# RK3566_HPB1.net
KiCad netlist of a schematic drawn in Altium Designer
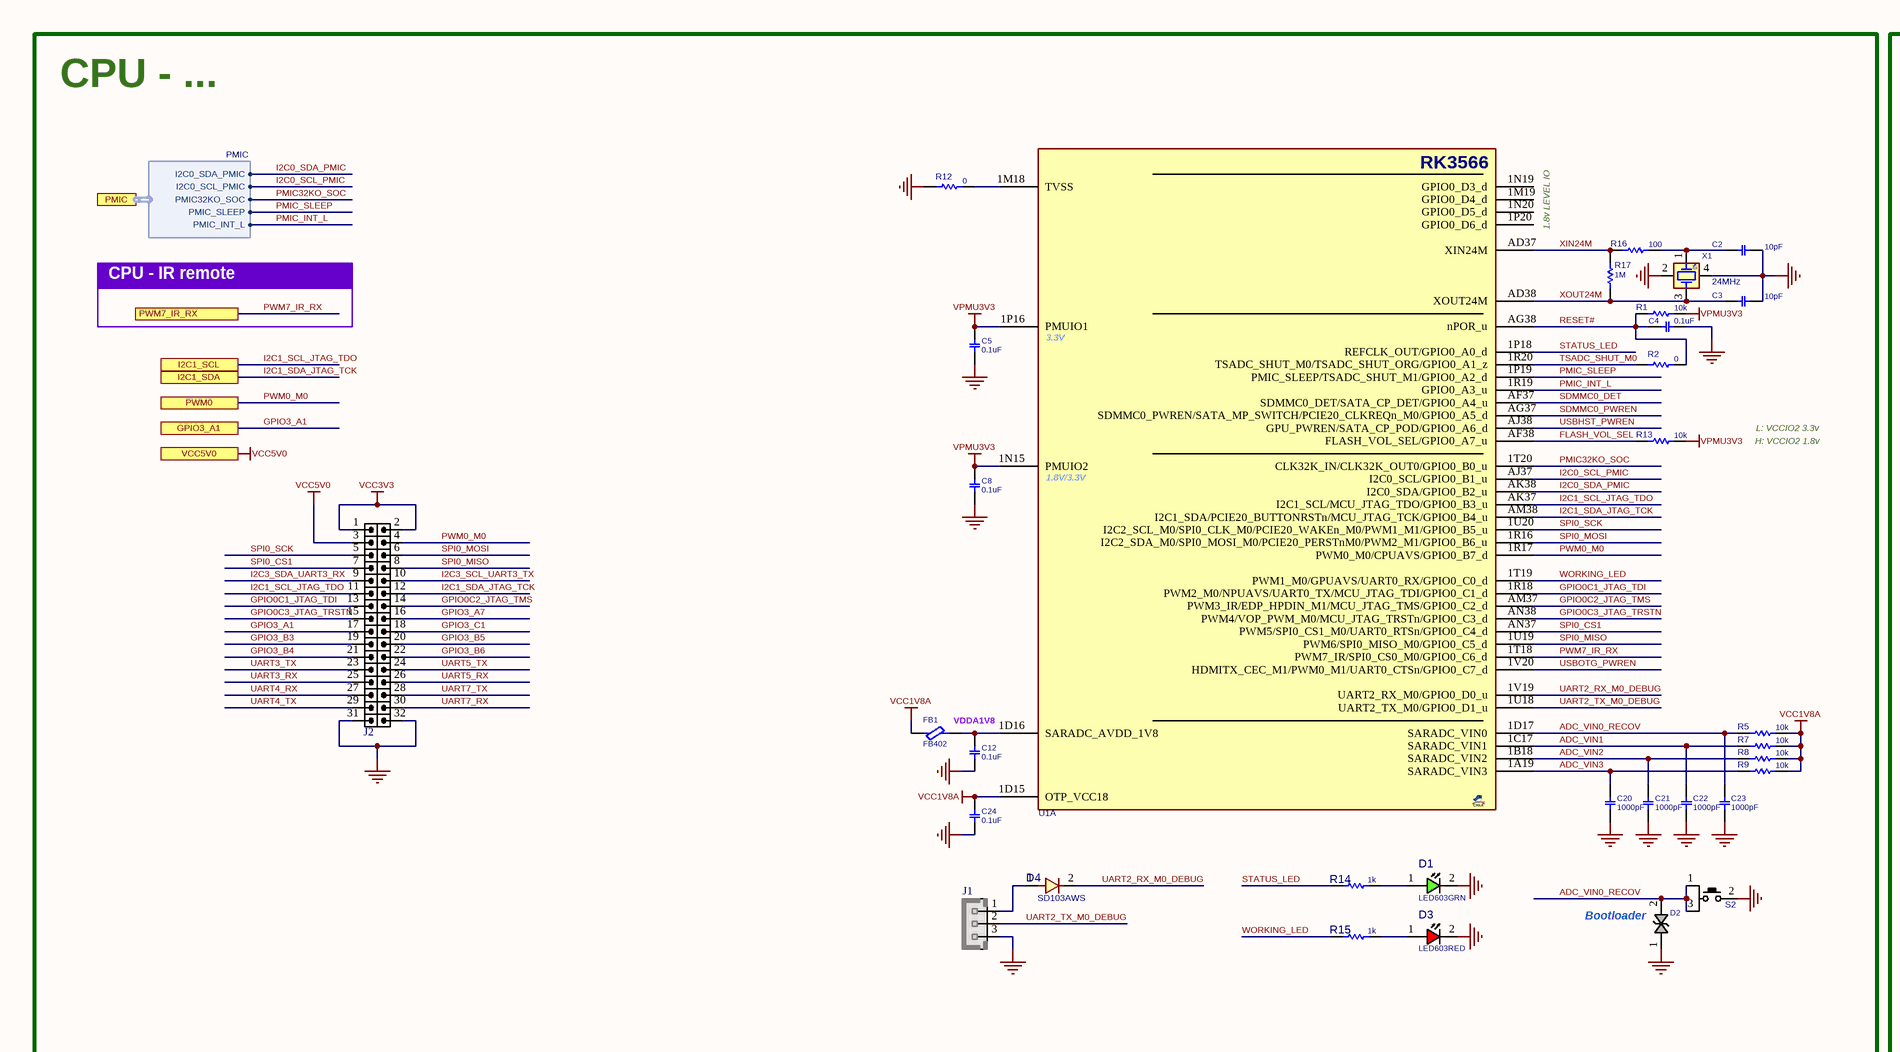
[diagram p0: RK3566_HPB1.SchDoc, top left]
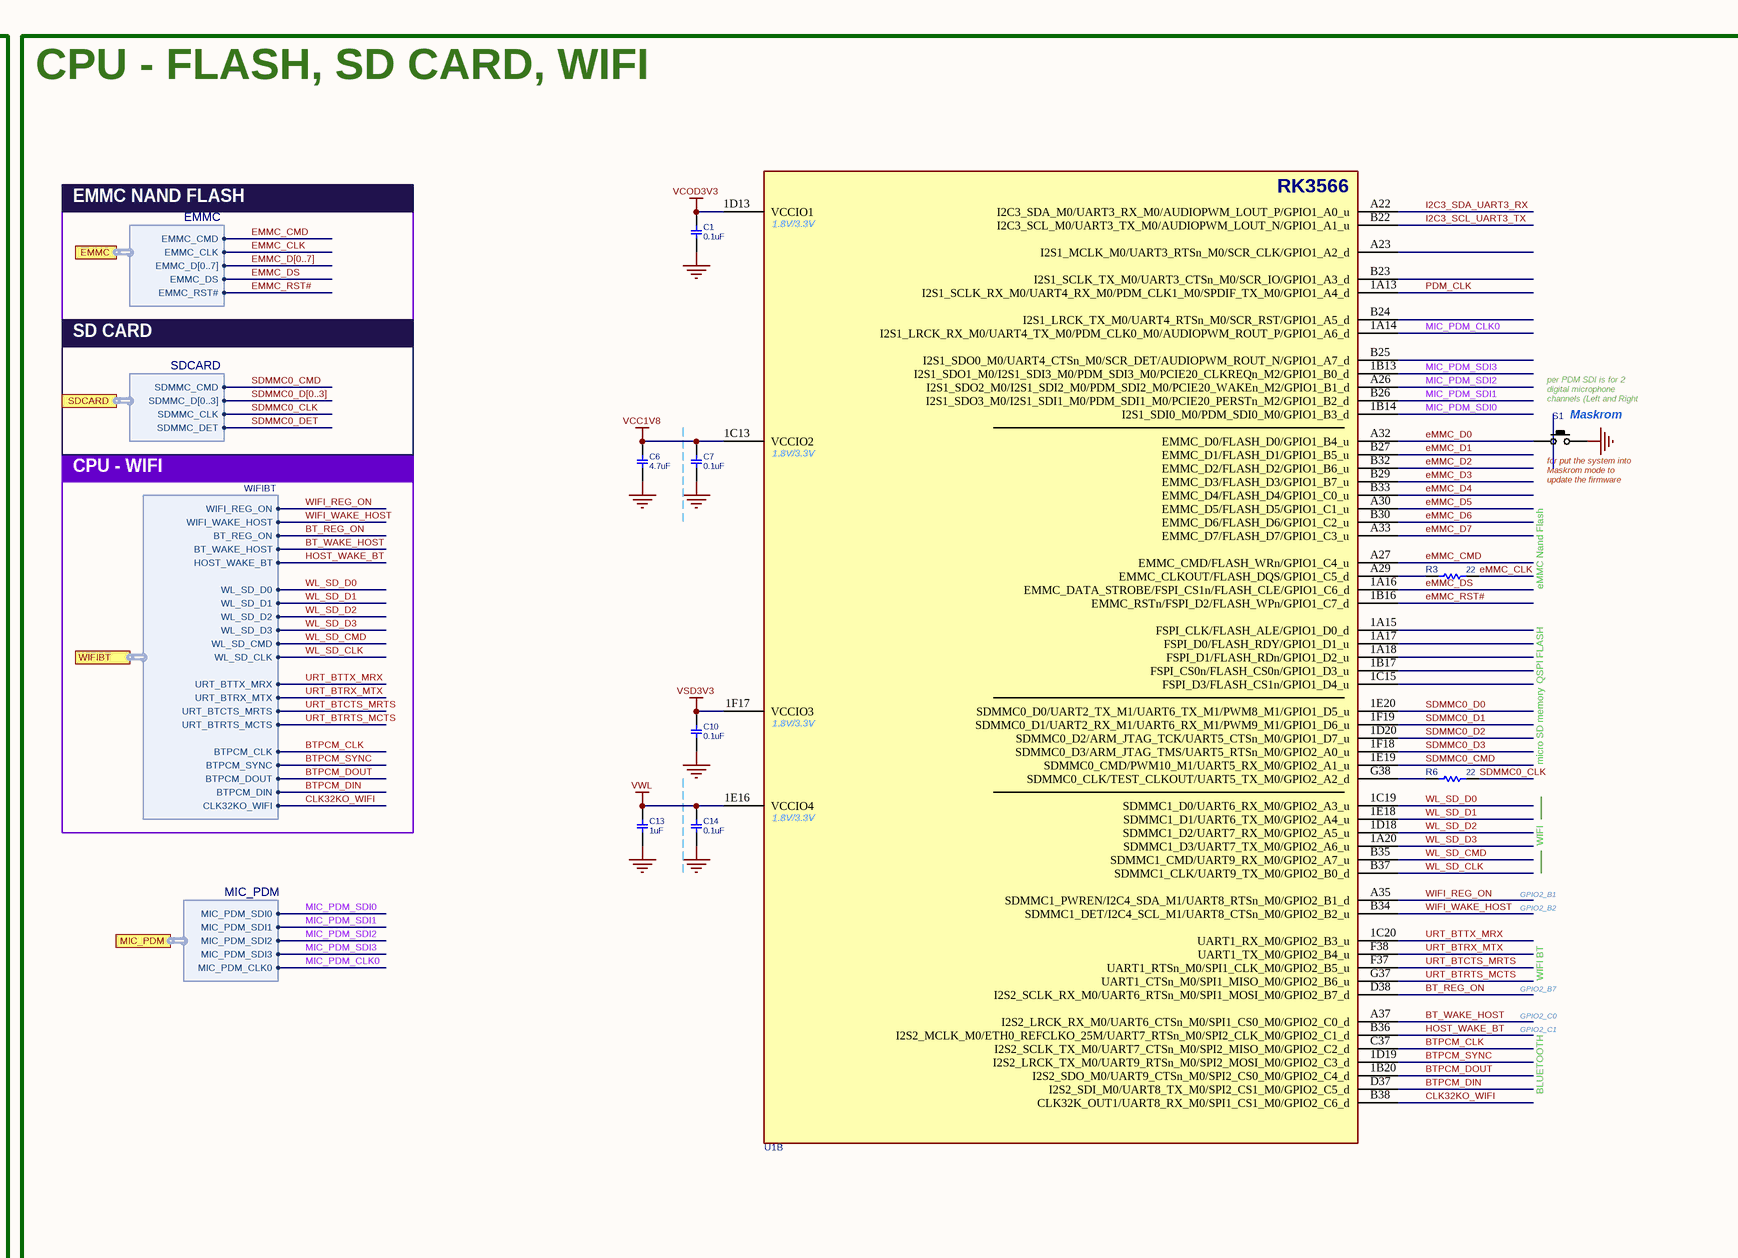
[diagram p1: RK3566_HPB1.SchDoc, top middle]
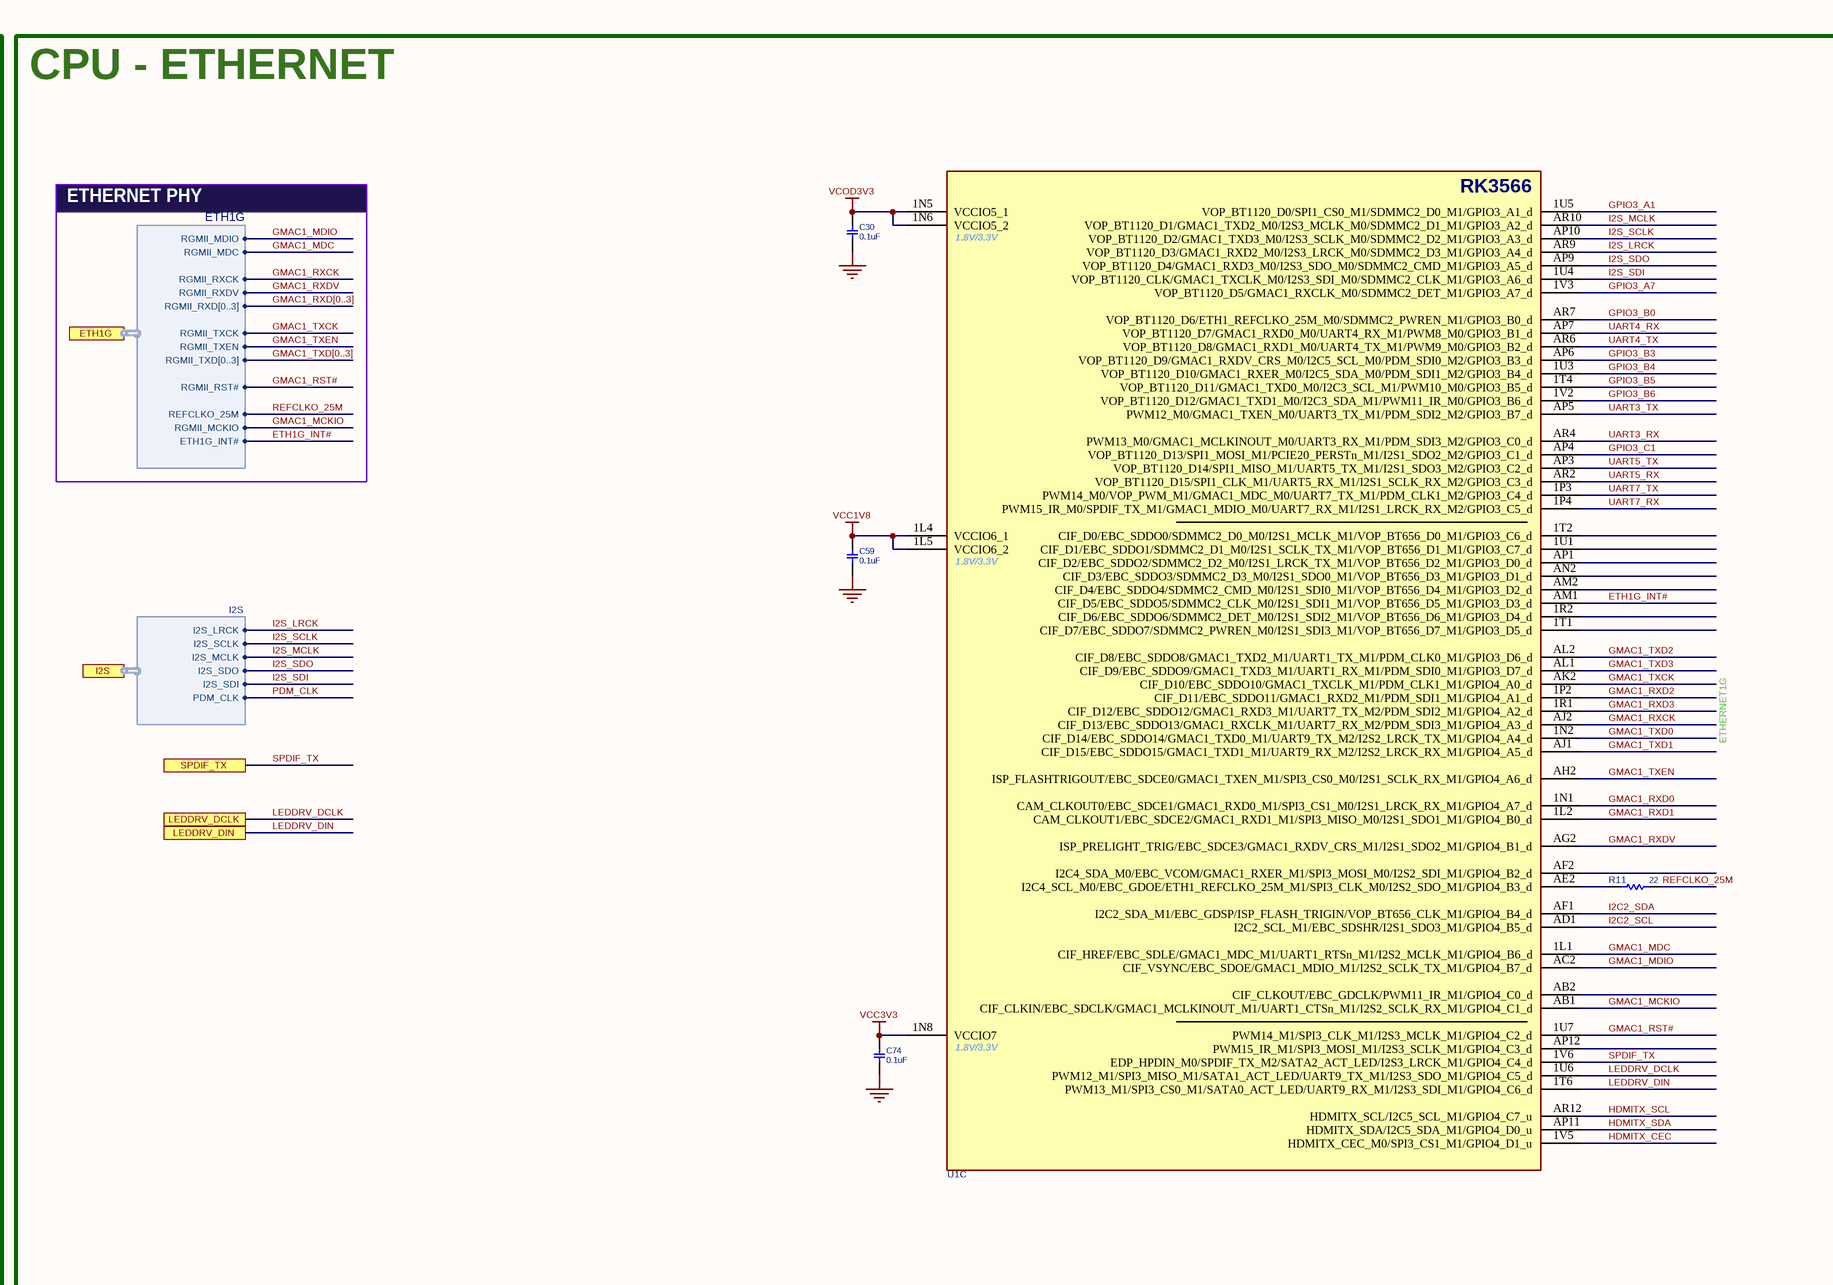
[diagram p2: RK3566_HPB1.SchDoc, top right]
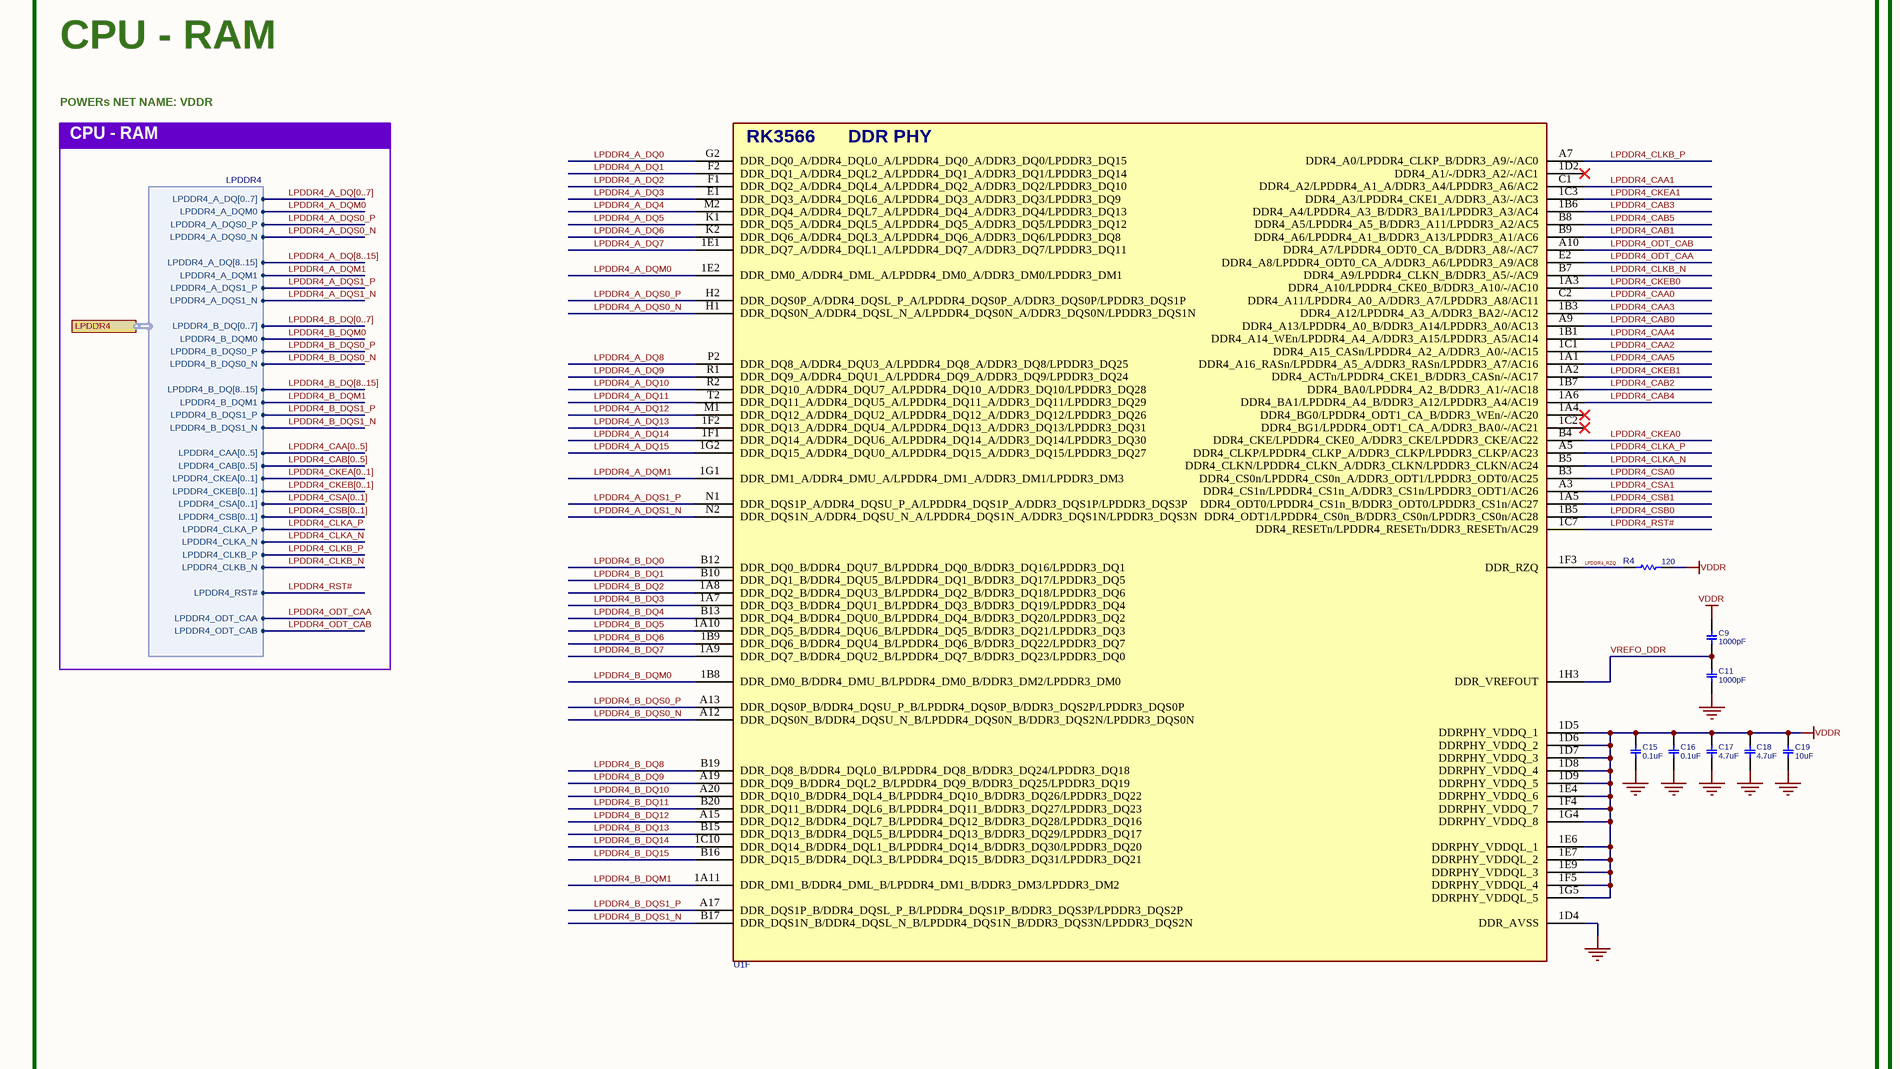
[diagram p3: RK3566_HPB1.SchDoc, bottom left]
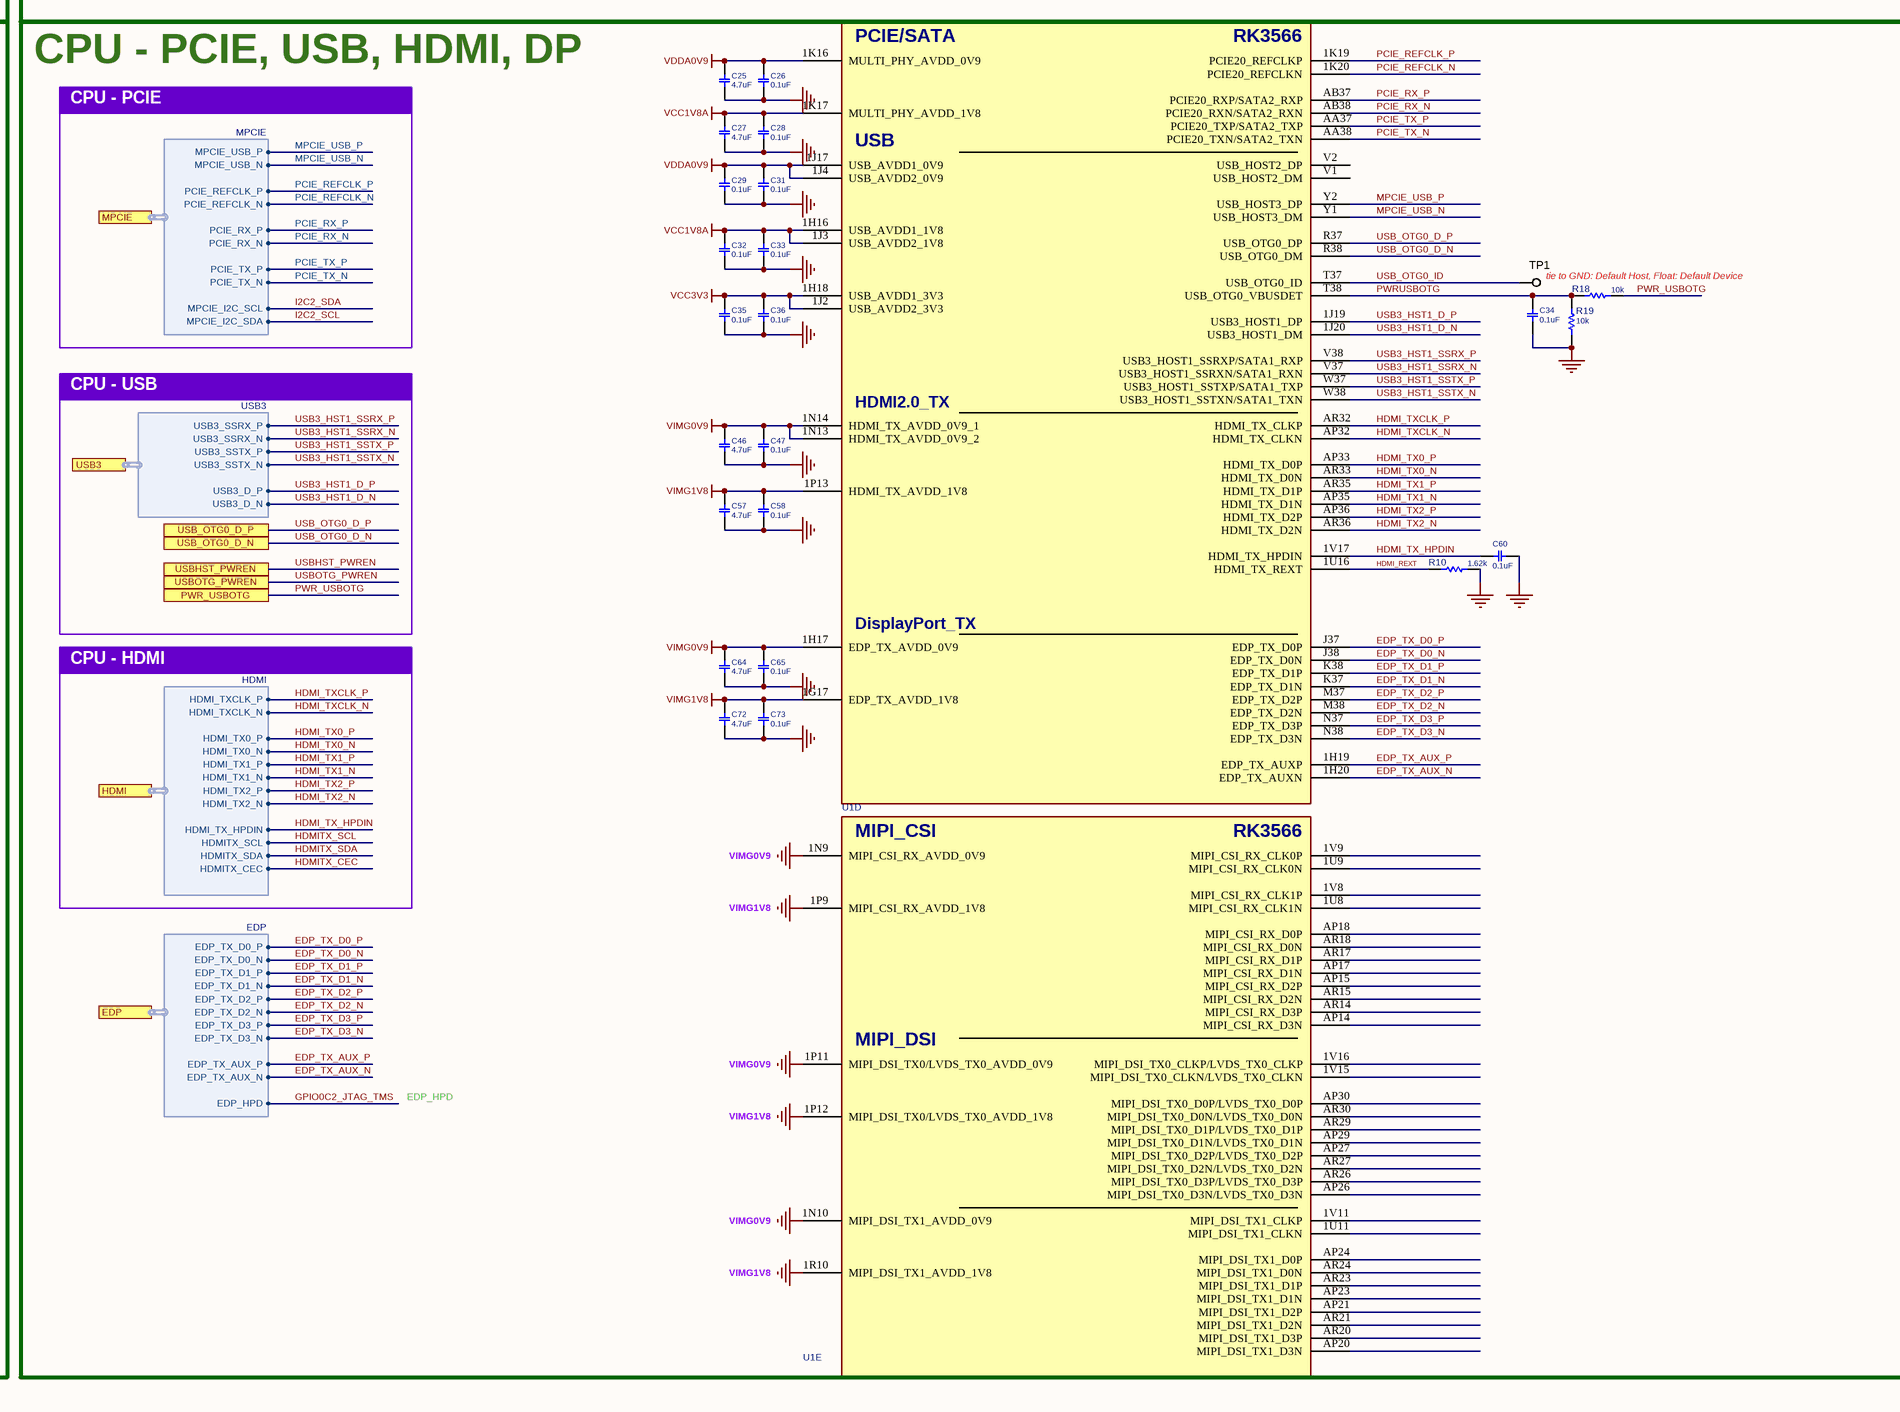
[diagram p4: RK3566_HPB1.SchDoc, bottom middle]
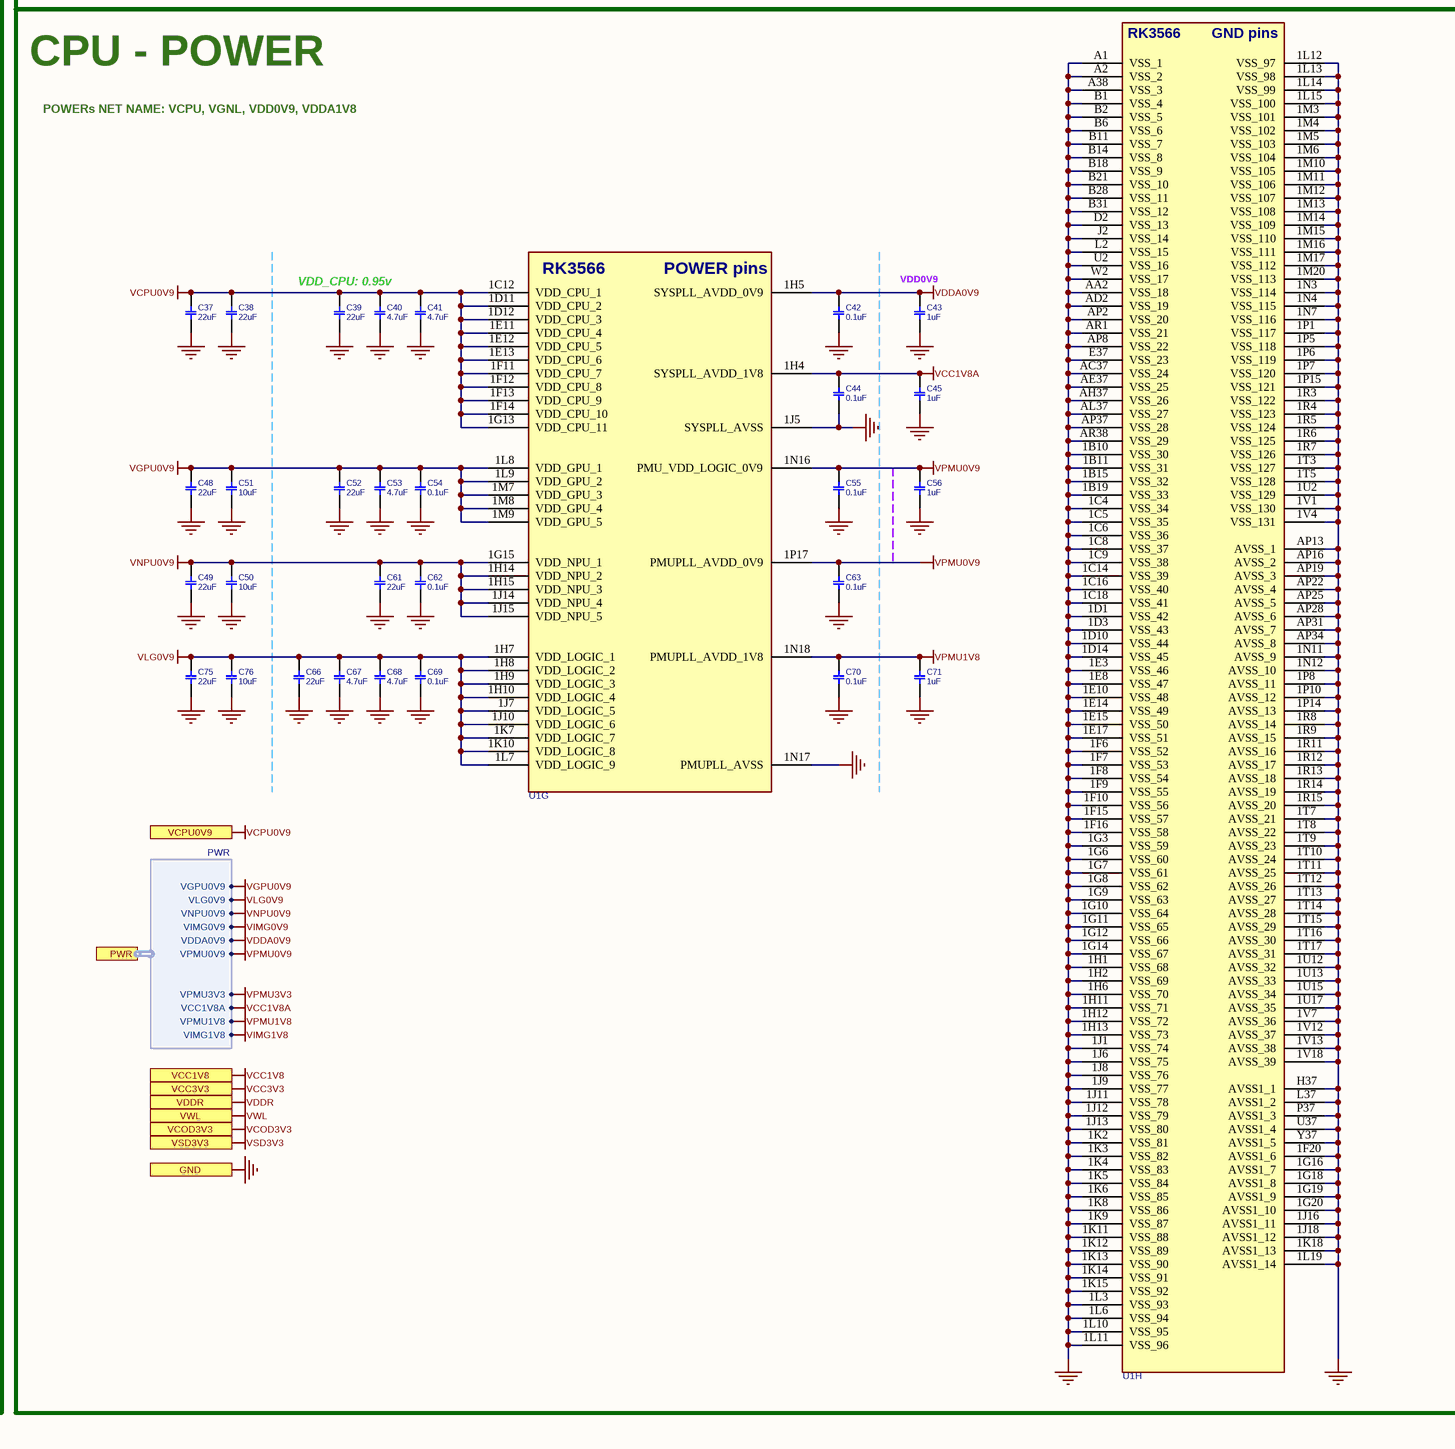
[diagram p5: RK3566_HPB1.SchDoc, bottom right]

(export (version "E")
  (design (tool "Eeschema 10.0.6"))
  (components
    (comp (ref "C1")
      (value "0.1uF")
      (footprint "C0201")
      (description "CAP, MLCC")
      (fields (field (name "MANF_P#") "CL03A104KP3NNWC") (field (name "MANF") "Samsung"))
      (libsource (lib "passive_smd") (part "CAP_SMD_MLCC"))
    )
    (comp (ref "C2")
      (value "10pF")
      (footprint "C0402A")
      (description "CAP, MLCC")
      (fields (field (name "MANF_P#") "CC0402JRNPO9BN180") (field (name "MANF") "Yageo"))
      (libsource (lib "mlcc_smd_passive") (part "CAP_SMD_MLCC"))
    )
    (comp (ref "C3")
      (value "10pF")
      (footprint "C0402A")
      (description "CAP, MLCC")
      (fields (field (name "MANF_P#") "CC0402JRNPO9BN180") (field (name "MANF") "Yageo"))
      (libsource (lib "mlcc_smd_passive") (part "CAP_SMD_MLCC"))
    )
    (comp (ref "C4")
      (value "0.1uF")
      (footprint "C0402A")
      (description "CAP, MLCC")
      (fields (field (name "MANF_P#") "CL03A104KP3NNWC") (field (name "MANF") "Samsung"))
      (libsource (lib "passive_smd") (part "CAP_SMD_MLCC"))
    )
    (comp (ref "C5")
      (value "0.1uF")
      (footprint "C0201")
      (description "CAP, MLCC")
      (fields (field (name "MANF_P#") "CL03A104KP3NNWC") (field (name "MANF") "Samsung"))
      (libsource (lib "passive_smd") (part "CAP_SMD_MLCC"))
    )
    (comp (ref "C6")
      (value "4.7uF")
      (footprint "C0201")
      (description "CAP, MLCC")
      (fields (field (name "MANF_P#") "CL03A475MQ5C65C") (field (name "MANF") "Samsung"))
      (libsource (lib "passive_smd") (part "CAP_SMD_MLCC"))
    )
    (comp (ref "C7")
      (value "0.1uF")
      (footprint "C0201")
      (description "CAP, MLCC")
      (fields (field (name "MANF_P#") "CL03A104KP3NNWC") (field (name "MANF") "Samsung"))
      (libsource (lib "passive_smd") (part "CAP_SMD_MLCC"))
    )
    (comp (ref "C8")
      (value "0.1uF")
      (footprint "C0201")
      (description "CAP, MLCC")
      (fields (field (name "MANF_P#") "CL03A104KP3NNWC") (field (name "MANF") "Samsung"))
      (libsource (lib "passive_smd") (part "CAP_SMD_MLCC"))
    )
    (comp (ref "C9")
      (value "1000pF")
      (footprint "C0201")
      (description "CAP, MLCC")
      (fields (field (name "MANF_P#") "CC0201KRX7R7BB102") (field (name "MANF") "Yageo"))
      (libsource (lib "mlcc_smd_passive") (part "CAP_SMD_MLCC"))
    )
    (comp (ref "C10")
      (value "0.1uF")
      (footprint "C0201")
      (description "CAP, MLCC")
      (fields (field (name "MANF_P#") "CL03A104KP3NNWC") (field (name "MANF") "Samsung"))
      (libsource (lib "passive_smd") (part "CAP_SMD_MLCC"))
    )
    (comp (ref "C11")
      (value "1000pF")
      (footprint "C0201")
      (description "CAP, MLCC")
      (fields (field (name "MANF_P#") "CC0201KRX7R7BB102") (field (name "MANF") "Yageo"))
      (libsource (lib "mlcc_smd_passive") (part "CAP_SMD_MLCC"))
    )
    (comp (ref "C12")
      (value "0.1uF")
      (footprint "C0201")
      (description "CAP, MLCC")
      (fields (field (name "MANF_P#") "CL03A104KP3NNWC") (field (name "MANF") "Samsung"))
      (libsource (lib "passive_smd") (part "CAP_SMD_MLCC"))
    )
    (comp (ref "C13")
      (value "1uF")
      (footprint "C0201")
      (description "CAP, MLCC")
      (fields (field (name "MANF_P#") "CL03A105MQ3CSNC") (field (name "MANF") "Samsung"))
      (libsource (lib "passive_smd") (part "CAP_SMD_MLCC"))
    )
    (comp (ref "C14")
      (value "0.1uF")
      (footprint "C0201")
      (description "CAP, MLCC")
      (fields (field (name "MANF_P#") "CL03A104KP3NNWC") (field (name "MANF") "Samsung"))
      (libsource (lib "passive_smd") (part "CAP_SMD_MLCC"))
    )
    (comp (ref "C15")
      (value "0.1uF")
      (footprint "C0201")
      (description "CAP, MLCC")
      (fields (field (name "MANF_P#") "CL03A104KP3NNWC") (field (name "MANF") "Samsung"))
      (libsource (lib "passive_smd") (part "CAP_SMD_MLCC"))
    )
    (comp (ref "C16")
      (value "0.1uF")
      (footprint "C0201")
      (description "CAP, MLCC")
      (fields (field (name "MANF_P#") "CL03A104KP3NNWC") (field (name "MANF") "Samsung"))
      (libsource (lib "passive_smd") (part "CAP_SMD_MLCC"))
    )
    (comp (ref "C17")
      (value "4.7uF")
      (footprint "C0201")
      (description "CAP, MLCC")
      (fields (field (name "MANF_P#") "CL03A475MQ5C65C") (field (name "MANF") "Samsung"))
      (libsource (lib "passive_smd") (part "CAP_SMD_MLCC"))
    )
    (comp (ref "C18")
      (value "4.7uF")
      (footprint "C0201")
      (description "CAP, MLCC")
      (fields (field (name "MANF_P#") "CL03A475MQ5C65C") (field (name "MANF") "Samsung"))
      (libsource (lib "passive_smd") (part "CAP_SMD_MLCC"))
    )
    (comp (ref "C19")
      (value "10uF")
      (footprint "C0402A")
      (description "CAP, MLCC")
      (fields (field (name "MANF_P#") "CL05A106MP5NUNC") (field (name "MANF") "Samsung"))
      (libsource (lib "passive_smd") (part "CAP_SMD_MLCC"))
    )
    (comp (ref "C20")
      (value "1000pF")
      (footprint "C0201")
      (description "CAP, MLCC")
      (fields (field (name "MANF_P#") "CC0201KRX7R7BB102") (field (name "MANF") "Yageo"))
      (libsource (lib "mlcc_smd_passive") (part "CAP_SMD_MLCC"))
    )
    (comp (ref "C21")
      (value "1000pF")
      (footprint "C0201")
      (description "CAP, MLCC")
      (fields (field (name "MANF_P#") "CC0201KRX7R7BB102") (field (name "MANF") "Yageo"))
      (libsource (lib "mlcc_smd_passive") (part "CAP_SMD_MLCC"))
    )
    (comp (ref "C22")
      (value "1000pF")
      (footprint "C0201")
      (description "CAP, MLCC")
      (fields (field (name "MANF_P#") "CC0201KRX7R7BB102") (field (name "MANF") "Yageo"))
      (libsource (lib "mlcc_smd_passive") (part "CAP_SMD_MLCC"))
    )
    (comp (ref "C23")
      (value "1000pF")
      (footprint "C0201")
      (description "CAP, MLCC")
      (fields (field (name "MANF_P#") "CC0201KRX7R7BB102") (field (name "MANF") "Yageo"))
      (libsource (lib "mlcc_smd_passive") (part "CAP_SMD_MLCC"))
    )
    (comp (ref "C24")
      (value "0.1uF")
      (footprint "C0201")
      (description "CAP, MLCC")
      (fields (field (name "MANF_P#") "CL03A104KP3NNWC") (field (name "MANF") "Samsung"))
      (libsource (lib "passive_smd") (part "CAP_SMD_MLCC"))
    )
    (comp (ref "C25")
      (value "4.7uF")
      (footprint "C0201")
      (description "CAP, MLCC")
      (fields (field (name "MANF_P#") "CL03A475MQ5C65C") (field (name "MANF") "Samsung"))
      (libsource (lib "passive_smd") (part "CAP_SMD_MLCC"))
    )
    (comp (ref "C26")
      (value "0.1uF")
      (footprint "C0201")
      (description "CAP, MLCC")
      (fields (field (name "MANF_P#") "CL03A104KP3NNWC") (field (name "MANF") "Samsung"))
      (libsource (lib "passive_smd") (part "CAP_SMD_MLCC"))
    )
    (comp (ref "C27")
      (value "4.7uF")
      (footprint "C0201")
      (description "CAP, MLCC")
      (fields (field (name "MANF_P#") "CL03A475MQ5C65C") (field (name "MANF") "Samsung"))
      (libsource (lib "passive_smd") (part "CAP_SMD_MLCC"))
    )
    (comp (ref "C28")
      (value "0.1uF")
      (footprint "C0201")
      (description "CAP, MLCC")
      (fields (field (name "MANF_P#") "CL03A104KP3NNWC") (field (name "MANF") "Samsung"))
      (libsource (lib "passive_smd") (part "CAP_SMD_MLCC"))
    )
    (comp (ref "C29")
      (value "0.1uF")
      (footprint "C0201")
      (description "CAP, MLCC")
      (fields (field (name "MANF_P#") "CL03A104KP3NNWC") (field (name "MANF") "Samsung"))
      (libsource (lib "passive_smd") (part "CAP_SMD_MLCC"))
    )
    (comp (ref "C30")
      (value "0.1uF")
      (footprint "C0201")
      (description "CAP, MLCC")
      (fields (field (name "MANF_P#") "CL03A104KP3NNWC") (field (name "MANF") "Samsung"))
      (libsource (lib "passive_smd") (part "CAP_SMD_MLCC"))
    )
    (comp (ref "C31")
      (value "0.1uF")
      (footprint "C0201")
      (description "CAP, MLCC")
      (fields (field (name "MANF_P#") "CL03A104KP3NNWC") (field (name "MANF") "Samsung"))
      (libsource (lib "passive_smd") (part "CAP_SMD_MLCC"))
    )
    (comp (ref "C32")
      (value "0.1uF")
      (footprint "C0201")
      (description "CAP, MLCC")
      (fields (field (name "MANF_P#") "CL03A104KP3NNWC") (field (name "MANF") "Samsung"))
      (libsource (lib "passive_smd") (part "CAP_SMD_MLCC"))
    )
    (comp (ref "C33")
      (value "0.1uF")
      (footprint "C0201")
      (description "CAP, MLCC")
      (fields (field (name "MANF_P#") "CL03A104KP3NNWC") (field (name "MANF") "Samsung"))
      (libsource (lib "passive_smd") (part "CAP_SMD_MLCC"))
    )
    (comp (ref "C34")
      (value "0.1uF")
      (footprint "C0402A")
      (description "CAP, MLCC")
      (fields (field (name "MANF_P#") "CL03A104KP3NNWC") (field (name "MANF") "Samsung"))
      (libsource (lib "passive_smd") (part "CAP_SMD_MLCC"))
    )
    (comp (ref "C35")
      (value "0.1uF")
      (footprint "C0201")
      (description "CAP, MLCC")
      (fields (field (name "MANF_P#") "CL03A104KP3NNWC") (field (name "MANF") "Samsung"))
      (libsource (lib "passive_smd") (part "CAP_SMD_MLCC"))
    )
    (comp (ref "C36")
      (value "0.1uF")
      (footprint "C0201")
      (description "CAP, MLCC")
      (fields (field (name "MANF_P#") "CL03A104KP3NNWC") (field (name "MANF") "Samsung"))
      (libsource (lib "passive_smd") (part "CAP_SMD_MLCC"))
    )
    (comp (ref "C37")
      (value "22uF")
      (footprint "C0402A")
      (description "CAP, MLCC")
      (fields (field (name "MANF_P#") "GRM158R61A226ME15") (field (name "MANF") "Murata"))
      (libsource (lib "passive_smd") (part "CAP_SMD_MLCC"))
    )
    (comp (ref "C38")
      (value "22uF")
      (footprint "C0402A")
      (description "CAP, MLCC")
      (fields (field (name "MANF_P#") "GRM158R61A226ME15") (field (name "MANF") "Murata"))
      (libsource (lib "passive_smd") (part "CAP_SMD_MLCC"))
    )
    (comp (ref "C39")
      (value "22uF")
      (footprint "C0402A")
      (description "CAP, MLCC")
      (fields (field (name "MANF_P#") "GRM158R61A226ME15") (field (name "MANF") "Murata"))
      (libsource (lib "passive_smd") (part "CAP_SMD_MLCC"))
    )
    (comp (ref "C40")
      (value "4.7uF")
      (footprint "C0201")
      (description "CAP, MLCC")
      (fields (field (name "MANF_P#") "CL03A475MQ5C65C") (field (name "MANF") "Samsung"))
      (libsource (lib "passive_smd") (part "CAP_SMD_MLCC"))
    )
    (comp (ref "C41")
      (value "4.7uF")
      (footprint "C0201")
      (description "CAP, MLCC")
      (fields (field (name "MANF_P#") "CL03A475MQ5C65C") (field (name "MANF") "Samsung"))
      (libsource (lib "passive_smd") (part "CAP_SMD_MLCC"))
    )
    (comp (ref "C42")
      (value "0.1uF")
      (footprint "C0201")
      (description "CAP, MLCC")
      (fields (field (name "MANF_P#") "CL03A104KP3NNWC") (field (name "MANF") "Samsung"))
      (libsource (lib "passive_smd") (part "CAP_SMD_MLCC"))
    )
    (comp (ref "C43")
      (value "1uF")
      (footprint "C0201")
      (description "CAP, MLCC")
      (fields (field (name "MANF_P#") "CL03A105MQ3CSNC") (field (name "MANF") "Samsung"))
      (libsource (lib "passive_smd") (part "CAP_SMD_MLCC"))
    )
    (comp (ref "C44")
      (value "0.1uF")
      (footprint "C0201")
      (description "CAP, MLCC")
      (fields (field (name "MANF_P#") "CL03A104KP3NNWC") (field (name "MANF") "Samsung"))
      (libsource (lib "passive_smd") (part "CAP_SMD_MLCC"))
    )
    (comp (ref "C45")
      (value "1uF")
      (footprint "C0201")
      (description "CAP, MLCC")
      (fields (field (name "MANF_P#") "CL03A105MQ3CSNC") (field (name "MANF") "Samsung"))
      (libsource (lib "passive_smd") (part "CAP_SMD_MLCC"))
    )
    (comp (ref "C46")
      (value "4.7uF")
      (footprint "C0201")
      (description "CAP, MLCC")
      (fields (field (name "MANF_P#") "CL03A475MQ5C65C") (field (name "MANF") "Samsung"))
      (libsource (lib "passive_smd") (part "CAP_SMD_MLCC"))
    )
    (comp (ref "C47")
      (value "0.1uF")
      (footprint "C0201")
      (description "CAP, MLCC")
      (fields (field (name "MANF_P#") "CL03A104KP3NNWC") (field (name "MANF") "Samsung"))
      (libsource (lib "passive_smd") (part "CAP_SMD_MLCC"))
    )
    (comp (ref "C48")
      (value "22uF")
      (footprint "C0402A")
      (description "CAP, MLCC")
      (fields (field (name "MANF_P#") "GRM158R61A226ME15") (field (name "MANF") "Murata"))
      (libsource (lib "passive_smd") (part "CAP_SMD_MLCC"))
    )
    (comp (ref "C49")
      (value "22uF")
      (footprint "C0402A")
      (description "CAP, MLCC")
      (fields (field (name "MANF_P#") "GRM158R61A226ME15") (field (name "MANF") "Murata"))
      (libsource (lib "passive_smd") (part "CAP_SMD_MLCC"))
    )
    (comp (ref "C50")
      (value "10uF")
      (footprint "C0402A")
      (description "CAP, MLCC")
      (fields (field (name "MANF_P#") "CL05A106MP5NUNC") (field (name "MANF") "Samsung"))
      (libsource (lib "passive_smd") (part "CAP_SMD_MLCC"))
    )
    (comp (ref "C51")
      (value "10uF")
      (footprint "C0402A")
      (description "CAP, MLCC")
      (fields (field (name "MANF_P#") "CL05A106MP5NUNC") (field (name "MANF") "Samsung"))
      (libsource (lib "passive_smd") (part "CAP_SMD_MLCC"))
    )
    (comp (ref "C52")
      (value "22uF")
      (footprint "C0402A")
      (description "CAP, MLCC")
      (fields (field (name "MANF_P#") "GRM158R61A226ME15") (field (name "MANF") "Murata"))
      (libsource (lib "passive_smd") (part "CAP_SMD_MLCC"))
    )
    (comp (ref "C53")
      (value "4.7uF")
      (footprint "C0201")
      (description "CAP, MLCC")
      (fields (field (name "MANF_P#") "CL03A475MQ5C65C") (field (name "MANF") "Samsung"))
      (libsource (lib "passive_smd") (part "CAP_SMD_MLCC"))
    )
    (comp (ref "C54")
      (value "0.1uF")
      (footprint "C0201")
      (description "CAP, MLCC")
      (fields (field (name "MANF_P#") "CL03A104KP3NNWC") (field (name "MANF") "Samsung"))
      (libsource (lib "passive_smd") (part "CAP_SMD_MLCC"))
    )
    (comp (ref "C55")
      (value "0.1uF")
      (footprint "C0201")
      (description "CAP, MLCC")
      (fields (field (name "MANF_P#") "CL03A104KP3NNWC") (field (name "MANF") "Samsung"))
      (libsource (lib "passive_smd") (part "CAP_SMD_MLCC"))
    )
    (comp (ref "C56")
      (value "1uF")
      (footprint "C0201")
      (description "CAP, MLCC")
      (fields (field (name "MANF_P#") "CL03A105MQ3CSNC") (field (name "MANF") "Samsung"))
      (libsource (lib "passive_smd") (part "CAP_SMD_MLCC"))
    )
    (comp (ref "C57")
      (value "4.7uF")
      (footprint "C0201")
      (description "CAP, MLCC")
      (fields (field (name "MANF_P#") "CL03A475MQ5C65C") (field (name "MANF") "Samsung"))
      (libsource (lib "passive_smd") (part "CAP_SMD_MLCC"))
    )
    (comp (ref "C58")
      (value "0.1uF")
      (footprint "C0201")
      (description "CAP, MLCC")
      (fields (field (name "MANF_P#") "CL03A104KP3NNWC") (field (name "MANF") "Samsung"))
      (libsource (lib "passive_smd") (part "CAP_SMD_MLCC"))
    )
    (comp (ref "C59")
      (value "0.1uF")
      (footprint "C0201")
      (description "CAP, MLCC")
      (fields (field (name "MANF_P#") "CL03A104KP3NNWC") (field (name "MANF") "Samsung"))
      (libsource (lib "passive_smd") (part "CAP_SMD_MLCC"))
    )
    (comp (ref "C60")
      (value "0.1uF")
      (footprint "C0201")
      (description "CAP, MLCC")
      (fields (field (name "MANF_P#") "CL03A104KP3NNWC") (field (name "MANF") "Samsung"))
      (libsource (lib "passive_smd") (part "CAP_SMD_MLCC"))
    )
    (comp (ref "C61")
      (value "22uF")
      (footprint "C0402A")
      (description "CAP, MLCC")
      (fields (field (name "MANF_P#") "GRM158R61A226ME15") (field (name "MANF") "Murata"))
      (libsource (lib "passive_smd") (part "CAP_SMD_MLCC"))
    )
    (comp (ref "C62")
      (value "0.1uF")
      (footprint "C0201")
      (description "CAP, MLCC")
      (fields (field (name "MANF_P#") "CL03A104KP3NNWC") (field (name "MANF") "Samsung"))
      (libsource (lib "passive_smd") (part "CAP_SMD_MLCC"))
    )
    (comp (ref "C63")
      (value "0.1uF")
      (footprint "C0201")
      (description "CAP, MLCC")
      (fields (field (name "MANF_P#") "CL03A104KP3NNWC") (field (name "MANF") "Samsung"))
      (libsource (lib "passive_smd") (part "CAP_SMD_MLCC"))
    )
    (comp (ref "C64")
      (value "4.7uF")
      (footprint "C0201")
      (description "CAP, MLCC")
      (fields (field (name "MANF_P#") "CL03A475MQ5C65C") (field (name "MANF") "Samsung"))
      (libsource (lib "passive_smd") (part "CAP_SMD_MLCC"))
    )
    (comp (ref "C65")
      (value "0.1uF")
      (footprint "C0201")
      (description "CAP, MLCC")
      (fields (field (name "MANF_P#") "CL03A104KP3NNWC") (field (name "MANF") "Samsung"))
      (libsource (lib "passive_smd") (part "CAP_SMD_MLCC"))
    )
    (comp (ref "C66")
      (value "22uF")
      (footprint "C0402A")
      (description "CAP, MLCC")
      (fields (field (name "MANF_P#") "GRM158R61A226ME15") (field (name "MANF") "Murata"))
      (libsource (lib "passive_smd") (part "CAP_SMD_MLCC"))
    )
    (comp (ref "C67")
      (value "4.7uF")
      (footprint "C0201")
      (description "CAP, MLCC")
      (fields (field (name "MANF_P#") "CL03A475MQ5C65C") (field (name "MANF") "Samsung"))
      (libsource (lib "passive_smd") (part "CAP_SMD_MLCC"))
    )
    (comp (ref "C68")
      (value "4.7uF")
      (footprint "C0201")
      (description "CAP, MLCC")
      (fields (field (name "MANF_P#") "CL03A475MQ5C65C") (field (name "MANF") "Samsung"))
      (libsource (lib "passive_smd") (part "CAP_SMD_MLCC"))
    )
    (comp (ref "C69")
      (value "0.1uF")
      (footprint "C0201")
      (description "CAP, MLCC")
      (fields (field (name "MANF_P#") "CL03A104KP3NNWC") (field (name "MANF") "Samsung"))
      (libsource (lib "passive_smd") (part "CAP_SMD_MLCC"))
    )
    (comp (ref "C70")
      (value "0.1uF")
      (footprint "C0201")
      (description "CAP, MLCC")
      (fields (field (name "MANF_P#") "CL03A104KP3NNWC") (field (name "MANF") "Samsung"))
      (libsource (lib "passive_smd") (part "CAP_SMD_MLCC"))
    )
    (comp (ref "C71")
      (value "1uF")
      (footprint "C0201")
      (description "CAP, MLCC")
      (fields (field (name "MANF_P#") "CL03A105MQ3CSNC") (field (name "MANF") "Samsung"))
      (libsource (lib "passive_smd") (part "CAP_SMD_MLCC"))
    )
    (comp (ref "C72")
      (value "4.7uF")
      (footprint "C0201")
      (description "CAP, MLCC")
      (fields (field (name "MANF_P#") "CL03A475MQ5C65C") (field (name "MANF") "Samsung"))
      (libsource (lib "passive_smd") (part "CAP_SMD_MLCC"))
    )
    (comp (ref "C73")
      (value "0.1uF")
      (footprint "C0201")
      (description "CAP, MLCC")
      (fields (field (name "MANF_P#") "CL03A104KP3NNWC") (field (name "MANF") "Samsung"))
      (libsource (lib "passive_smd") (part "CAP_SMD_MLCC"))
    )
    (comp (ref "C74")
      (value "0.1uF")
      (footprint "C0201")
      (description "CAP, MLCC")
      (fields (field (name "MANF_P#") "CL03A104KP3NNWC") (field (name "MANF") "Samsung"))
      (libsource (lib "passive_smd") (part "CAP_SMD_MLCC"))
    )
    (comp (ref "C75")
      (value "22uF")
      (footprint "C0402A")
      (description "CAP, MLCC")
      (fields (field (name "MANF_P#") "GRM158R61A226ME15") (field (name "MANF") "Murata"))
      (libsource (lib "passive_smd") (part "CAP_SMD_MLCC"))
    )
    (comp (ref "C76")
      (value "10uF")
      (footprint "C0402A")
      (description "CAP, MLCC")
      (fields (field (name "MANF_P#") "CL05A106MP5NUNC") (field (name "MANF") "Samsung"))
      (libsource (lib "passive_smd") (part "CAP_SMD_MLCC"))
    )
    (comp (ref "D1")
      (value "LED603GRN")
      (footprint "LED0603GRN")
      (description "LED, SMD, 0603, GREEN")
      (fields (field (name "MANF") "OSRAM") (field (name "MANF_P#") "LG Q396-PS-35"))
      (libsource (lib "led(diode)") (part "LED_SMD_0603_GRN_OSRAM"))
    )
    (comp (ref "D2")
      (value "TVS_PESDNC2FD3V3")
      (footprint "ESD0402")
      (description "TVS, ESD PROTECT, Bidirectional")
      (fields (field (name "MANF_P#") "PESDNC2FD3V3BS"))
      (libsource (lib "protect_tvs_esd_fuse") (part "TVS_PESDNC2FD3V3"))
    )
    (comp (ref "D3")
      (value "LED603RED")
      (footprint "LED0603RED")
      (description "LED, SMD, 0603, RED")
      (libsource (lib "led(diode)") (part "LED_SMD_0603_RED"))
    )
    (comp (ref "D4")
      (value "SD103AWS")
      (footprint "D_SOD323")
      (description "DIODE, 0.2A")
      (fields (field (name "MANF") "Diodes"))
      (libsource (lib "diode") (part "DIODE_SMD_SD103AWS_SOD323"))
    )
    (comp (ref "FB1")
      (value "FB402")
      (footprint "L0402A")
      (description "FERRITE_Bead, 0402, 0.5A, 200mOhm, 120@100MHz")
      (fields (field (name "MANF") "MURATA") (field (name "MANF_P#") "BLM15AG121SN1D"))
      (libsource (lib "emi_filter") (part "FBEAD_SMD_BLM15PD121"))
    )
    (comp (ref "J1")
      (value "HHDR_3")
      (footprint "XH_3")
      (description "JST-XH pitch: 2.5mm")
      (libsource (lib "conn_wire2board") (part "XH_3"))
    )
    (comp (ref "J2")
      (value "HDR1MM_F_2X16")
      (footprint "HDR1MM_F_2X16")
      (description "CONN, HEADER, Male, pitch: 2.54mm, 32POS")
      (fields (field (name "MANF_P#") "BC084-32-A-0390-L-C"))
      (libsource (lib "conn_header_2.54_st") (part "HDR_M_2X16"))
    )
    (comp (ref "R1")
      (value "10k")
      (footprint "R0402A")
      (description "RESISTOR, SMD")
      (libsource (lib "passive_res_smd") (part "RES_SMD"))
    )
    (comp (ref "R2")
      (value "0")
      (footprint "R0402A")
      (description "RESISTOR, SMD")
      (libsource (lib "passive_res_smd") (part "RES_SMD"))
    )
    (comp (ref "R3")
      (value "22")
      (footprint "R0402")
      (description "RESISTOR, SMD")
      (libsource (lib "passive_res_smd") (part "RES_SMD"))
    )
    (comp (ref "R4")
      (value "120")
      (footprint "R0402A")
      (description "RESISTOR, SMD")
      (libsource (lib "passive_res_smd") (part "RES_SMD"))
    )
    (comp (ref "R5")
      (value "10k")
      (footprint "R0402A")
      (description "RESISTOR, SMD")
      (libsource (lib "passive_res_smd") (part "RES_SMD"))
    )
    (comp (ref "R6")
      (value "22")
      (footprint "R0402")
      (description "RESISTOR, SMD")
      (libsource (lib "passive_res_smd") (part "RES_SMD"))
    )
    (comp (ref "R7")
      (value "10k")
      (footprint "R0402A")
      (description "RESISTOR, SMD")
      (libsource (lib "passive_res_smd") (part "RES_SMD"))
    )
    (comp (ref "R8")
      (value "10k")
      (footprint "R0402A")
      (description "RESISTOR, SMD")
      (libsource (lib "passive_res_smd") (part "RES_SMD"))
    )
    (comp (ref "R9")
      (value "10k")
      (footprint "R0402A")
      (description "RESISTOR, SMD")
      (libsource (lib "passive_res_smd") (part "RES_SMD"))
    )
    (comp (ref "R10")
      (value "1.62k")
      (footprint "R0402A")
      (description "RESISTOR, SMD")
      (libsource (lib "passive_res_smd") (part "RES_SMD"))
    )
    (comp (ref "R11")
      (value "22")
      (footprint "R0402")
      (description "RESISTOR, SMD")
      (libsource (lib "passive_res_smd") (part "RES_SMD"))
    )
    (comp (ref "R12")
      (value "0")
      (footprint "R0402A")
      (description "RESISTOR, SMD")
      (libsource (lib "passive_res_smd") (part "RES_SMD"))
    )
    (comp (ref "R13")
      (value "10k")
      (footprint "R0402A")
      (description "RESISTOR, SMD")
      (libsource (lib "passive_res_smd") (part "RES_SMD"))
    )
    (comp (ref "R14")
      (value "1k")
      (footprint "R0402A")
      (description "RESISTOR, SMD")
      (libsource (lib "passive_res_smd") (part "RES_SMD"))
    )
    (comp (ref "R15")
      (value "1k")
      (footprint "R0402A")
      (description "RESISTOR, SMD")
      (libsource (lib "passive_res_smd") (part "RES_SMD"))
    )
    (comp (ref "R16")
      (value "100")
      (footprint "R0402A")
      (description "RESISTOR, SMD")
      (libsource (lib "passive_res_smd") (part "RES_SMD"))
    )
    (comp (ref "R17")
      (value "1M")
      (footprint "R0402A")
      (description "RESISTOR, SMD")
      (libsource (lib "passive_res_smd") (part "RES_SMD"))
    )
    (comp (ref "R18")
      (value "10k")
      (footprint "R0402A")
      (description "RESISTOR, SMD")
      (libsource (lib "passive_res_smd") (part "RES_SMD"))
    )
    (comp (ref "R19")
      (value "10k")
      (footprint "R0402A")
      (description "RESISTOR, SMD")
      (libsource (lib "passive_res_smd") (part "RES_SMD"))
    )
    (comp (ref "S1")
      (value "PUSHBUTTON")
      (footprint "SWPBS_SPST_3X2X1")
      (description "SWITCH, PUSH BUTTON, TACTILE, SMD, SPST, 3X2.5X1.2mm")
      (fields (field (name "MANF") "OMRON") (field (name "MANF_P#") "B3U-1000P"))
      (libsource (lib "switch_tact_PUSHB") (part "SWPBS_SPST_3X2_B3U-1000P"))
    )
    (comp (ref "S2")
      (value "PUSHBUTTON")
      (footprint "SWPBS_SPDT_R_SKRTLA")
      (description "SWITCH, PUSH BUTTON, TACTILE, THD, SPDT, RIGHT")
      (fields
        (field (name "MANF") "ALPS, E-SWITCH, LEYE")
        (field (name "MANF_P#") "SKRTLAE010, TL3340, LY-A05-S1")
      )
      (libsource (lib "switch_tact_PUSHB") (part "SWPBS_SPDT_R_SKRTLA"))
    )
    (comp (ref "TP1")
      (value "TESTPOINT_SMD")
      (footprint "TPSMD_S1")
      (description "TEST POINT")
      (fields (field (name "MANF") "MANF") (field (name "MANF_P#") "MANF_P#"))
      (libsource (lib "test-tp_jumper") (part "TESTPOINT_SMD"))
    )
    (comp (ref "U1")
      (value "RK3566")
      (footprint "BGA65_565")
      (description "Processor, Cortex-A55 x4")
      (fields (field (name "MANF") "Rockchip"))
      (libsource (lib "processor_rockchip") (part "RK3566_BGA565"))
    )
    (comp (ref "X1")
      (value "24MHz")
      (footprint "XTL_4_2016")
      (description "Crystal 24MHz")
      (fields (field (name "MANF") "Murata") (field (name "MANF_P#") "XRCGB24M000F1H17R0"))
      (libsource (lib "crystal") (part "XTL_4_24MHz_3225"))
    )
  )
  (nets
    (net (code "14") (name "/ADC_VIN0_RECOV") (class "Default")
      (node (ref "C23") (pin "1") (pinfunction "1_1") (pintype "passive"))
      (node (ref "D2") (pin "2") (pinfunction "2_2") (pintype "passive"))
      (node (ref "R5") (pin "2") (pinfunction "2_2") (pintype "passive"))
      (node (ref "S2") (pin "1") (pinfunction "1_1") (pintype "passive"))
      (node (ref "S2") (pin "3") (pinfunction "3_3") (pintype "passive"))
      (node (ref "U1") (pin "1D17") (pinfunction "SARADC_VIN0_1D17") (pintype "passive"))
    )
    (net (code "15") (name "/ADC_VIN1") (class "Default")
      (node (ref "C22") (pin "1") (pinfunction "1_1") (pintype "passive"))
      (node (ref "R7") (pin "2") (pinfunction "2_2") (pintype "passive"))
      (node (ref "U1") (pin "1C17") (pinfunction "SARADC_VIN1_1C17") (pintype "passive"))
    )
    (net (code "16") (name "/ADC_VIN2") (class "Default")
      (node (ref "C21") (pin "1") (pinfunction "1_1") (pintype "passive"))
      (node (ref "R8") (pin "2") (pinfunction "2_2") (pintype "passive"))
      (node (ref "U1") (pin "1B18") (pinfunction "SARADC_VIN2_1B18") (pintype "passive"))
    )
    (net (code "17") (name "/ADC_VIN3") (class "Default")
      (node (ref "C20") (pin "1") (pinfunction "1_1") (pintype "passive"))
      (node (ref "R9") (pin "2") (pinfunction "2_2") (pintype "passive"))
      (node (ref "U1") (pin "1A19") (pinfunction "SARADC_VIN3_1A19") (pintype "passive"))
    )
    (net (code "18") (name "/BTPCM_CLK") (class "Default")
      (node (ref "U1") (pin "C37") (pinfunction "I2S2_SCLK_TX_M0/UART7_CTSn_M0/SPI2_MISO_M0/GPIO2_C2_d_C37") (pintype "passive"))
    )
    (net (code "19") (name "/BTPCM_DIN") (class "Default")
      (node (ref "U1") (pin "D37") (pinfunction "I2S2_SDI_M0/UART8_TX_M0/SPI2_CS1_M0/GPIO2_C5_d_D37") (pintype "passive"))
    )
    (net (code "20") (name "/BTPCM_DOUT") (class "Default")
      (node (ref "U1") (pin "1B20") (pinfunction "I2S2_SDO_M0/UART9_CTSn_M0/SPI2_CS0_M0/GPIO2_C4_d_1B20") (pintype "passive"))
    )
    (net (code "21") (name "/BTPCM_SYNC") (class "Default")
      (node (ref "U1") (pin "1D19") (pinfunction "I2S2_LRCK_TX_M0/UART9_RTSn_M0/SPI2_MOSI_M0/GPIO2_C3_d_1D19") (pintype "passive"))
    )
    (net (code "22") (name "/BT_REG_ON") (class "Default")
      (node (ref "U1") (pin "D38") (pinfunction "I2S2_SCLK_RX_M0/UART6_RTSn_M0/SPI1_MOSI_M0/GPIO2_B7_d_D38") (pintype "passive"))
    )
    (net (code "23") (name "/BT_WAKE_HOST") (class "Default")
      (node (ref "U1") (pin "A37") (pinfunction "I2S2_LRCK_RX_M0/UART6_CTSn_M0/SPI1_CS0_M0/GPIO2_C0_d_A37") (pintype "passive"))
    )
    (net (code "24") (name "/CLK32KO_WIFI") (class "Default")
      (node (ref "U1") (pin "B38") (pinfunction "CLK32K_OUT1/UART8_RX_M0/SPI1_CS1_M0/GPIO2_C6_d_B38") (pintype "passive"))
    )
    (net (code "25") (name "/EDP_TX_AUX_N") (class "Default")
      (node (ref "U1") (pin "1H20") (pinfunction "EDP_TX_AUXN_1H20") (pintype "passive"))
    )
    (net (code "26") (name "/EDP_TX_AUX_P") (class "Default")
      (node (ref "U1") (pin "1H19") (pinfunction "EDP_TX_AUXP_1H19") (pintype "passive"))
    )
    (net (code "27") (name "/EDP_TX_D0_N") (class "Default")
      (node (ref "U1") (pin "J38") (pinfunction "EDP_TX_D0N_J38") (pintype "passive"))
    )
    (net (code "28") (name "/EDP_TX_D0_P") (class "Default")
      (node (ref "U1") (pin "J37") (pinfunction "EDP_TX_D0P_J37") (pintype "passive"))
    )
    (net (code "29") (name "/EDP_TX_D1_N") (class "Default")
      (node (ref "U1") (pin "K37") (pinfunction "EDP_TX_D1N_K37") (pintype "passive"))
    )
    (net (code "30") (name "/EDP_TX_D1_P") (class "Default")
      (node (ref "U1") (pin "K38") (pinfunction "EDP_TX_D1P_K38") (pintype "passive"))
    )
    (net (code "31") (name "/EDP_TX_D2_N") (class "Default")
      (node (ref "U1") (pin "M38") (pinfunction "EDP_TX_D2N_M38") (pintype "passive"))
    )
    (net (code "32") (name "/EDP_TX_D2_P") (class "Default")
      (node (ref "U1") (pin "M37") (pinfunction "EDP_TX_D2P_M37") (pintype "passive"))
    )
    (net (code "33") (name "/EDP_TX_D3_N") (class "Default")
      (node (ref "U1") (pin "N38") (pinfunction "EDP_TX_D3N_N38") (pintype "passive"))
    )
    (net (code "34") (name "/EDP_TX_D3_P") (class "Default")
      (node (ref "U1") (pin "N37") (pinfunction "EDP_TX_D3P_N37") (pintype "passive"))
    )
    (net (code "40") (name "/ETH1G_INT#") (class "Default")
      (node (ref "U1") (pin "AM1") (pinfunction "CIF_D5/EBC_SDDO5/SDMMC2_CLK_M0/I2S1_SDI1_M1/VOP_BT656_D5_M1/GPIO3_D3_d_AM1") (pintype "passive"))
    )
    (net (code "41") (name "/FLASH_VOL_SEL") (class "Default")
      (node (ref "R13") (pin "2") (pinfunction "2_2") (pintype "passive"))
      (node (ref "U1") (pin "AF38") (pinfunction "FLASH_VOL_SEL/GPIO0_A7_u_AF38") (pintype "passive"))
    )
    (net (code "42") (name "/GMAC1_MCKIO") (class "Default")
      (node (ref "U1") (pin "AB1") (pinfunction "CIF_CLKIN/EBC_SDCLK/GMAC1_MCLKINOUT_M1/UART1_CTSn_M1/I2S2_SCLK_RX_M1/GPIO4_C1_d_AB1") (pintype "passive"))
    )
    (net (code "43") (name "/GMAC1_MDC") (class "Default")
      (node (ref "U1") (pin "1L1") (pinfunction "CIF_HREF/EBC_SDLE/GMAC1_MDC_M1/UART1_RTSn_M1/I2S2_MCLK_M1/GPIO4_B6_d_1L1") (pintype "passive"))
    )
    (net (code "44") (name "/GMAC1_MDIO") (class "Default")
      (node (ref "U1") (pin "AC2") (pinfunction "CIF_VSYNC/EBC_SDOE/GMAC1_MDIO_M1/I2S2_SCLK_TX_M1/GPIO4_B7_d_AC2") (pintype "passive"))
    )
    (net (code "45") (name "/GMAC1_RST#") (class "Default")
      (node (ref "U1") (pin "1U7") (pinfunction "PWM14_M1/SPI3_CLK_M1/I2S3_MCLK_M1/GPIO4_C2_d_1U7") (pintype "passive"))
    )
    (net (code "46") (name "/GMAC1_RXCK") (class "Default")
      (node (ref "U1") (pin "AJ2") (pinfunction "CIF_D13/EBC_SDDO13/GMAC1_RXCLK_M1/UART7_RX_M2/PDM_SDI3_M1/GPIO4_A3_d_AJ2") (pintype "passive"))
    )
    (net (code "47") (name "/GMAC1_RXD0") (class "Default")
      (node (ref "U1") (pin "1N1") (pinfunction "CAM_CLKOUT0/EBC_SDCE1/GMAC1_RXD0_M1/SPI3_CS1_M0/I2S1_LRCK_RX_M1/GPIO4_A7_d_1N1") (pintype "passive"))
    )
    (net (code "48") (name "/GMAC1_RXD1") (class "Default")
      (node (ref "U1") (pin "1L2") (pinfunction "CAM_CLKOUT1/EBC_SDCE2/GMAC1_RXD1_M1/SPI3_MISO_M0/I2S1_SDO1_M1/GPIO4_B0_d_1L2") (pintype "passive"))
    )
    (net (code "49") (name "/GMAC1_RXD2") (class "Default")
      (node (ref "U1") (pin "1P2") (pinfunction "CIF_D11/EBC_SDDO11/GMAC1_RXD2_M1/PDM_SDI1_M1/GPIO4_A1_d_1P2") (pintype "passive"))
    )
    (net (code "50") (name "/GMAC1_RXD3") (class "Default")
      (node (ref "U1") (pin "1R1") (pinfunction "CIF_D12/EBC_SDDO12/GMAC1_RXD3_M1/UART7_TX_M2/PDM_SDI2_M1/GPIO4_A2_d_1R1") (pintype "passive"))
    )
    (net (code "51") (name "/GMAC1_RXDV") (class "Default")
      (node (ref "U1") (pin "AG2") (pinfunction "ISP_PRELIGHT_TRIG/EBC_SDCE3/GMAC1_RXDV_CRS_M1/I2S1_SDO2_M1/GPIO4_B1_d_AG2") (pintype "passive"))
    )
    (net (code "53") (name "/GMAC1_TXCK") (class "Default")
      (node (ref "U1") (pin "AK2") (pinfunction "CIF_D10/EBC_SDDO10/GMAC1_TXCLK_M1/PDM_CLK1_M1/GPIO4_A0_d_AK2") (pintype "passive"))
    )
    (net (code "54") (name "/GMAC1_TXD0") (class "Default")
      (node (ref "U1") (pin "1N2") (pinfunction "CIF_D14/EBC_SDDO14/GMAC1_TXD0_M1/UART9_TX_M2/I2S2_LRCK_TX_M1/GPIO4_A4_d_1N2") (pintype "passive"))
    )
    (net (code "55") (name "/GMAC1_TXD1") (class "Default")
      (node (ref "U1") (pin "AJ1") (pinfunction "CIF_D15/EBC_SDDO15/GMAC1_TXD1_M1/UART9_RX_M2/I2S2_LRCK_RX_M1/GPIO4_A5_d_AJ1") (pintype "passive"))
    )
    (net (code "56") (name "/GMAC1_TXD2") (class "Default")
      (node (ref "U1") (pin "AL2") (pinfunction "CIF_D8/EBC_SDDO8/GMAC1_TXD2_M1/UART1_TX_M1/PDM_CLK0_M1/GPIO3_D6_d_AL2") (pintype "passive"))
    )
    (net (code "57") (name "/GMAC1_TXD3") (class "Default")
      (node (ref "U1") (pin "AL1") (pinfunction "CIF_D9/EBC_SDDO9/GMAC1_TXD3_M1/UART1_RX_M1/PDM_SDI0_M1/GPIO3_D7_d_AL1") (pintype "passive"))
    )
    (net (code "59") (name "/GMAC1_TXEN") (class "Default")
      (node (ref "U1") (pin "AH2") (pinfunction "ISP_FLASHTRIGOUT/EBC_SDCE0/GMAC1_TXEN_M1/SPI3_CS0_M0/I2S1_SCLK_RX_M1/GPIO4_A6_d_AH2") (pintype "passive"))
    )
    (net (code "60") (name "/GPIO0C1_JTAG_TDI") (class "Default")
      (node (ref "J2") (pin "13") (pinfunction "13_13") (pintype "passive"))
      (node (ref "U1") (pin "1R18") (pinfunction "PWM2_M0/NPUAVS/UART0_TX/MCU_JTAG_TDI/GPIO0_C1_d_1R18") (pintype "passive"))
    )
    (net (code "61") (name "/GPIO0C2_JTAG_TMS") (class "Default")
      (node (ref "J2") (pin "14") (pinfunction "14_14") (pintype "passive"))
      (node (ref "U1") (pin "AM37") (pinfunction "PWM3_IR/EDP_HPDIN_M1/MCU_JTAG_TMS/GPIO0_C2_d_AM37") (pintype "passive"))
    )
    (net (code "62") (name "/GPIO0C3_JTAG_TRSTN") (class "Default")
      (node (ref "J2") (pin "15") (pinfunction "15_15") (pintype "passive"))
      (node (ref "U1") (pin "AN38") (pinfunction "PWM4/VOP_PWM_M0/MCU_JTAG_TRSTn/GPIO0_C3_d_AN38") (pintype "passive"))
    )
    (net (code "63") (name "/GPIO3_A1") (class "Default")
      (node (ref "J2") (pin "17") (pinfunction "17_17") (pintype "passive"))
      (node (ref "U1") (pin "1U5") (pinfunction "VOP_BT1120_D0/SPI1_CS0_M1/SDMMC2_D0_M1/GPIO3_A1_d_1U5") (pintype "passive"))
    )
    (net (code "64") (name "/GPIO3_A7") (class "Default")
      (node (ref "J2") (pin "16") (pinfunction "16_16") (pintype "passive"))
      (node (ref "U1") (pin "1V3") (pinfunction "VOP_BT1120_D5/GMAC1_RXCLK_M0/SDMMC2_DET_M1/GPIO3_A7_d_1V3") (pintype "passive"))
    )
    (net (code "65") (name "/GPIO3_B0") (class "Default")
      (node (ref "U1") (pin "AR7") (pinfunction "VOP_BT1120_D6/ETH1_REFCLKO_25M_M0/SDMMC2_PWREN_M1/GPIO3_B0_d_AR7") (pintype "passive"))
    )
    (net (code "66") (name "/GPIO3_B3") (class "Default")
      (node (ref "J2") (pin "19") (pinfunction "19_19") (pintype "passive"))
      (node (ref "U1") (pin "AP6") (pinfunction "VOP_BT1120_D9/GMAC1_RXDV_CRS_M0/I2C5_SCL_M0/PDM_SDI0_M2/GPIO3_B3_d_AP6") (pintype "passive"))
    )
    (net (code "67") (name "/GPIO3_B4") (class "Default")
      (node (ref "J2") (pin "21") (pinfunction "21_21") (pintype "passive"))
      (node (ref "U1") (pin "1U3") (pinfunction "VOP_BT1120_D10/GMAC1_RXER_M0/I2C5_SDA_M0/PDM_SDI1_M2/GPIO3_B4_d_1U3") (pintype "passive"))
    )
    (net (code "68") (name "/GPIO3_B5") (class "Default")
      (node (ref "J2") (pin "20") (pinfunction "20_20") (pintype "passive"))
      (node (ref "U1") (pin "1T4") (pinfunction "VOP_BT1120_D11/GMAC1_TXD0_M0/I2C3_SCL_M1/PWM10_M0/GPIO3_B5_d_1T4") (pintype "passive"))
    )
    (net (code "69") (name "/GPIO3_B6") (class "Default")
      (node (ref "J2") (pin "22") (pinfunction "22_22") (pintype "passive"))
      (node (ref "U1") (pin "1V2") (pinfunction "VOP_BT1120_D12/GMAC1_TXD1_M0/I2C3_SDA_M1/PWM11_IR_M0/GPIO3_B6_d_1V2") (pintype "passive"))
    )
    (net (code "70") (name "/GPIO3_C1") (class "Default")
      (node (ref "J2") (pin "18") (pinfunction "18_18") (pintype "passive"))
      (node (ref "U1") (pin "AP4") (pinfunction "VOP_BT1120_D13/SPI1_MOSI_M1/PCIE20_PERSTn_M1/I2S1_SDO2_M2/GPIO3_C1_d_AP4") (pintype "passive"))
    )
    (net (code "71") (name "/HDMITX_CEC") (class "Default")
      (node (ref "U1") (pin "1V5") (pinfunction "HDMITX_CEC_M0/SPI3_CS1_M1/GPIO4_D1_u_1V5") (pintype "passive"))
    )
    (net (code "72") (name "/HDMITX_SCL") (class "Default")
      (node (ref "U1") (pin "AR12") (pinfunction "HDMITX_SCL/I2C5_SCL_M1/GPIO4_C7_u_AR12") (pintype "passive"))
    )
    (net (code "73") (name "/HDMITX_SDA") (class "Default")
      (node (ref "U1") (pin "AP11") (pinfunction "HDMITX_SDA/I2C5_SDA_M1/GPIO4_D0_u_AP11") (pintype "passive"))
    )
    (net (code "74") (name "/HDMI_REXT") (class "Default")
      (node (ref "R10") (pin "2") (pinfunction "2_2") (pintype "passive"))
      (node (ref "U1") (pin "1U16") (pinfunction "HDMI_TX_REXT_1U16") (pintype "passive"))
    )
    (net (code "75") (name "/HDMI_TX0_N") (class "Default")
      (node (ref "U1") (pin "AR33") (pinfunction "HDMI_TX_D0N_AR33") (pintype "passive"))
    )
    (net (code "76") (name "/HDMI_TX0_P") (class "Default")
      (node (ref "U1") (pin "AP33") (pinfunction "HDMI_TX_D0P_AP33") (pintype "passive"))
    )
    (net (code "77") (name "/HDMI_TX1_N") (class "Default")
      (node (ref "U1") (pin "AP35") (pinfunction "HDMI_TX_D1N_AP35") (pintype "passive"))
    )
    (net (code "78") (name "/HDMI_TX1_P") (class "Default")
      (node (ref "U1") (pin "AR35") (pinfunction "HDMI_TX_D1P_AR35") (pintype "passive"))
    )
    (net (code "79") (name "/HDMI_TX2_N") (class "Default")
      (node (ref "U1") (pin "AR36") (pinfunction "HDMI_TX_D2N_AR36") (pintype "passive"))
    )
    (net (code "80") (name "/HDMI_TX2_P") (class "Default")
      (node (ref "U1") (pin "AP36") (pinfunction "HDMI_TX_D2P_AP36") (pintype "passive"))
    )
    (net (code "81") (name "/HDMI_TXCLK_N") (class "Default")
      (node (ref "U1") (pin "AP32") (pinfunction "HDMI_TX_CLKN_AP32") (pintype "passive"))
    )
    (net (code "82") (name "/HDMI_TXCLK_P") (class "Default")
      (node (ref "U1") (pin "AR32") (pinfunction "HDMI_TX_CLKP_AR32") (pintype "passive"))
    )
    (net (code "83") (name "/HDMI_TX_HPDIN") (class "Default")
      (node (ref "C60") (pin "1") (pinfunction "1_1") (pintype "passive"))
      (node (ref "U1") (pin "1V17") (pinfunction "HDMI_TX_HPDIN_1V17") (pintype "passive"))
    )
    (net (code "84") (name "/HOST_WAKE_BT") (class "Default")
      (node (ref "U1") (pin "B36") (pinfunction "I2S2_MCLK_M0/ETH0_REFCLKO_25M/UART7_RTSn_M0/SPI2_CLK_M0/GPIO2_C1_d_B36") (pintype "passive"))
    )
    (net (code "85") (name "/I2C0_SCL_PMIC") (class "Default")
      (node (ref "U1") (pin "AJ37") (pinfunction "I2C0_SCL/GPIO0_B1_u_AJ37") (pintype "passive"))
    )
    (net (code "86") (name "/I2C0_SDA_PMIC") (class "Default")
      (node (ref "U1") (pin "AK38") (pinfunction "I2C0_SDA/GPIO0_B2_u_AK38") (pintype "passive"))
    )
    (net (code "87") (name "/I2C1_SCL_JTAG_TDO") (class "Default")
      (node (ref "J2") (pin "11") (pinfunction "11_11") (pintype "passive"))
      (node (ref "U1") (pin "AK37") (pinfunction "I2C1_SCL/MCU_JTAG_TDO/GPIO0_B3_u_AK37") (pintype "passive"))
    )
    (net (code "88") (name "/I2C1_SDA_JTAG_TCK") (class "Default")
      (node (ref "J2") (pin "12") (pinfunction "12_12") (pintype "passive"))
      (node (ref "U1") (pin "AM38") (pinfunction "I2C1_SDA/PCIE20_BUTTONRSTn/MCU_JTAG_TCK/GPIO0_B4_u_AM38") (pintype "passive"))
    )
    (net (code "89") (name "/I2C2_SCL") (class "Default")
      (node (ref "U1") (pin "AD1") (pinfunction "I2C2_SCL_M1/EBC_SDSHR/I2S1_SDO3_M1/GPIO4_B5_d_AD1") (pintype "passive"))
    )
    (net (code "90") (name "/I2C2_SDA") (class "Default")
      (node (ref "U1") (pin "AF1") (pinfunction "I2C2_SDA_M1/EBC_GDSP/ISP_FLASH_TRIGIN/VOP_BT656_CLK_M1/GPIO4_B4_d_AF1") (pintype "passive"))
    )
    (net (code "91") (name "/I2C3_SCL_UART3_TX") (class "Default")
      (node (ref "J2") (pin "10") (pinfunction "10_10") (pintype "passive"))
      (node (ref "U1") (pin "B22") (pinfunction "I2C3_SCL_M0/UART3_TX_M0/AUDIOPWM_LOUT_N/GPIO1_A1_u_B22") (pintype "passive"))
    )
    (net (code "92") (name "/I2C3_SDA_UART3_RX") (class "Default")
      (node (ref "J2") (pin "9") (pinfunction "9_9") (pintype "passive"))
      (node (ref "U1") (pin "A22") (pinfunction "I2C3_SDA_M0/UART3_RX_M0/AUDIOPWM_LOUT_P/GPIO1_A0_u_A22") (pintype "passive"))
    )
    (net (code "93") (name "/I2S_LRCK") (class "Default")
      (node (ref "U1") (pin "AR9") (pinfunction "VOP_BT1120_D3/GMAC1_RXD2_M0/I2S3_LRCK_M0/SDMMC2_D3_M1/GPIO3_A4_d_AR9") (pintype "passive"))
    )
    (net (code "94") (name "/I2S_MCLK") (class "Default")
      (node (ref "U1") (pin "AR10") (pinfunction "VOP_BT1120_D1/GMAC1_TXD2_M0/I2S3_MCLK_M0/SDMMC2_D1_M1/GPIO3_A2_d_AR10") (pintype "passive"))
    )
    (net (code "95") (name "/I2S_SCLK") (class "Default")
      (node (ref "U1") (pin "AP10") (pinfunction "VOP_BT1120_D2/GMAC1_TXD3_M0/I2S3_SCLK_M0/SDMMC2_D2_M1/GPIO3_A3_d_AP10") (pintype "passive"))
    )
    (net (code "96") (name "/I2S_SDI") (class "Default")
      (node (ref "U1") (pin "1U4") (pinfunction "VOP_BT1120_CLK/GMAC1_TXCLK_M0/I2S3_SDI_M0/SDMMC2_CLK_M1/GPIO3_A6_d_1U4") (pintype "passive"))
    )
    (net (code "97") (name "/I2S_SDO") (class "Default")
      (node (ref "U1") (pin "AP9") (pinfunction "VOP_BT1120_D4/GMAC1_RXD3_M0/I2S3_SDO_M0/SDMMC2_CMD_M1/GPIO3_A5_d_AP9") (pintype "passive"))
    )
    (net (code "98") (name "/LEDDRV_DCLK") (class "Default")
      (node (ref "U1") (pin "1U6") (pinfunction "PWM12_M1/SPI3_MISO_M1/SATA1_ACT_LED/UART9_TX_M1/I2S3_SDO_M1/GPIO4_C5_d_1U6") (pintype "passive"))
    )
    (net (code "99") (name "/LEDDRV_DIN") (class "Default")
      (node (ref "U1") (pin "1T6") (pinfunction "PWM13_M1/SPI3_CS0_M1/SATA0_ACT_LED/UART9_RX_M1/I2S3_SDI_M1/GPIO4_C6_d_1T6") (pintype "passive"))
    )
    (net (code "100") (name "/LPDDR4_A_DQ0") (class "Default")
      (node (ref "U1") (pin "G2") (pinfunction "DDR_DQ0_A/DDR4_DQL0_A/LPDDR4_DQ0_A/DDR3_DQ0/LPDDR3_DQ15_G2") (pintype "passive"))
    )
    (net (code "101") (name "/LPDDR4_A_DQ1") (class "Default")
      (node (ref "U1") (pin "F2") (pinfunction "DDR_DQ1_A/DDR4_DQL2_A/LPDDR4_DQ1_A/DDR3_DQ1/LPDDR3_DQ14_F2") (pintype "passive"))
    )
    (net (code "102") (name "/LPDDR4_A_DQ2") (class "Default")
      (node (ref "U1") (pin "F1") (pinfunction "DDR_DQ2_A/DDR4_DQL4_A/LPDDR4_DQ2_A/DDR3_DQ2/LPDDR3_DQ10_F1") (pintype "passive"))
    )
    (net (code "103") (name "/LPDDR4_A_DQ3") (class "Default")
      (node (ref "U1") (pin "E1") (pinfunction "DDR_DQ3_A/DDR4_DQL6_A/LPDDR4_DQ3_A/DDR3_DQ3/LPDDR3_DQ9_E1") (pintype "passive"))
    )
    (net (code "104") (name "/LPDDR4_A_DQ4") (class "Default")
      (node (ref "U1") (pin "M2") (pinfunction "DDR_DQ4_A/DDR4_DQL7_A/LPDDR4_DQ4_A/DDR3_DQ4/LPDDR3_DQ13_M2") (pintype "passive"))
    )
    (net (code "105") (name "/LPDDR4_A_DQ5") (class "Default")
      (node (ref "U1") (pin "K1") (pinfunction "DDR_DQ5_A/DDR4_DQL5_A/LPDDR4_DQ5_A/DDR3_DQ5/LPDDR3_DQ12_K1") (pintype "passive"))
    )
    (net (code "106") (name "/LPDDR4_A_DQ6") (class "Default")
      (node (ref "U1") (pin "K2") (pinfunction "DDR_DQ6_A/DDR4_DQL3_A/LPDDR4_DQ6_A/DDR3_DQ6/LPDDR3_DQ8_K2") (pintype "passive"))
    )
    (net (code "107") (name "/LPDDR4_A_DQ7") (class "Default")
      (node (ref "U1") (pin "1E1") (pinfunction "DDR_DQ7_A/DDR4_DQL1_A/LPDDR4_DQ7_A/DDR3_DQ7/LPDDR3_DQ11_1E1") (pintype "passive"))
    )
    (net (code "108") (name "/LPDDR4_A_DQ8") (class "Default")
      (node (ref "U1") (pin "P2") (pinfunction "DDR_DQ8_A/DDR4_DQU3_A/LPDDR4_DQ8_A/DDR3_DQ8/LPDDR3_DQ25_P2") (pintype "passive"))
    )
    (net (code "109") (name "/LPDDR4_A_DQ9") (class "Default")
      (node (ref "U1") (pin "R1") (pinfunction "DDR_DQ9_A/DDR4_DQU1_A/LPDDR4_DQ9_A/DDR3_DQ9/LPDDR3_DQ24_R1") (pintype "passive"))
    )
    (net (code "110") (name "/LPDDR4_A_DQ10") (class "Default")
      (node (ref "U1") (pin "R2") (pinfunction "DDR_DQ10_A/DDR4_DQU7_A/LPDDR4_DQ10_A/DDR3_DQ10/LPDDR3_DQ28_R2") (pintype "passive"))
    )
    (net (code "111") (name "/LPDDR4_A_DQ11") (class "Default")
      (node (ref "U1") (pin "T2") (pinfunction "DDR_DQ11_A/DDR4_DQU5_A/LPDDR4_DQ11_A/DDR3_DQ11/LPDDR3_DQ29_T2") (pintype "passive"))
    )
    (net (code "112") (name "/LPDDR4_A_DQ12") (class "Default")
      (node (ref "U1") (pin "M1") (pinfunction "DDR_DQ12_A/DDR4_DQU2_A/LPDDR4_DQ12_A/DDR3_DQ12/LPDDR3_DQ26_M1") (pintype "passive"))
    )
    (net (code "113") (name "/LPDDR4_A_DQ13") (class "Default")
      (node (ref "U1") (pin "1F2") (pinfunction "DDR_DQ13_A/DDR4_DQU4_A/LPDDR4_DQ13_A/DDR3_DQ13/LPDDR3_DQ31_1F2") (pintype "passive"))
    )
    (net (code "114") (name "/LPDDR4_A_DQ14") (class "Default")
      (node (ref "U1") (pin "1F1") (pinfunction "DDR_DQ14_A/DDR4_DQU6_A/LPDDR4_DQ14_A/DDR3_DQ14/LPDDR3_DQ30_1F1") (pintype "passive"))
    )
    (net (code "115") (name "/LPDDR4_A_DQ15") (class "Default")
      (node (ref "U1") (pin "1G2") (pinfunction "DDR_DQ15_A/DDR4_DQU0_A/LPDDR4_DQ15_A/DDR3_DQ15/LPDDR3_DQ27_1G2") (pintype "passive"))
    )
    (net (code "116") (name "/LPDDR4_A_DQM0") (class "Default")
      (node (ref "U1") (pin "1E2") (pinfunction "DDR_DM0_A/DDR4_DML_A/LPDDR4_DM0_A/DDR3_DM0/LPDDR3_DM1_1E2") (pintype "passive"))
    )
    (net (code "117") (name "/LPDDR4_A_DQM1") (class "Default")
      (node (ref "U1") (pin "1G1") (pinfunction "DDR_DM1_A/DDR4_DMU_A/LPDDR4_DM1_A/DDR3_DM1/LPDDR3_DM3_1G1") (pintype "passive"))
    )
    (net (code "118") (name "/LPDDR4_A_DQS0_N") (class "Default")
      (node (ref "U1") (pin "H1") (pinfunction "DDR_DQS0N_A/DDR4_DQSL_N_A/LPDDR4_DQS0N_A/DDR3_DQS0N/LPDDR3_DQS1N_H1") (pintype "passive"))
    )
    (net (code "119") (name "/LPDDR4_A_DQS0_P") (class "Default")
      (node (ref "U1") (pin "H2") (pinfunction "DDR_DQS0P_A/DDR4_DQSL_P_A/LPDDR4_DQS0P_A/DDR3_DQS0P/LPDDR3_DQS1P_H2") (pintype "passive"))
    )
    (net (code "120") (name "/LPDDR4_A_DQS1_N") (class "Default")
      (node (ref "U1") (pin "N2") (pinfunction "DDR_DQS1N_A/DDR4_DQSU_N_A/LPDDR4_DQS1N_A/DDR3_DQS1N/LPDDR3_DQS3N_N2") (pintype "passive"))
    )
    (net (code "121") (name "/LPDDR4_A_DQS1_P") (class "Default")
      (node (ref "U1") (pin "N1") (pinfunction "DDR_DQS1P_A/DDR4_DQSU_P_A/LPDDR4_DQS1P_A/DDR3_DQS1P/LPDDR3_DQS3P_N1") (pintype "passive"))
    )
    (net (code "124") (name "/LPDDR4_B_DQ0") (class "Default")
      (node (ref "U1") (pin "B12") (pinfunction "DDR_DQ0_B/DDR4_DQU7_B/LPDDR4_DQ0_B/DDR3_DQ16/LPDDR3_DQ1_B12") (pintype "passive"))
    )
    (net (code "125") (name "/LPDDR4_B_DQ1") (class "Default")
      (node (ref "U1") (pin "B10") (pinfunction "DDR_DQ1_B/DDR4_DQU5_B/LPDDR4_DQ1_B/DDR3_DQ17/LPDDR3_DQ5_B10") (pintype "passive"))
    )
    (net (code "126") (name "/LPDDR4_B_DQ2") (class "Default")
      (node (ref "U1") (pin "1A8") (pinfunction "DDR_DQ2_B/DDR4_DQU3_B/LPDDR4_DQ2_B/DDR3_DQ18/LPDDR3_DQ6_1A8") (pintype "passive"))
    )
    (net (code "127") (name "/LPDDR4_B_DQ3") (class "Default")
      (node (ref "U1") (pin "1A7") (pinfunction "DDR_DQ3_B/DDR4_DQU1_B/LPDDR4_DQ3_B/DDR3_DQ19/LPDDR3_DQ4_1A7") (pintype "passive"))
    )
    (net (code "128") (name "/LPDDR4_B_DQ4") (class "Default")
      (node (ref "U1") (pin "B13") (pinfunction "DDR_DQ4_B/DDR4_DQU0_B/LPDDR4_DQ4_B/DDR3_DQ20/LPDDR3_DQ2_B13") (pintype "passive"))
    )
    (net (code "129") (name "/LPDDR4_B_DQ5") (class "Default")
      (node (ref "U1") (pin "1A10") (pinfunction "DDR_DQ5_B/DDR4_DQU6_B/LPDDR4_DQ5_B/DDR3_DQ21/LPDDR3_DQ3_1A10") (pintype "passive"))
    )
    (net (code "130") (name "/LPDDR4_B_DQ6") (class "Default")
      (node (ref "U1") (pin "1B9") (pinfunction "DDR_DQ6_B/DDR4_DQU4_B/LPDDR4_DQ6_B/DDR3_DQ22/LPDDR3_DQ7_1B9") (pintype "passive"))
    )
    (net (code "131") (name "/LPDDR4_B_DQ7") (class "Default")
      (node (ref "U1") (pin "1A9") (pinfunction "DDR_DQ7_B/DDR4_DQU2_B/LPDDR4_DQ7_B/DDR3_DQ23/LPDDR3_DQ0_1A9") (pintype "passive"))
    )
    (net (code "132") (name "/LPDDR4_B_DQ8") (class "Default")
      (node (ref "U1") (pin "B19") (pinfunction "DDR_DQ8_B/DDR4_DQL0_B/LPDDR4_DQ8_B/DDR3_DQ24/LPDDR3_DQ18_B19") (pintype "passive"))
    )
    (net (code "133") (name "/LPDDR4_B_DQ9") (class "Default")
      (node (ref "U1") (pin "A19") (pinfunction "DDR_DQ9_B/DDR4_DQL2_B/LPDDR4_DQ9_B/DDR3_DQ25/LPDDR3_DQ19_A19") (pintype "passive"))
    )
    (net (code "134") (name "/LPDDR4_B_DQ10") (class "Default")
      (node (ref "U1") (pin "A20") (pinfunction "DDR_DQ10_B/DDR4_DQL4_B/LPDDR4_DQ10_B/DDR3_DQ26/LPDDR3_DQ22_A20") (pintype "passive"))
    )
    (net (code "135") (name "/LPDDR4_B_DQ11") (class "Default")
      (node (ref "U1") (pin "B20") (pinfunction "DDR_DQ11_B/DDR4_DQL6_B/LPDDR4_DQ11_B/DDR3_DQ27/LPDDR3_DQ23_B20") (pintype "passive"))
    )
    (net (code "136") (name "/LPDDR4_B_DQ12") (class "Default")
      (node (ref "U1") (pin "A15") (pinfunction "DDR_DQ12_B/DDR4_DQL7_B/LPDDR4_DQ12_B/DDR3_DQ28/LPDDR3_DQ16_A15") (pintype "passive"))
    )
    (net (code "137") (name "/LPDDR4_B_DQ13") (class "Default")
      (node (ref "U1") (pin "B15") (pinfunction "DDR_DQ13_B/DDR4_DQL5_B/LPDDR4_DQ13_B/DDR3_DQ29/LPDDR3_DQ17_B15") (pintype "passive"))
    )
    (net (code "138") (name "/LPDDR4_B_DQ14") (class "Default")
      (node (ref "U1") (pin "1C10") (pinfunction "DDR_DQ14_B/DDR4_DQL1_B/LPDDR4_DQ14_B/DDR3_DQ30/LPDDR3_DQ20_1C10") (pintype "passive"))
    )
    (net (code "139") (name "/LPDDR4_B_DQ15") (class "Default")
      (node (ref "U1") (pin "B16") (pinfunction "DDR_DQ15_B/DDR4_DQL3_B/LPDDR4_DQ15_B/DDR3_DQ31/LPDDR3_DQ21_B16") (pintype "passive"))
    )
    (net (code "140") (name "/LPDDR4_B_DQM0") (class "Default")
      (node (ref "U1") (pin "1B8") (pinfunction "DDR_DM0_B/DDR4_DMU_B/LPDDR4_DM0_B/DDR3_DM2/LPDDR3_DM0_1B8") (pintype "passive"))
    )
    (net (code "141") (name "/LPDDR4_B_DQM1") (class "Default")
      (node (ref "U1") (pin "1A11") (pinfunction "DDR_DM1_B/DDR4_DML_B/LPDDR4_DM1_B/DDR3_DM3/LPDDR3_DM2_1A11") (pintype "passive"))
    )
    (net (code "142") (name "/LPDDR4_B_DQS0_N") (class "Default")
      (node (ref "U1") (pin "A12") (pinfunction "DDR_DQS0N_B/DDR4_DQSU_N_B/LPDDR4_DQS0N_B/DDR3_DQS2N/LPDDR3_DQS0N_A12") (pintype "passive"))
    )
    (net (code "143") (name "/LPDDR4_B_DQS0_P") (class "Default")
      (node (ref "U1") (pin "A13") (pinfunction "DDR_DQS0P_B/DDR4_DQSU_P_B/LPDDR4_DQS0P_B/DDR3_DQS2P/LPDDR3_DQS0P_A13") (pintype "passive"))
    )
    (net (code "144") (name "/LPDDR4_B_DQS1_N") (class "Default")
      (node (ref "U1") (pin "B17") (pinfunction "DDR_DQS1N_B/DDR4_DQSL_N_B/LPDDR4_DQS1N_B/DDR3_DQS3N/LPDDR3_DQS2N_B17") (pintype "passive"))
    )
    (net (code "145") (name "/LPDDR4_B_DQS1_P") (class "Default")
      (node (ref "U1") (pin "A17") (pinfunction "DDR_DQS1P_B/DDR4_DQSL_P_B/LPDDR4_DQS1P_B/DDR3_DQS3P/LPDDR3_DQS2P_A17") (pintype "passive"))
    )
    (net (code "148") (name "/LPDDR4_CAA0") (class "Default")
      (node (ref "U1") (pin "C2") (pinfunction "DDR4_A11/LPDDR4_A0_A/DDR3_A7/LPDDR3_A8/AC11_C2") (pintype "passive"))
    )
    (net (code "149") (name "/LPDDR4_CAA1") (class "Default")
      (node (ref "U1") (pin "C1") (pinfunction "DDR4_A2/LPDDR4_A1_A/DDR3_A4/LPDDR3_A6/AC2_C1") (pintype "passive"))
    )
    (net (code "150") (name "/LPDDR4_CAA2") (class "Default")
      (node (ref "U1") (pin "1C1") (pinfunction "DDR4_A15_CASn/LPDDR4_A2_A/DDR3_A0/-/AC15_1C1") (pintype "passive"))
    )
    (net (code "151") (name "/LPDDR4_CAA3") (class "Default")
      (node (ref "U1") (pin "1B3") (pinfunction "DDR4_A12/LPDDR4_A3_A/DDR3_BA2/-/AC12_1B3") (pintype "passive"))
    )
    (net (code "152") (name "/LPDDR4_CAA4") (class "Default")
      (node (ref "U1") (pin "1B1") (pinfunction "DDR4_A14_WEn/LPDDR4_A4_A/DDR3_A15/LPDDR3_A5/AC14_1B1") (pintype "passive"))
    )
    (net (code "153") (name "/LPDDR4_CAA5") (class "Default")
      (node (ref "U1") (pin "1A1") (pinfunction "DDR4_A16_RASn/LPDDR4_A5_A/DDR3_RASn/LPDDR3_A7/AC16_1A1") (pintype "passive"))
    )
    (net (code "155") (name "/LPDDR4_CAB0") (class "Default")
      (node (ref "U1") (pin "A9") (pinfunction "DDR4_A13/LPDDR4_A0_B/DDR3_A14/LPDDR3_A0/AC13_A9") (pintype "passive"))
    )
    (net (code "156") (name "/LPDDR4_CAB1") (class "Default")
      (node (ref "U1") (pin "B9") (pinfunction "DDR4_A6/LPDDR4_A1_B/DDR3_A13/LPDDR3_A1/AC6_B9") (pintype "passive"))
    )
    (net (code "157") (name "/LPDDR4_CAB2") (class "Default")
      (node (ref "U1") (pin "1B7") (pinfunction "DDR4_BA0/LPDDR4_A2_B/DDR3_A1/-/AC18_1B7") (pintype "passive"))
    )
    (net (code "158") (name "/LPDDR4_CAB3") (class "Default")
      (node (ref "U1") (pin "1B6") (pinfunction "DDR4_A4/LPDDR4_A3_B/DDR3_BA1/LPDDR3_A3/AC4_1B6") (pintype "passive"))
    )
    (net (code "159") (name "/LPDDR4_CAB4") (class "Default")
      (node (ref "U1") (pin "1A6") (pinfunction "DDR4_BA1/LPDDR4_A4_B/DDR3_A12/LPDDR3_A4/AC19_1A6") (pintype "passive"))
    )
    (net (code "160") (name "/LPDDR4_CAB5") (class "Default")
      (node (ref "U1") (pin "B8") (pinfunction "DDR4_A5/LPDDR4_A5_B/DDR3_A11/LPDDR3_A2/AC5_B8") (pintype "passive"))
    )
    (net (code "162") (name "/LPDDR4_CKEA0") (class "Default")
      (node (ref "U1") (pin "B4") (pinfunction "DDR4_CKE/LPDDR4_CKE0_A/DDR3_CKE/LPDDR3_CKE/AC22_B4") (pintype "passive"))
    )
    (net (code "163") (name "/LPDDR4_CKEA1") (class "Default")
      (node (ref "U1") (pin "1C3") (pinfunction "DDR4_A3/LPDDR4_CKE1_A/DDR3_A3/-/AC3_1C3") (pintype "passive"))
    )
    (net (code "165") (name "/LPDDR4_CKEB0") (class "Default")
      (node (ref "U1") (pin "1A3") (pinfunction "DDR4_A10/LPDDR4_CKE0_B/DDR3_A10/-/AC10_1A3") (pintype "passive"))
    )
    (net (code "166") (name "/LPDDR4_CKEB1") (class "Default")
      (node (ref "U1") (pin "1A2") (pinfunction "DDR4_ACTn/LPDDR4_CKE1_B/DDR3_CASn/-/AC17_1A2") (pintype "passive"))
    )
    (net (code "168") (name "/LPDDR4_CLKA_N") (class "Default")
      (node (ref "U1") (pin "B5") (pinfunction "DDR4_CLKN/LPDDR4_CLKN_A/DDR3_CLKN/LPDDR3_CLKN/AC24_B5") (pintype "passive"))
    )
    (net (code "169") (name "/LPDDR4_CLKA_P") (class "Default")
      (node (ref "U1") (pin "A5") (pinfunction "DDR4_CLKP/LPDDR4_CLKP_A/DDR3_CLKP/LPDDR3_CLKP/AC23_A5") (pintype "passive"))
    )
    (net (code "170") (name "/LPDDR4_CLKB_N") (class "Default")
      (node (ref "U1") (pin "B7") (pinfunction "DDR4_A9/LPDDR4_CLKN_B/DDR3_A5/-/AC9_B7") (pintype "passive"))
    )
    (net (code "171") (name "/LPDDR4_CLKB_P") (class "Default")
      (node (ref "U1") (pin "A7") (pinfunction "DDR4_A0/LPDDR4_CLKP_B/DDR3_A9/-/AC0_A7") (pintype "passive"))
    )
    (net (code "172") (name "/LPDDR4_CSA0") (class "Default")
      (node (ref "U1") (pin "B3") (pinfunction "DDR4_CS0n/LPDDR4_CS0n_A/DDR3_ODT1/LPDDR3_ODT0/AC25_B3") (pintype "passive"))
    )
    (net (code "173") (name "/LPDDR4_CSA1") (class "Default")
      (node (ref "U1") (pin "A3") (pinfunction "DDR4_CS1n/LPDDR4_CS1n_A/DDR3_CS1n/LPDDR3_ODT1/AC26_A3") (pintype "passive"))
    )
    (net (code "175") (name "/LPDDR4_CSB0") (class "Default")
      (node (ref "U1") (pin "1B5") (pinfunction "DDR4_ODT1/LPDDR4_CS0n_B/DDR3_CS0n/LPDDR3_CS0n/AC28_1B5") (pintype "passive"))
    )
    (net (code "176") (name "/LPDDR4_CSB1") (class "Default")
      (node (ref "U1") (pin "1A5") (pinfunction "DDR4_ODT0/LPDDR4_CS1n_B/DDR3_ODT0/LPDDR3_CS1n/AC27_1A5") (pintype "passive"))
    )
    (net (code "178") (name "/LPDDR4_ODT_CAA") (class "Default")
      (node (ref "U1") (pin "E2") (pinfunction "DDR4_A8/LPDDR4_ODT0_CA_A/DDR3_A6/LPDDR3_A9/AC8_E2") (pintype "passive"))
    )
    (net (code "179") (name "/LPDDR4_ODT_CAB") (class "Default")
      (node (ref "U1") (pin "A10") (pinfunction "DDR4_A7/LPDDR4_ODT0_CA_B/DDR3_A8/-/AC7_A10") (pintype "passive"))
    )
    (net (code "180") (name "/LPDDR4_RST#") (class "Default")
      (node (ref "U1") (pin "1C7") (pinfunction "DDR4_RESETn/LPDDR4_RESETn/DDR3_RESETn/AC29_1C7") (pintype "passive"))
    )
    (net (code "181") (name "/LPDDR4_RZQ") (class "Default")
      (node (ref "R4") (pin "2") (pinfunction "2_2") (pintype "passive"))
      (node (ref "U1") (pin "1F3") (pinfunction "DDR_RZQ_1F3") (pintype "passive"))
    )
    (net (code "182") (name "/MIC_PDM_CLK0") (class "Default")
      (node (ref "U1") (pin "1A14") (pinfunction "I2S1_LRCK_RX_M0/UART4_TX_M0/PDM_CLK0_M0/AUDIOPWM_ROUT_P/GPIO1_A6_d_1A14") (pintype "passive"))
    )
    (net (code "183") (name "/MIC_PDM_SDI0") (class "Default")
      (node (ref "U1") (pin "1B14") (pinfunction "I2S1_SDI0_M0/PDM_SDI0_M0/GPIO1_B3_d_1B14") (pintype "passive"))
    )
    (net (code "184") (name "/MIC_PDM_SDI1") (class "Default")
      (node (ref "U1") (pin "B26") (pinfunction "I2S1_SDO3_M0/I2S1_SDI1_M0/PDM_SDI1_M0/PCIE20_PERSTn_M2/GPIO1_B2_d_B26") (pintype "passive"))
    )
    (net (code "185") (name "/MIC_PDM_SDI2") (class "Default")
      (node (ref "U1") (pin "A26") (pinfunction "I2S1_SDO2_M0/I2S1_SDI2_M0/PDM_SDI2_M0/PCIE20_WAKEn_M2/GPIO1_B1_d_A26") (pintype "passive"))
    )
    (net (code "186") (name "/MIC_PDM_SDI3") (class "Default")
      (node (ref "U1") (pin "1B13") (pinfunction "I2S1_SDO1_M0/I2S1_SDI3_M0/PDM_SDI3_M0/PCIE20_CLKREQn_M2/GPIO1_B0_d_1B13") (pintype "passive"))
    )
    (net (code "187") (name "/MPCIE_USB_N") (class "Default")
      (node (ref "U1") (pin "Y1") (pinfunction "USB_HOST3_DM_Y1") (pintype "passive"))
    )
    (net (code "188") (name "/MPCIE_USB_P") (class "Default")
      (node (ref "U1") (pin "Y2") (pinfunction "USB_HOST3_DP_Y2") (pintype "passive"))
    )
    (net (code "189") (name "/PCIE_REFCLK_N") (class "Default")
      (node (ref "U1") (pin "1K20") (pinfunction "PCIE20_REFCLKN_1K20") (pintype "passive"))
    )
    (net (code "190") (name "/PCIE_REFCLK_P") (class "Default")
      (node (ref "U1") (pin "1K19") (pinfunction "PCIE20_REFCLKP_1K19") (pintype "passive"))
    )
    (net (code "191") (name "/PCIE_RX_N") (class "Default")
      (node (ref "U1") (pin "AB38") (pinfunction "PCIE20_RXN/SATA2_RXN_AB38") (pintype "passive"))
    )
    (net (code "192") (name "/PCIE_RX_P") (class "Default")
      (node (ref "U1") (pin "AB37") (pinfunction "PCIE20_RXP/SATA2_RXP_AB37") (pintype "passive"))
    )
    (net (code "193") (name "/PCIE_TX_N") (class "Default")
      (node (ref "U1") (pin "AA38") (pinfunction "PCIE20_TXN/SATA2_TXN_AA38") (pintype "passive"))
    )
    (net (code "194") (name "/PCIE_TX_P") (class "Default")
      (node (ref "U1") (pin "AA37") (pinfunction "PCIE20_TXP/SATA2_TXP_AA37") (pintype "passive"))
    )
    (net (code "195") (name "/PDM_CLK") (class "Default")
      (node (ref "U1") (pin "1A13") (pinfunction "I2S1_SCLK_RX_M0/UART4_RX_M0/PDM_CLK1_M0/SPDIF_TX_M0/GPIO1_A4_d_1A13") (pintype "passive"))
    )
    (net (code "196") (name "/PMIC32KO_SOC") (class "Default")
      (node (ref "U1") (pin "1T20") (pinfunction "CLK32K_IN/CLK32K_OUT0/GPIO0_B0_u_1T20") (pintype "passive"))
    )
    (net (code "197") (name "/PMIC_INT_L") (class "Default")
      (node (ref "U1") (pin "1R19") (pinfunction "GPIO0_A3_u_1R19") (pintype "passive"))
    )
    (net (code "198") (name "/PMIC_SLEEP") (class "Default")
      (node (ref "U1") (pin "1P19") (pinfunction "PMIC_SLEEP/TSADC_SHUT_M1/GPIO0_A2_d_1P19") (pintype "passive"))
    )
    (net (code "199") (name "/PWM0_M0") (class "Default")
      (node (ref "J2") (pin "4") (pinfunction "4_4") (pintype "passive"))
      (node (ref "U1") (pin "1R17") (pinfunction "PWM0_M0/CPUAVS/GPIO0_B7_d_1R17") (pintype "passive"))
    )
    (net (code "200") (name "/PWM7_IR_RX") (class "Default")
      (node (ref "U1") (pin "1T18") (pinfunction "PWM7_IR/SPI0_CS0_M0/GPIO0_C6_d_1T18") (pintype "passive"))
    )
    (net (code "201") (name "/PWRUSBOTG") (class "Default")
      (node (ref "C34") (pin "1") (pinfunction "1_1") (pintype "passive"))
      (node (ref "R18") (pin "2") (pinfunction "2_2") (pintype "passive"))
      (node (ref "R19") (pin "1") (pinfunction "1_1") (pintype "passive"))
      (node (ref "U1") (pin "T38") (pinfunction "USB_OTG0_VBUSDET_T38") (pintype "passive"))
    )
    (net (code "202") (name "/PWR_USBOTG") (class "Default")
      (node (ref "R18") (pin "1") (pinfunction "1_1") (pintype "passive"))
    )
    (net (code "203") (name "/REFCLKO_25M") (class "Default")
      (node (ref "R11") (pin "1") (pinfunction "1_1") (pintype "passive"))
    )
    (net (code "204") (name "/RESET#") (class "Default")
      (node (ref "C4") (pin "2") (pinfunction "2_2") (pintype "passive"))
      (node (ref "R1") (pin "2") (pinfunction "2_2") (pintype "passive"))
      (node (ref "R2") (pin "1") (pinfunction "1_1") (pintype "passive"))
      (node (ref "U1") (pin "AG38") (pinfunction "nPOR_u_AG38") (pintype "passive"))
    )
    (net (code "206") (name "/SDMMC0_CLK") (class "Default")
      (node (ref "R6") (pin "1") (pinfunction "1_1") (pintype "passive"))
    )
    (net (code "207") (name "/SDMMC0_CMD") (class "Default")
      (node (ref "U1") (pin "1E19") (pinfunction "SDMMC0_CMD/PWM10_M1/UART5_RX_M0/GPIO2_A1_u_1E19") (pintype "passive"))
    )
    (net (code "208") (name "/SDMMC0_D0") (class "Default")
      (node (ref "U1") (pin "1E20") (pinfunction "SDMMC0_D0/UART2_TX_M1/UART6_TX_M1/PWM8_M1/GPIO1_D5_u_1E20") (pintype "passive"))
    )
    (net (code "209") (name "/SDMMC0_D1") (class "Default")
      (node (ref "U1") (pin "1F19") (pinfunction "SDMMC0_D1/UART2_RX_M1/UART6_RX_M1/PWM9_M1/GPIO1_D6_u_1F19") (pintype "passive"))
    )
    (net (code "210") (name "/SDMMC0_D2") (class "Default")
      (node (ref "U1") (pin "1D20") (pinfunction "SDMMC0_D2/ARM_JTAG_TCK/UART5_CTSn_M0/GPIO1_D7_u_1D20") (pintype "passive"))
    )
    (net (code "211") (name "/SDMMC0_D3") (class "Default")
      (node (ref "U1") (pin "1F18") (pinfunction "SDMMC0_D3/ARM_JTAG_TMS/UART5_RTSn_M0/GPIO2_A0_u_1F18") (pintype "passive"))
    )
    (net (code "212") (name "/SDMMC0_DET") (class "Default")
      (node (ref "U1") (pin "AF37") (pinfunction "SDMMC0_DET/SATA_CP_DET/GPIO0_A4_u_AF37") (pintype "passive"))
    )
    (net (code "213") (name "/SDMMC0_PWREN") (class "Default")
      (node (ref "U1") (pin "AG37") (pinfunction "SDMMC0_PWREN/SATA_MP_SWITCH/PCIE20_CLKREQn_M0/GPIO0_A5_d_AG37") (pintype "passive"))
    )
    (net (code "214") (name "/SPDIF_TX") (class "Default")
      (node (ref "U1") (pin "1V6") (pinfunction "EDP_HPDIN_M0/SPDIF_TX_M2/SATA2_ACT_LED/I2S3_LRCK_M1/GPIO4_C4_d_1V6") (pintype "passive"))
    )
    (net (code "215") (name "/SPI0_CS1") (class "Default")
      (node (ref "J2") (pin "7") (pinfunction "7_7") (pintype "passive"))
      (node (ref "U1") (pin "AN37") (pinfunction "PWM5/SPI0_CS1_M0/UART0_RTSn/GPIO0_C4_d_AN37") (pintype "passive"))
    )
    (net (code "216") (name "/SPI0_MISO") (class "Default")
      (node (ref "J2") (pin "8") (pinfunction "8_8") (pintype "passive"))
      (node (ref "U1") (pin "1U19") (pinfunction "PWM6/SPI0_MISO_M0/GPIO0_C5_d_1U19") (pintype "passive"))
    )
    (net (code "217") (name "/SPI0_MOSI") (class "Default")
      (node (ref "J2") (pin "6") (pinfunction "6_6") (pintype "passive"))
      (node (ref "U1") (pin "1R16") (pinfunction "I2C2_SDA_M0/SPI0_MOSI_M0/PCIE20_PERSTnM0/PWM2_M1/GPIO0_B6_u_1R16") (pintype "passive"))
    )
    (net (code "218") (name "/SPI0_SCK") (class "Default")
      (node (ref "J2") (pin "5") (pinfunction "5_5") (pintype "passive"))
      (node (ref "U1") (pin "1U20") (pinfunction "I2C2_SCL_M0/SPI0_CLK_M0/PCIE20_WAKEn_M0/PWM1_M1/GPIO0_B5_u_1U20") (pintype "passive"))
    )
    (net (code "219") (name "/STATUS_LED") (class "Default")
      (node (ref "R14") (pin "2") (pinfunction "2_2") (pintype "passive"))
      (node (ref "U1") (pin "1P18") (pinfunction "REFCLK_OUT/GPIO0_A0_d_1P18") (pintype "passive"))
    )
    (net (code "220") (name "/TSADC_SHUT_M0") (class "Default")
      (node (ref "R2") (pin "2") (pinfunction "2_2") (pintype "passive"))
      (node (ref "U1") (pin "1R20") (pinfunction "TSADC_SHUT_M0/TSADC_SHUT_ORG/GPIO0_A1_z_1R20") (pintype "passive"))
    )
    (net (code "221") (name "/UART2_RX_M0_DEBUG") (class "Default")
      (node (ref "D4") (pin "2") (pinfunction "2_2") (pintype "passive"))
      (node (ref "U1") (pin "1V19") (pinfunction "UART2_RX_M0/GPIO0_D0_u_1V19") (pintype "passive"))
    )
    (net (code "222") (name "/UART2_TX_M0_DEBUG") (class "Default")
      (node (ref "J1") (pin "2") (pinfunction "2_2") (pintype "passive"))
      (node (ref "U1") (pin "1U18") (pinfunction "UART2_TX_M0/GPIO0_D1_u_1U18") (pintype "passive"))
    )
    (net (code "223") (name "/UART3_RX") (class "Default")
      (node (ref "J2") (pin "25") (pinfunction "25_25") (pintype "passive"))
      (node (ref "U1") (pin "AR4") (pinfunction "PWM13_M0/GMAC1_MCLKINOUT_M0/UART3_RX_M1/PDM_SDI3_M2/GPIO3_C0_d_AR4") (pintype "passive"))
    )
    (net (code "224") (name "/UART3_TX") (class "Default")
      (node (ref "J2") (pin "23") (pinfunction "23_23") (pintype "passive"))
      (node (ref "U1") (pin "AP5") (pinfunction "PWM12_M0/GMAC1_TXEN_M0/UART3_TX_M1/PDM_SDI2_M2/GPIO3_B7_d_AP5") (pintype "passive"))
    )
    (net (code "225") (name "/UART4_RX") (class "Default")
      (node (ref "J2") (pin "27") (pinfunction "27_27") (pintype "passive"))
      (node (ref "U1") (pin "AP7") (pinfunction "VOP_BT1120_D7/GMAC1_RXD0_M0/UART4_RX_M1/PWM8_M0/GPIO3_B1_d_AP7") (pintype "passive"))
    )
    (net (code "226") (name "/UART4_TX") (class "Default")
      (node (ref "J2") (pin "29") (pinfunction "29_29") (pintype "passive"))
      (node (ref "U1") (pin "AR6") (pinfunction "VOP_BT1120_D8/GMAC1_RXD1_M0/UART4_TX_M1/PWM9_M0/GPIO3_B2_d_AR6") (pintype "passive"))
    )
    (net (code "227") (name "/UART5_RX") (class "Default")
      (node (ref "J2") (pin "26") (pinfunction "26_26") (pintype "passive"))
      (node (ref "U1") (pin "AR2") (pinfunction "VOP_BT1120_D15/SPI1_CLK_M1/UART5_RX_M1/I2S1_SCLK_RX_M2/GPIO3_C3_d_AR2") (pintype "passive"))
    )
    (net (code "228") (name "/UART5_TX") (class "Default")
      (node (ref "J2") (pin "24") (pinfunction "24_24") (pintype "passive"))
      (node (ref "U1") (pin "AP3") (pinfunction "VOP_BT1120_D14/SPI1_MISO_M1/UART5_TX_M1/I2S1_SDO3_M2/GPIO3_C2_d_AP3") (pintype "passive"))
    )
    (net (code "229") (name "/UART7_RX") (class "Default")
      (node (ref "J2") (pin "30") (pinfunction "30_30") (pintype "passive"))
      (node (ref "U1") (pin "1P4") (pinfunction "PWM15_IR_M0/SPDIF_TX_M1/GMAC1_MDIO_M0/UART7_RX_M1/I2S1_LRCK_RX_M2/GPIO3_C5_d_1P4") (pintype "passive"))
    )
    (net (code "230") (name "/UART7_TX") (class "Default")
      (node (ref "J2") (pin "28") (pinfunction "28_28") (pintype "passive"))
      (node (ref "U1") (pin "1P3") (pinfunction "PWM14_M0/VOP_PWM_M1/GMAC1_MDC_M0/UART7_TX_M1/PDM_CLK1_M2/GPIO3_C4_d_1P3") (pintype "passive"))
    )
    (net (code "231") (name "/URT_BTCTS_MRTS") (class "Default")
      (node (ref "U1") (pin "F37") (pinfunction "UART1_RTSn_M0/SPI1_CLK_M0/GPIO2_B5_u_F37") (pintype "passive"))
    )
    (net (code "232") (name "/URT_BTRTS_MCTS") (class "Default")
      (node (ref "U1") (pin "G37") (pinfunction "UART1_CTSn_M0/SPI1_MISO_M0/GPIO2_B6_u_G37") (pintype "passive"))
    )
    (net (code "233") (name "/URT_BTRX_MTX") (class "Default")
      (node (ref "U1") (pin "F38") (pinfunction "UART1_TX_M0/GPIO2_B4_u_F38") (pintype "passive"))
    )
    (net (code "234") (name "/URT_BTTX_MRX") (class "Default")
      (node (ref "U1") (pin "1C20") (pinfunction "UART1_RX_M0/GPIO2_B3_u_1C20") (pintype "passive"))
    )
    (net (code "235") (name "/USB3_HST1_D_N") (class "Default")
      (node (ref "U1") (pin "1J20") (pinfunction "USB3_HOST1_DM_1J20") (pintype "passive"))
    )
    (net (code "236") (name "/USB3_HST1_D_P") (class "Default")
      (node (ref "U1") (pin "1J19") (pinfunction "USB3_HOST1_DP_1J19") (pintype "passive"))
    )
    (net (code "237") (name "/USB3_HST1_SSRX_N") (class "Default")
      (node (ref "U1") (pin "V37") (pinfunction "USB3_HOST1_SSRXN/SATA1_RXN_V37") (pintype "passive"))
    )
    (net (code "238") (name "/USB3_HST1_SSRX_P") (class "Default")
      (node (ref "U1") (pin "V38") (pinfunction "USB3_HOST1_SSRXP/SATA1_RXP_V38") (pintype "passive"))
    )
    (net (code "239") (name "/USB3_HST1_SSTX_N") (class "Default")
      (node (ref "U1") (pin "W38") (pinfunction "USB3_HOST1_SSTXN/SATA1_TXN_W38") (pintype "passive"))
    )
    (net (code "240") (name "/USB3_HST1_SSTX_P") (class "Default")
      (node (ref "U1") (pin "W37") (pinfunction "USB3_HOST1_SSTXP/SATA1_TXP_W37") (pintype "passive"))
    )
    (net (code "241") (name "/USBHST_PWREN") (class "Default")
      (node (ref "U1") (pin "AJ38") (pinfunction "GPU_PWREN/SATA_CP_POD/GPIO0_A6_d_AJ38") (pintype "passive"))
    )
    (net (code "242") (name "/USBOTG_PWREN") (class "Default")
      (node (ref "U1") (pin "1V20") (pinfunction "HDMITX_CEC_M1/PWM0_M1/UART0_CTSn/GPIO0_C7_d_1V20") (pintype "passive"))
    )
    (net (code "243") (name "/USB_OTG0_D_N") (class "Default")
      (node (ref "U1") (pin "R38") (pinfunction "USB_OTG0_DM_R38") (pintype "passive"))
    )
    (net (code "244") (name "/USB_OTG0_D_P") (class "Default")
      (node (ref "U1") (pin "R37") (pinfunction "USB_OTG0_DP_R37") (pintype "passive"))
    )
    (net (code "245") (name "/USB_OTG0_ID") (class "Default")
      (node (ref "TP1") (pin "1") (pinfunction "1_1") (pintype "passive"))
      (node (ref "U1") (pin "T37") (pinfunction "USB_OTG0_ID_T37") (pintype "passive"))
    )
    (net (code "246") (name "/VREFO_DDR") (class "Default")
      (node (ref "C11") (pin "1") (pinfunction "1_1") (pintype "passive"))
      (node (ref "C9") (pin "2") (pinfunction "2_2") (pintype "passive"))
      (node (ref "U1") (pin "1H3") (pinfunction "DDR_VREFOUT_1H3") (pintype "passive"))
    )
    (net (code "247") (name "/WIFI_REG_ON") (class "Default")
      (node (ref "U1") (pin "A35") (pinfunction "SDMMC1_PWREN/I2C4_SDA_M1/UART8_RTSn_M0/GPIO2_B1_d_A35") (pintype "passive"))
    )
    (net (code "248") (name "/WIFI_WAKE_HOST") (class "Default")
      (node (ref "U1") (pin "B34") (pinfunction "SDMMC1_DET/I2C4_SCL_M1/UART8_CTSn_M0/GPIO2_B2_u_B34") (pintype "passive"))
    )
    (net (code "249") (name "/WL_SD_CLK") (class "Default")
      (node (ref "U1") (pin "B37") (pinfunction "SDMMC1_CLK/UART9_TX_M0/GPIO2_B0_d_B37") (pintype "passive"))
    )
    (net (code "250") (name "/WL_SD_CMD") (class "Default")
      (node (ref "U1") (pin "B35") (pinfunction "SDMMC1_CMD/UART9_RX_M0/GPIO2_A7_u_B35") (pintype "passive"))
    )
    (net (code "251") (name "/WL_SD_D0") (class "Default")
      (node (ref "U1") (pin "1C19") (pinfunction "SDMMC1_D0/UART6_RX_M0/GPIO2_A3_u_1C19") (pintype "passive"))
    )
    (net (code "252") (name "/WL_SD_D1") (class "Default")
      (node (ref "U1") (pin "1E18") (pinfunction "SDMMC1_D1/UART6_TX_M0/GPIO2_A4_u_1E18") (pintype "passive"))
    )
    (net (code "253") (name "/WL_SD_D2") (class "Default")
      (node (ref "U1") (pin "1D18") (pinfunction "SDMMC1_D2/UART7_RX_M0/GPIO2_A5_u_1D18") (pintype "passive"))
    )
    (net (code "254") (name "/WL_SD_D3") (class "Default")
      (node (ref "U1") (pin "1A20") (pinfunction "SDMMC1_D3/UART7_TX_M0/GPIO2_A6_u_1A20") (pintype "passive"))
    )
    (net (code "255") (name "/WORKING_LED") (class "Default")
      (node (ref "R15") (pin "2") (pinfunction "2_2") (pintype "passive"))
      (node (ref "U1") (pin "1T19") (pinfunction "PWM1_M0/GPUAVS/UART0_RX/GPIO0_C0_d_1T19") (pintype "passive"))
    )
    (net (code "256") (name "/XIN24M") (class "Default")
      (node (ref "R16") (pin "2") (pinfunction "2_2") (pintype "passive"))
      (node (ref "R17") (pin "1") (pinfunction "1_1") (pintype "passive"))
      (node (ref "U1") (pin "AD37") (pinfunction "XIN24M_AD37") (pintype "passive"))
    )
    (net (code "257") (name "/XOUT24M") (class "Default")
      (node (ref "C3") (pin "1") (pinfunction "1_1") (pintype "passive"))
      (node (ref "R17") (pin "2") (pinfunction "2_2") (pintype "passive"))
      (node (ref "U1") (pin "AD38") (pinfunction "XOUT24M_AD38") (pintype "passive"))
      (node (ref "X1") (pin "3") (pinfunction "2_3") (pintype "passive"))
    )
    (net (code "258") (name "/eMMC_CLK") (class "Default")
      (node (ref "R3") (pin "1") (pinfunction "1_1") (pintype "passive"))
    )
    (net (code "259") (name "/eMMC_CMD") (class "Default")
      (node (ref "U1") (pin "A27") (pinfunction "EMMC_CMD/FLASH_WRn/GPIO1_C4_u_A27") (pintype "passive"))
    )
    (net (code "260") (name "/eMMC_D0") (class "Default")
      (node (ref "S1") (pin "2") (pinfunction "P3_2") (pintype "passive"))
      (node (ref "U1") (pin "A32") (pinfunction "EMMC_D0/FLASH_D0/GPIO1_B4_u_A32") (pintype "passive"))
    )
    (net (code "261") (name "/eMMC_D1") (class "Default")
      (node (ref "U1") (pin "B27") (pinfunction "EMMC_D1/FLASH_D1/GPIO1_B5_u_B27") (pintype "passive"))
    )
    (net (code "262") (name "/eMMC_D2") (class "Default")
      (node (ref "U1") (pin "B32") (pinfunction "EMMC_D2/FLASH_D2/GPIO1_B6_u_B32") (pintype "passive"))
    )
    (net (code "263") (name "/eMMC_D3") (class "Default")
      (node (ref "U1") (pin "B29") (pinfunction "EMMC_D3/FLASH_D3/GPIO1_B7_u_B29") (pintype "passive"))
    )
    (net (code "264") (name "/eMMC_D4") (class "Default")
      (node (ref "U1") (pin "B33") (pinfunction "EMMC_D4/FLASH_D4/GPIO1_C0_u_B33") (pintype "passive"))
    )
    (net (code "265") (name "/eMMC_D5") (class "Default")
      (node (ref "U1") (pin "A30") (pinfunction "EMMC_D5/FLASH_D5/GPIO1_C1_u_A30") (pintype "passive"))
    )
    (net (code "266") (name "/eMMC_D6") (class "Default")
      (node (ref "U1") (pin "B30") (pinfunction "EMMC_D6/FLASH_D6/GPIO1_C2_u_B30") (pintype "passive"))
    )
    (net (code "267") (name "/eMMC_D7") (class "Default")
      (node (ref "U1") (pin "A33") (pinfunction "EMMC_D7/FLASH_D7/GPIO1_C3_u_A33") (pintype "passive"))
    )
    (net (code "268") (name "/eMMC_DS") (class "Default")
      (node (ref "U1") (pin "1A16") (pinfunction "EMMC_DATA_STROBE/FSPI_CS1n/FLASH_CLE/GPIO1_C6_d_1A16") (pintype "passive"))
    )
    (net (code "269") (name "/eMMC_RST#") (class "Default")
      (node (ref "U1") (pin "1B16") (pinfunction "EMMC_RSTn/FSPI_D2/FLASH_WPn/GPIO1_C7_d_1B16") (pintype "passive"))
    )
    (net (code "283") (name "GND") (class "Default")
      (node (ref "C1") (pin "2") (pinfunction "2_2") (pintype "passive"))
      (node (ref "C10") (pin "2") (pinfunction "2_2") (pintype "passive"))
      (node (ref "C11") (pin "2") (pinfunction "2_2") (pintype "passive"))
      (node (ref "C12") (pin "2") (pinfunction "2_2") (pintype "passive"))
      (node (ref "C13") (pin "1") (pinfunction "1_1") (pintype "passive"))
      (node (ref "C14") (pin "2") (pinfunction "2_2") (pintype "passive"))
      (node (ref "C15") (pin "1") (pinfunction "1_1") (pintype "passive"))
      (node (ref "C16") (pin "1") (pinfunction "1_1") (pintype "passive"))
      (node (ref "C17") (pin "1") (pinfunction "1_1") (pintype "passive"))
      (node (ref "C18") (pin "1") (pinfunction "1_1") (pintype "passive"))
      (node (ref "C19") (pin "1") (pinfunction "1_1") (pintype "passive"))
      (node (ref "C2") (pin "2") (pinfunction "2_2") (pintype "passive"))
      (node (ref "C20") (pin "2") (pinfunction "2_2") (pintype "passive"))
      (node (ref "C21") (pin "2") (pinfunction "2_2") (pintype "passive"))
      (node (ref "C22") (pin "2") (pinfunction "2_2") (pintype "passive"))
      (node (ref "C23") (pin "2") (pinfunction "2_2") (pintype "passive"))
      (node (ref "C24") (pin "2") (pinfunction "2_2") (pintype "passive"))
      (node (ref "C25") (pin "1") (pinfunction "1_1") (pintype "passive"))
      (node (ref "C26") (pin "2") (pinfunction "2_2") (pintype "passive"))
      (node (ref "C27") (pin "1") (pinfunction "1_1") (pintype "passive"))
      (node (ref "C28") (pin "2") (pinfunction "2_2") (pintype "passive"))
      (node (ref "C29") (pin "2") (pinfunction "2_2") (pintype "passive"))
      (node (ref "C3") (pin "2") (pinfunction "2_2") (pintype "passive"))
      (node (ref "C30") (pin "2") (pinfunction "2_2") (pintype "passive"))
      (node (ref "C31") (pin "2") (pinfunction "2_2") (pintype "passive"))
      (node (ref "C32") (pin "2") (pinfunction "2_2") (pintype "passive"))
      (node (ref "C33") (pin "2") (pinfunction "2_2") (pintype "passive"))
      (node (ref "C34") (pin "2") (pinfunction "2_2") (pintype "passive"))
      (node (ref "C35") (pin "2") (pinfunction "2_2") (pintype "passive"))
      (node (ref "C36") (pin "2") (pinfunction "2_2") (pintype "passive"))
      (node (ref "C37") (pin "1") (pinfunction "1_1") (pintype "passive"))
      (node (ref "C38") (pin "1") (pinfunction "1_1") (pintype "passive"))
      (node (ref "C39") (pin "1") (pinfunction "1_1") (pintype "passive"))
      (node (ref "C4") (pin "1") (pinfunction "1_1") (pintype "passive"))
      (node (ref "C40") (pin "1") (pinfunction "1_1") (pintype "passive"))
      (node (ref "C41") (pin "1") (pinfunction "1_1") (pintype "passive"))
      (node (ref "C42") (pin "1") (pinfunction "1_1") (pintype "passive"))
      (node (ref "C43") (pin "1") (pinfunction "1_1") (pintype "passive"))
      (node (ref "C44") (pin "1") (pinfunction "1_1") (pintype "passive"))
      (node (ref "C45") (pin "1") (pinfunction "1_1") (pintype "passive"))
      (node (ref "C46") (pin "1") (pinfunction "1_1") (pintype "passive"))
      (node (ref "C47") (pin "2") (pinfunction "2_2") (pintype "passive"))
      (node (ref "C48") (pin "1") (pinfunction "1_1") (pintype "passive"))
      (node (ref "C49") (pin "1") (pinfunction "1_1") (pintype "passive"))
      (node (ref "C5") (pin "2") (pinfunction "2_2") (pintype "passive"))
      (node (ref "C50") (pin "1") (pinfunction "1_1") (pintype "passive"))
      (node (ref "C51") (pin "1") (pinfunction "1_1") (pintype "passive"))
      (node (ref "C52") (pin "1") (pinfunction "1_1") (pintype "passive"))
      (node (ref "C53") (pin "1") (pinfunction "1_1") (pintype "passive"))
      (node (ref "C54") (pin "1") (pinfunction "1_1") (pintype "passive"))
      (node (ref "C55") (pin "1") (pinfunction "1_1") (pintype "passive"))
      (node (ref "C56") (pin "1") (pinfunction "1_1") (pintype "passive"))
      (node (ref "C57") (pin "1") (pinfunction "1_1") (pintype "passive"))
      (node (ref "C58") (pin "2") (pinfunction "2_2") (pintype "passive"))
      (node (ref "C59") (pin "2") (pinfunction "2_2") (pintype "passive"))
      (node (ref "C6") (pin "1") (pinfunction "1_1") (pintype "passive"))
      (node (ref "C60") (pin "2") (pinfunction "2_2") (pintype "passive"))
      (node (ref "C61") (pin "1") (pinfunction "1_1") (pintype "passive"))
      (node (ref "C62") (pin "1") (pinfunction "1_1") (pintype "passive"))
      (node (ref "C63") (pin "1") (pinfunction "1_1") (pintype "passive"))
      (node (ref "C64") (pin "1") (pinfunction "1_1") (pintype "passive"))
      (node (ref "C65") (pin "2") (pinfunction "2_2") (pintype "passive"))
      (node (ref "C66") (pin "1") (pinfunction "1_1") (pintype "passive"))
      (node (ref "C67") (pin "1") (pinfunction "1_1") (pintype "passive"))
      (node (ref "C68") (pin "1") (pinfunction "1_1") (pintype "passive"))
      (node (ref "C69") (pin "1") (pinfunction "1_1") (pintype "passive"))
      (node (ref "C7") (pin "2") (pinfunction "2_2") (pintype "passive"))
      (node (ref "C70") (pin "1") (pinfunction "1_1") (pintype "passive"))
      (node (ref "C71") (pin "1") (pinfunction "1_1") (pintype "passive"))
      (node (ref "C72") (pin "1") (pinfunction "1_1") (pintype "passive"))
      (node (ref "C73") (pin "2") (pinfunction "2_2") (pintype "passive"))
      (node (ref "C74") (pin "2") (pinfunction "2_2") (pintype "passive"))
      (node (ref "C75") (pin "1") (pinfunction "1_1") (pintype "passive"))
      (node (ref "C76") (pin "1") (pinfunction "1_1") (pintype "passive"))
      (node (ref "C8") (pin "2") (pinfunction "2_2") (pintype "passive"))
      (node (ref "D1") (pin "2") (pinfunction "CATHODE_2") (pintype "passive"))
      (node (ref "D2") (pin "1") (pinfunction "1_1") (pintype "passive"))
      (node (ref "D3") (pin "2") (pinfunction "CATHODE_2") (pintype "passive"))
      (node (ref "J1") (pin "3") (pinfunction "3_3") (pintype "passive"))
      (node (ref "J2") (pin "31") (pinfunction "31_31") (pintype "passive"))
      (node (ref "J2") (pin "32") (pinfunction "32_32") (pintype "passive"))
      (node (ref "R10") (pin "1") (pinfunction "1_1") (pintype "passive"))
      (node (ref "R12") (pin "2") (pinfunction "2_2") (pintype "passive"))
      (node (ref "R19") (pin "2") (pinfunction "2_2") (pintype "passive"))
      (node (ref "S1") (pin "1") (pinfunction "P1_1") (pintype "passive"))
      (node (ref "S2") (pin "2") (pinfunction "2_2") (pintype "passive"))
      (node (ref "U1") (pin "1B10") (pinfunction "VSS_30_1B10") (pintype "passive"))
      (node (ref "U1") (pin "1B11") (pinfunction "VSS_31_1B11") (pintype "passive"))
      (node (ref "U1") (pin "1B15") (pinfunction "VSS_32_1B15") (pintype "passive"))
      (node (ref "U1") (pin "1B19") (pinfunction "VSS_33_1B19") (pintype "passive"))
      (node (ref "U1") (pin "1C14") (pinfunction "VSS_39_1C14") (pintype "passive"))
      (node (ref "U1") (pin "1C16") (pinfunction "VSS_40_1C16") (pintype "passive"))
      (node (ref "U1") (pin "1C18") (pinfunction "VSS_41_1C18") (pintype "passive"))
      (node (ref "U1") (pin "1C4") (pinfunction "VSS_34_1C4") (pintype "passive"))
      (node (ref "U1") (pin "1C5") (pinfunction "VSS_35_1C5") (pintype "passive"))
      (node (ref "U1") (pin "1C6") (pinfunction "VSS_36_1C6") (pintype "passive"))
      (node (ref "U1") (pin "1C8") (pinfunction "VSS_37_1C8") (pintype "passive"))
      (node (ref "U1") (pin "1C9") (pinfunction "VSS_38_1C9") (pintype "passive"))
      (node (ref "U1") (pin "1D1") (pinfunction "VSS_42_1D1") (pintype "passive"))
      (node (ref "U1") (pin "1D10") (pinfunction "VSS_44_1D10") (pintype "passive"))
      (node (ref "U1") (pin "1D14") (pinfunction "VSS_45_1D14") (pintype "passive"))
      (node (ref "U1") (pin "1D3") (pinfunction "VSS_43_1D3") (pintype "passive"))
      (node (ref "U1") (pin "1D4") (pinfunction "DDR_AVSS_1D4") (pintype "passive"))
      (node (ref "U1") (pin "1E10") (pinfunction "VSS_48_1E10") (pintype "passive"))
      (node (ref "U1") (pin "1E14") (pinfunction "VSS_49_1E14") (pintype "passive"))
      (node (ref "U1") (pin "1E15") (pinfunction "VSS_50_1E15") (pintype "passive"))
      (node (ref "U1") (pin "1E17") (pinfunction "VSS_51_1E17") (pintype "passive"))
      (node (ref "U1") (pin "1E3") (pinfunction "VSS_46_1E3") (pintype "passive"))
      (node (ref "U1") (pin "1E8") (pinfunction "VSS_47_1E8") (pintype "passive"))
      (node (ref "U1") (pin "1F10") (pinfunction "VSS_56_1F10") (pintype "passive"))
      (node (ref "U1") (pin "1F15") (pinfunction "VSS_57_1F15") (pintype "passive"))
      (node (ref "U1") (pin "1F16") (pinfunction "VSS_58_1F16") (pintype "passive"))
      (node (ref "U1") (pin "1F20") (pinfunction "AVSS1_6_1F20") (pintype "passive"))
      (node (ref "U1") (pin "1F6") (pinfunction "VSS_52_1F6") (pintype "passive"))
      (node (ref "U1") (pin "1F7") (pinfunction "VSS_53_1F7") (pintype "passive"))
      (node (ref "U1") (pin "1F8") (pinfunction "VSS_54_1F8") (pintype "passive"))
      (node (ref "U1") (pin "1F9") (pinfunction "VSS_55_1F9") (pintype "passive"))
      (node (ref "U1") (pin "1G10") (pinfunction "VSS_64_1G10") (pintype "passive"))
      (node (ref "U1") (pin "1G11") (pinfunction "VSS_65_1G11") (pintype "passive"))
      (node (ref "U1") (pin "1G12") (pinfunction "VSS_66_1G12") (pintype "passive"))
      (node (ref "U1") (pin "1G14") (pinfunction "VSS_67_1G14") (pintype "passive"))
      (node (ref "U1") (pin "1G16") (pinfunction "AVSS1_7_1G16") (pintype "passive"))
      (node (ref "U1") (pin "1G18") (pinfunction "AVSS1_8_1G18") (pintype "passive"))
      (node (ref "U1") (pin "1G19") (pinfunction "AVSS1_9_1G19") (pintype "passive"))
      (node (ref "U1") (pin "1G20") (pinfunction "AVSS1_10_1G20") (pintype "passive"))
      (node (ref "U1") (pin "1G3") (pinfunction "VSS_59_1G3") (pintype "passive"))
      (node (ref "U1") (pin "1G6") (pinfunction "VSS_60_1G6") (pintype "passive"))
      (node (ref "U1") (pin "1G7") (pinfunction "VSS_61_1G7") (pintype "passive"))
      (node (ref "U1") (pin "1G8") (pinfunction "VSS_62_1G8") (pintype "passive"))
      (node (ref "U1") (pin "1G9") (pinfunction "VSS_63_1G9") (pintype "passive"))
      (node (ref "U1") (pin "1H1") (pinfunction "VSS_68_1H1") (pintype "passive"))
      (node (ref "U1") (pin "1H11") (pinfunction "VSS_71_1H11") (pintype "passive"))
      (node (ref "U1") (pin "1H12") (pinfunction "VSS_72_1H12") (pintype "passive"))
      (node (ref "U1") (pin "1H13") (pinfunction "VSS_73_1H13") (pintype "passive"))
      (node (ref "U1") (pin "1H2") (pinfunction "VSS_69_1H2") (pintype "passive"))
      (node (ref "U1") (pin "1H6") (pinfunction "VSS_70_1H6") (pintype "passive"))
      (node (ref "U1") (pin "1J1") (pinfunction "VSS_74_1J1") (pintype "passive"))
      (node (ref "U1") (pin "1J11") (pinfunction "VSS_78_1J11") (pintype "passive"))
      (node (ref "U1") (pin "1J12") (pinfunction "VSS_79_1J12") (pintype "passive"))
      (node (ref "U1") (pin "1J13") (pinfunction "VSS_80_1J13") (pintype "passive"))
      (node (ref "U1") (pin "1J16") (pinfunction "AVSS1_11_1J16") (pintype "passive"))
      (node (ref "U1") (pin "1J18") (pinfunction "AVSS1_12_1J18") (pintype "passive"))
      (node (ref "U1") (pin "1J5") (pinfunction "SYSPLL_AVSS_1J5") (pintype "passive"))
      (node (ref "U1") (pin "1J6") (pinfunction "VSS_75_1J6") (pintype "passive"))
      (node (ref "U1") (pin "1J8") (pinfunction "VSS_76_1J8") (pintype "passive"))
      (node (ref "U1") (pin "1J9") (pinfunction "VSS_77_1J9") (pintype "passive"))
      (node (ref "U1") (pin "1K11") (pinfunction "VSS_88_1K11") (pintype "passive"))
      (node (ref "U1") (pin "1K12") (pinfunction "VSS_89_1K12") (pintype "passive"))
      (node (ref "U1") (pin "1K13") (pinfunction "VSS_90_1K13") (pintype "passive"))
      (node (ref "U1") (pin "1K14") (pinfunction "VSS_91_1K14") (pintype "passive"))
      (node (ref "U1") (pin "1K15") (pinfunction "VSS_92_1K15") (pintype "passive"))
      (node (ref "U1") (pin "1K18") (pinfunction "AVSS1_13_1K18") (pintype "passive"))
      (node (ref "U1") (pin "1K2") (pinfunction "VSS_81_1K2") (pintype "passive"))
      (node (ref "U1") (pin "1K3") (pinfunction "VSS_82_1K3") (pintype "passive"))
      (node (ref "U1") (pin "1K4") (pinfunction "VSS_83_1K4") (pintype "passive"))
      (node (ref "U1") (pin "1K5") (pinfunction "VSS_84_1K5") (pintype "passive"))
      (node (ref "U1") (pin "1K6") (pinfunction "VSS_85_1K6") (pintype "passive"))
      (node (ref "U1") (pin "1K8") (pinfunction "VSS_86_1K8") (pintype "passive"))
      (node (ref "U1") (pin "1K9") (pinfunction "VSS_87_1K9") (pintype "passive"))
      (node (ref "U1") (pin "1L10") (pinfunction "VSS_95_1L10") (pintype "passive"))
      (node (ref "U1") (pin "1L11") (pinfunction "VSS_96_1L11") (pintype "passive"))
      (node (ref "U1") (pin "1L12") (pinfunction "VSS_97_1L12") (pintype "passive"))
      (node (ref "U1") (pin "1L13") (pinfunction "VSS_98_1L13") (pintype "passive"))
      (node (ref "U1") (pin "1L14") (pinfunction "VSS_99_1L14") (pintype "passive"))
      (node (ref "U1") (pin "1L15") (pinfunction "VSS_100_1L15") (pintype "passive"))
      (node (ref "U1") (pin "1L19") (pinfunction "AVSS1_14_1L19") (pintype "passive"))
      (node (ref "U1") (pin "1L3") (pinfunction "VSS_93_1L3") (pintype "passive"))
      (node (ref "U1") (pin "1L6") (pinfunction "VSS_94_1L6") (pintype "passive"))
      (node (ref "U1") (pin "1M10") (pinfunction "VSS_105_1M10") (pintype "passive"))
      (node (ref "U1") (pin "1M11") (pinfunction "VSS_106_1M11") (pintype "passive"))
      (node (ref "U1") (pin "1M12") (pinfunction "VSS_107_1M12") (pintype "passive"))
      (node (ref "U1") (pin "1M13") (pinfunction "VSS_108_1M13") (pintype "passive"))
      (node (ref "U1") (pin "1M14") (pinfunction "VSS_109_1M14") (pintype "passive"))
      (node (ref "U1") (pin "1M15") (pinfunction "VSS_110_1M15") (pintype "passive"))
      (node (ref "U1") (pin "1M16") (pinfunction "VSS_111_1M16") (pintype "passive"))
      (node (ref "U1") (pin "1M17") (pinfunction "VSS_112_1M17") (pintype "passive"))
      (node (ref "U1") (pin "1M20") (pinfunction "VSS_113_1M20") (pintype "passive"))
      (node (ref "U1") (pin "1M3") (pinfunction "VSS_101_1M3") (pintype "passive"))
      (node (ref "U1") (pin "1M4") (pinfunction "VSS_102_1M4") (pintype "passive"))
      (node (ref "U1") (pin "1M5") (pinfunction "VSS_103_1M5") (pintype "passive"))
      (node (ref "U1") (pin "1M6") (pinfunction "VSS_104_1M6") (pintype "passive"))
      (node (ref "U1") (pin "1N10") (pinfunction "MIPI_DSI_TX1_AVDD_0V9_1N10") (pintype "passive"))
      (node (ref "U1") (pin "1N11") (pinfunction "AVSS_9_1N11") (pintype "passive"))
      (node (ref "U1") (pin "1N12") (pinfunction "AVSS_10_1N12") (pintype "passive"))
      (node (ref "U1") (pin "1N17") (pinfunction "PMUPLL_AVSS_1N17") (pintype "passive"))
      (node (ref "U1") (pin "1N3") (pinfunction "VSS_114_1N3") (pintype "passive"))
      (node (ref "U1") (pin "1N4") (pinfunction "VSS_115_1N4") (pintype "passive"))
      (node (ref "U1") (pin "1N7") (pinfunction "VSS_116_1N7") (pintype "passive"))
      (node (ref "U1") (pin "1N9") (pinfunction "MIPI_CSI_RX_AVDD_0V9_1N9") (pintype "passive"))
      (node (ref "U1") (pin "1P1") (pinfunction "VSS_117_1P1") (pintype "passive"))
      (node (ref "U1") (pin "1P10") (pinfunction "AVSS_12_1P10") (pintype "passive"))
      (node (ref "U1") (pin "1P11") (pinfunction "MIPI_DSI_TX0/LVDS_TX0_AVDD_0V9_1P11") (pintype "passive"))
      (node (ref "U1") (pin "1P12") (pinfunction "MIPI_DSI_TX0/LVDS_TX0_AVDD_1V8_1P12") (pintype "passive"))
      (node (ref "U1") (pin "1P14") (pinfunction "AVSS_13_1P14") (pintype "passive"))
      (node (ref "U1") (pin "1P15") (pinfunction "VSS_121_1P15") (pintype "passive"))
      (node (ref "U1") (pin "1P5") (pinfunction "VSS_118_1P5") (pintype "passive"))
      (node (ref "U1") (pin "1P6") (pinfunction "VSS_119_1P6") (pintype "passive"))
      (node (ref "U1") (pin "1P7") (pinfunction "VSS_120_1P7") (pintype "passive"))
      (node (ref "U1") (pin "1P8") (pinfunction "AVSS_11_1P8") (pintype "passive"))
      (node (ref "U1") (pin "1P9") (pinfunction "MIPI_CSI_RX_AVDD_1V8_1P9") (pintype "passive"))
      (node (ref "U1") (pin "1R10") (pinfunction "MIPI_DSI_TX1_AVDD_1V8_1R10") (pintype "passive"))
      (node (ref "U1") (pin "1R11") (pinfunction "AVSS_16_1R11") (pintype "passive"))
      (node (ref "U1") (pin "1R12") (pinfunction "AVSS_17_1R12") (pintype "passive"))
      (node (ref "U1") (pin "1R13") (pinfunction "AVSS_18_1R13") (pintype "passive"))
      (node (ref "U1") (pin "1R14") (pinfunction "AVSS_19_1R14") (pintype "passive"))
      (node (ref "U1") (pin "1R15") (pinfunction "AVSS_20_1R15") (pintype "passive"))
      (node (ref "U1") (pin "1R3") (pinfunction "VSS_122_1R3") (pintype "passive"))
      (node (ref "U1") (pin "1R4") (pinfunction "VSS_123_1R4") (pintype "passive"))
      (node (ref "U1") (pin "1R5") (pinfunction "VSS_124_1R5") (pintype "passive"))
      (node (ref "U1") (pin "1R6") (pinfunction "VSS_125_1R6") (pintype "passive"))
      (node (ref "U1") (pin "1R7") (pinfunction "VSS_126_1R7") (pintype "passive"))
      (node (ref "U1") (pin "1R8") (pinfunction "AVSS_14_1R8") (pintype "passive"))
      (node (ref "U1") (pin "1R9") (pinfunction "AVSS_15_1R9") (pintype "passive"))
      (node (ref "U1") (pin "1T10") (pinfunction "AVSS_24_1T10") (pintype "passive"))
      (node (ref "U1") (pin "1T11") (pinfunction "AVSS_25_1T11") (pintype "passive"))
      (node (ref "U1") (pin "1T12") (pinfunction "AVSS_26_1T12") (pintype "passive"))
      (node (ref "U1") (pin "1T13") (pinfunction "AVSS_27_1T13") (pintype "passive"))
      (node (ref "U1") (pin "1T14") (pinfunction "AVSS_28_1T14") (pintype "passive"))
      (node (ref "U1") (pin "1T15") (pinfunction "AVSS_29_1T15") (pintype "passive"))
      (node (ref "U1") (pin "1T16") (pinfunction "AVSS_30_1T16") (pintype "passive"))
      (node (ref "U1") (pin "1T17") (pinfunction "AVSS_31_1T17") (pintype "passive"))
      (node (ref "U1") (pin "1T3") (pinfunction "VSS_127_1T3") (pintype "passive"))
      (node (ref "U1") (pin "1T5") (pinfunction "VSS_128_1T5") (pintype "passive"))
      (node (ref "U1") (pin "1T7") (pinfunction "AVSS_21_1T7") (pintype "passive"))
      (node (ref "U1") (pin "1T8") (pinfunction "AVSS_22_1T8") (pintype "passive"))
      (node (ref "U1") (pin "1T9") (pinfunction "AVSS_23_1T9") (pintype "passive"))
      (node (ref "U1") (pin "1U12") (pinfunction "AVSS_32_1U12") (pintype "passive"))
      (node (ref "U1") (pin "1U13") (pinfunction "AVSS_33_1U13") (pintype "passive"))
      (node (ref "U1") (pin "1U15") (pinfunction "AVSS_34_1U15") (pintype "passive"))
      (node (ref "U1") (pin "1U17") (pinfunction "AVSS_35_1U17") (pintype "passive"))
      (node (ref "U1") (pin "1U2") (pinfunction "VSS_129_1U2") (pintype "passive"))
      (node (ref "U1") (pin "1V1") (pinfunction "VSS_130_1V1") (pintype "passive"))
      (node (ref "U1") (pin "1V12") (pinfunction "AVSS_37_1V12") (pintype "passive"))
      (node (ref "U1") (pin "1V13") (pinfunction "AVSS_38_1V13") (pintype "passive"))
      (node (ref "U1") (pin "1V18") (pinfunction "AVSS_39_1V18") (pintype "passive"))
      (node (ref "U1") (pin "1V4") (pinfunction "VSS_131_1V4") (pintype "passive"))
      (node (ref "U1") (pin "1V7") (pinfunction "AVSS_36_1V7") (pintype "passive"))
      (node (ref "U1") (pin "A1") (pinfunction "VSS_1_A1") (pintype "passive"))
      (node (ref "U1") (pin "A2") (pinfunction "VSS_2_A2") (pintype "passive"))
      (node (ref "U1") (pin "A38") (pinfunction "VSS_3_A38") (pintype "passive"))
      (node (ref "U1") (pin "AA2") (pinfunction "VSS_18_AA2") (pintype "passive"))
      (node (ref "U1") (pin "AC37") (pinfunction "VSS_24_AC37") (pintype "passive"))
      (node (ref "U1") (pin "AD2") (pinfunction "VSS_19_AD2") (pintype "passive"))
      (node (ref "U1") (pin "AE37") (pinfunction "VSS_25_AE37") (pintype "passive"))
      (node (ref "U1") (pin "AH37") (pinfunction "VSS_26_AH37") (pintype "passive"))
      (node (ref "U1") (pin "AL37") (pinfunction "VSS_27_AL37") (pintype "passive"))
      (node (ref "U1") (pin "AP13") (pinfunction "AVSS_1_AP13") (pintype "passive"))
      (node (ref "U1") (pin "AP16") (pinfunction "AVSS_2_AP16") (pintype "passive"))
      (node (ref "U1") (pin "AP19") (pinfunction "AVSS_3_AP19") (pintype "passive"))
      (node (ref "U1") (pin "AP2") (pinfunction "VSS_20_AP2") (pintype "passive"))
      (node (ref "U1") (pin "AP22") (pinfunction "AVSS_4_AP22") (pintype "passive"))
      (node (ref "U1") (pin "AP25") (pinfunction "AVSS_5_AP25") (pintype "passive"))
      (node (ref "U1") (pin "AP28") (pinfunction "AVSS_6_AP28") (pintype "passive"))
      (node (ref "U1") (pin "AP31") (pinfunction "AVSS_7_AP31") (pintype "passive"))
      (node (ref "U1") (pin "AP34") (pinfunction "AVSS_8_AP34") (pintype "passive"))
      (node (ref "U1") (pin "AP37") (pinfunction "VSS_28_AP37") (pintype "passive"))
      (node (ref "U1") (pin "AP8") (pinfunction "VSS_22_AP8") (pintype "passive"))
      (node (ref "U1") (pin "AR1") (pinfunction "VSS_21_AR1") (pintype "passive"))
      (node (ref "U1") (pin "AR38") (pinfunction "VSS_29_AR38") (pintype "passive"))
      (node (ref "U1") (pin "B1") (pinfunction "VSS_4_B1") (pintype "passive"))
      (node (ref "U1") (pin "B11") (pinfunction "VSS_7_B11") (pintype "passive"))
      (node (ref "U1") (pin "B14") (pinfunction "VSS_8_B14") (pintype "passive"))
      (node (ref "U1") (pin "B18") (pinfunction "VSS_9_B18") (pintype "passive"))
      (node (ref "U1") (pin "B2") (pinfunction "VSS_5_B2") (pintype "passive"))
      (node (ref "U1") (pin "B21") (pinfunction "VSS_10_B21") (pintype "passive"))
      (node (ref "U1") (pin "B28") (pinfunction "VSS_11_B28") (pintype "passive"))
      (node (ref "U1") (pin "B31") (pinfunction "VSS_12_B31") (pintype "passive"))
      (node (ref "U1") (pin "B6") (pinfunction "VSS_6_B6") (pintype "passive"))
      (node (ref "U1") (pin "D2") (pinfunction "VSS_13_D2") (pintype "passive"))
      (node (ref "U1") (pin "E37") (pinfunction "VSS_23_E37") (pintype "passive"))
      (node (ref "U1") (pin "H37") (pinfunction "AVSS1_1_H37") (pintype "passive"))
      (node (ref "U1") (pin "J2") (pinfunction "VSS_14_J2") (pintype "passive"))
      (node (ref "U1") (pin "L2") (pinfunction "VSS_15_L2") (pintype "passive"))
      (node (ref "U1") (pin "L37") (pinfunction "AVSS1_2_L37") (pintype "passive"))
      (node (ref "U1") (pin "P37") (pinfunction "AVSS1_3_P37") (pintype "passive"))
      (node (ref "U1") (pin "U2") (pinfunction "VSS_16_U2") (pintype "passive"))
      (node (ref "U1") (pin "U37") (pinfunction "AVSS1_4_U37") (pintype "passive"))
      (node (ref "U1") (pin "W2") (pinfunction "VSS_17_W2") (pintype "passive"))
      (node (ref "U1") (pin "Y37") (pinfunction "AVSS1_5_Y37") (pintype "passive"))
      (node (ref "X1") (pin "2") (pinfunction "2_2") (pintype "passive"))
      (node (ref "X1") (pin "4") (pinfunction "4_4") (pintype "passive"))
    )
    (net (code "284") (name "Net-(C2-Pad1)") (class "Default")
      (node (ref "C2") (pin "1") (pinfunction "1_1") (pintype "passive"))
      (node (ref "R16") (pin "1") (pinfunction "1_1") (pintype "passive"))
      (node (ref "X1") (pin "1") (pinfunction "1_1") (pintype "passive"))
    )
    (net (code "285") (name "Net-(D1-ANODE)") (class "Default")
      (node (ref "D1") (pin "1") (pinfunction "ANODE_1") (pintype "passive"))
      (node (ref "R14") (pin "1") (pinfunction "1_1") (pintype "passive"))
    )
    (net (code "286") (name "Net-(D3-ANODE)") (class "Default")
      (node (ref "D3") (pin "1") (pinfunction "ANODE_1") (pintype "passive"))
      (node (ref "R15") (pin "1") (pinfunction "1_1") (pintype "passive"))
    )
    (net (code "287") (name "Net-(D4-Pad1)") (class "Default")
      (node (ref "D4") (pin "1") (pinfunction "1_1") (pintype "passive"))
      (node (ref "J1") (pin "1") (pinfunction "1_1") (pintype "passive"))
    )
    (net (code "288") (name "Net-(U1A-SARADC_AVDD_1V8)") (class "Default")
      (node (ref "C12") (pin "1") (pinfunction "1_1") (pintype "passive"))
      (node (ref "FB1") (pin "2") (pinfunction "2_2") (pintype "passive"))
      (node (ref "U1") (pin "1D16") (pinfunction "SARADC_AVDD_1V8_1D16") (pintype "passive"))
    )
    (net (code "289") (name "Net-(U1A-TVSS)") (class "Default")
      (node (ref "R12") (pin "1") (pinfunction "1_1") (pintype "passive"))
      (node (ref "U1") (pin "1M18") (pinfunction "TVSS_1M18") (pintype "passive"))
    )
    (net (code "290") (name "Net-(U1B-EMMC_CLKOUT{slash}FLASH_DQS{slash}GPIO1_C5_d)") (class "Default")
      (node (ref "R3") (pin "2") (pinfunction "2_2") (pintype "passive"))
      (node (ref "U1") (pin "A29") (pinfunction "EMMC_CLKOUT/FLASH_DQS/GPIO1_C5_d_A29") (pintype "passive"))
    )
    (net (code "291") (name "Net-(U1B-SDMMC0_CLK{slash}TEST_CLKOUT{slash}UART5_TX_M0{slash}GPIO2_A2_d)") (class "Default")
      (node (ref "R6") (pin "2") (pinfunction "2_2") (pintype "passive"))
      (node (ref "U1") (pin "G38") (pinfunction "SDMMC0_CLK/TEST_CLKOUT/UART5_TX_M0/GPIO2_A2_d_G38") (pintype "passive"))
    )
    (net (code "292") (name "Net-(U1C-I2C4_SCL_M0{slash}EBC_GDOE{slash}ETH1_REFCLKO_25M_M1{slash}SPI3_CLK_M0{slash}I2S2_SDO_M1{slash}GPIO4_B3_d)") (class "Default")
      (node (ref "R11") (pin "2") (pinfunction "2_2") (pintype "passive"))
      (node (ref "U1") (pin "AE2") (pinfunction "I2C4_SCL_M0/EBC_GDOE/ETH1_REFCLKO_25M_M1/SPI3_CLK_M0/I2S2_SDO_M1/GPIO4_B3_d_AE2") (pintype "passive"))
    )
    (net (code "293") (name "VCC1V8") (class "Default")
      (node (ref "C59") (pin "1") (pinfunction "1_1") (pintype "passive"))
      (node (ref "C6") (pin "2") (pinfunction "2_2") (pintype "passive"))
      (node (ref "C7") (pin "1") (pinfunction "1_1") (pintype "passive"))
      (node (ref "U1") (pin "1C13") (pinfunction "VCCIO2_1C13") (pintype "passive"))
      (node (ref "U1") (pin "1L4") (pinfunction "VCCIO6_1_1L4") (pintype "passive"))
      (node (ref "U1") (pin "1L5") (pinfunction "VCCIO6_2_1L5") (pintype "passive"))
    )
    (net (code "294") (name "VCC1V8A") (class "Default")
      (node (ref "C24") (pin "1") (pinfunction "1_1") (pintype "passive"))
      (node (ref "C27") (pin "2") (pinfunction "2_2") (pintype "passive"))
      (node (ref "C28") (pin "1") (pinfunction "1_1") (pintype "passive"))
      (node (ref "C32") (pin "1") (pinfunction "1_1") (pintype "passive"))
      (node (ref "C33") (pin "1") (pinfunction "1_1") (pintype "passive"))
      (node (ref "C44") (pin "2") (pinfunction "2_2") (pintype "passive"))
      (node (ref "C45") (pin "2") (pinfunction "2_2") (pintype "passive"))
      (node (ref "FB1") (pin "1") (pinfunction "1_1") (pintype "passive"))
      (node (ref "R5") (pin "1") (pinfunction "1_1") (pintype "passive"))
      (node (ref "R7") (pin "1") (pinfunction "1_1") (pintype "passive"))
      (node (ref "R8") (pin "1") (pinfunction "1_1") (pintype "passive"))
      (node (ref "R9") (pin "1") (pinfunction "1_1") (pintype "passive"))
      (node (ref "U1") (pin "1D15") (pinfunction "OTP_VCC18_1D15") (pintype "passive"))
      (node (ref "U1") (pin "1H16") (pinfunction "USB_AVDD1_1V8_1H16") (pintype "passive"))
      (node (ref "U1") (pin "1H4") (pinfunction "SYSPLL_AVDD_1V8_1H4") (pintype "passive"))
      (node (ref "U1") (pin "1J3") (pinfunction "USB_AVDD2_1V8_1J3") (pintype "passive"))
      (node (ref "U1") (pin "1K17") (pinfunction "MULTI_PHY_AVDD_1V8_1K17") (pintype "passive"))
    )
    (net (code "295") (name "VCC3V3") (class "Default")
      (node (ref "C35") (pin "1") (pinfunction "1_1") (pintype "passive"))
      (node (ref "C36") (pin "1") (pinfunction "1_1") (pintype "passive"))
      (node (ref "C74") (pin "1") (pinfunction "1_1") (pintype "passive"))
      (node (ref "J2") (pin "1") (pinfunction "1_1") (pintype "passive"))
      (node (ref "J2") (pin "2") (pinfunction "2_2") (pintype "passive"))
      (node (ref "U1") (pin "1H18") (pinfunction "USB_AVDD1_3V3_1H18") (pintype "passive"))
      (node (ref "U1") (pin "1J2") (pinfunction "USB_AVDD2_3V3_1J2") (pintype "passive"))
      (node (ref "U1") (pin "1N8") (pinfunction "VCCIO7_1N8") (pintype "passive"))
    )
    (net (code "296") (name "VCC5V0") (class "Default")
      (node (ref "J2") (pin "3") (pinfunction "3_3") (pintype "passive"))
    )
    (net (code "297") (name "VCOD3V3") (class "Default")
      (node (ref "C1") (pin "1") (pinfunction "1_1") (pintype "passive"))
      (node (ref "C30") (pin "1") (pinfunction "1_1") (pintype "passive"))
      (node (ref "U1") (pin "1D13") (pinfunction "VCCIO1_1D13") (pintype "passive"))
      (node (ref "U1") (pin "1N5") (pinfunction "VCCIO5_1_1N5") (pintype "passive"))
      (node (ref "U1") (pin "1N6") (pinfunction "VCCIO5_2_1N6") (pintype "passive"))
    )
    (net (code "298") (name "VCPU0V9") (class "Default")
      (node (ref "C37") (pin "2") (pinfunction "2_2") (pintype "passive"))
      (node (ref "C38") (pin "2") (pinfunction "2_2") (pintype "passive"))
      (node (ref "C39") (pin "2") (pinfunction "2_2") (pintype "passive"))
      (node (ref "C40") (pin "2") (pinfunction "2_2") (pintype "passive"))
      (node (ref "C41") (pin "2") (pinfunction "2_2") (pintype "passive"))
      (node (ref "U1") (pin "1C12") (pinfunction "VDD_CPU_1_1C12") (pintype "passive"))
      (node (ref "U1") (pin "1D11") (pinfunction "VDD_CPU_2_1D11") (pintype "passive"))
      (node (ref "U1") (pin "1D12") (pinfunction "VDD_CPU_3_1D12") (pintype "passive"))
      (node (ref "U1") (pin "1E11") (pinfunction "VDD_CPU_4_1E11") (pintype "passive"))
      (node (ref "U1") (pin "1E12") (pinfunction "VDD_CPU_5_1E12") (pintype "passive"))
      (node (ref "U1") (pin "1E13") (pinfunction "VDD_CPU_6_1E13") (pintype "passive"))
      (node (ref "U1") (pin "1F11") (pinfunction "VDD_CPU_7_1F11") (pintype "passive"))
      (node (ref "U1") (pin "1F12") (pinfunction "VDD_CPU_8_1F12") (pintype "passive"))
      (node (ref "U1") (pin "1F13") (pinfunction "VDD_CPU_9_1F13") (pintype "passive"))
      (node (ref "U1") (pin "1F14") (pinfunction "VDD_CPU_10_1F14") (pintype "passive"))
      (node (ref "U1") (pin "1G13") (pinfunction "VDD_CPU_11_1G13") (pintype "passive"))
    )
    (net (code "299") (name "VDDA0V9") (class "Default")
      (node (ref "C25") (pin "2") (pinfunction "2_2") (pintype "passive"))
      (node (ref "C26") (pin "1") (pinfunction "1_1") (pintype "passive"))
      (node (ref "C29") (pin "1") (pinfunction "1_1") (pintype "passive"))
      (node (ref "C31") (pin "1") (pinfunction "1_1") (pintype "passive"))
      (node (ref "C42") (pin "2") (pinfunction "2_2") (pintype "passive"))
      (node (ref "C43") (pin "2") (pinfunction "2_2") (pintype "passive"))
      (node (ref "U1") (pin "1H5") (pinfunction "SYSPLL_AVDD_0V9_1H5") (pintype "passive"))
      (node (ref "U1") (pin "1J17") (pinfunction "USB_AVDD1_0V9_1J17") (pintype "passive"))
      (node (ref "U1") (pin "1J4") (pinfunction "USB_AVDD2_0V9_1J4") (pintype "passive"))
      (node (ref "U1") (pin "1K16") (pinfunction "MULTI_PHY_AVDD_0V9_1K16") (pintype "passive"))
    )
    (net (code "300") (name "VDDR") (class "Default")
      (node (ref "C15") (pin "2") (pinfunction "2_2") (pintype "passive"))
      (node (ref "C16") (pin "2") (pinfunction "2_2") (pintype "passive"))
      (node (ref "C17") (pin "2") (pinfunction "2_2") (pintype "passive"))
      (node (ref "C18") (pin "2") (pinfunction "2_2") (pintype "passive"))
      (node (ref "C19") (pin "2") (pinfunction "2_2") (pintype "passive"))
      (node (ref "C9") (pin "1") (pinfunction "1_1") (pintype "passive"))
      (node (ref "R4") (pin "1") (pinfunction "1_1") (pintype "passive"))
      (node (ref "U1") (pin "1D5") (pinfunction "DDRPHY_VDDQ_1_1D5") (pintype "passive"))
      (node (ref "U1") (pin "1D6") (pinfunction "DDRPHY_VDDQ_2_1D6") (pintype "passive"))
      (node (ref "U1") (pin "1D7") (pinfunction "DDRPHY_VDDQ_3_1D7") (pintype "passive"))
      (node (ref "U1") (pin "1D8") (pinfunction "DDRPHY_VDDQ_4_1D8") (pintype "passive"))
      (node (ref "U1") (pin "1D9") (pinfunction "DDRPHY_VDDQ_5_1D9") (pintype "passive"))
      (node (ref "U1") (pin "1E4") (pinfunction "DDRPHY_VDDQ_6_1E4") (pintype "passive"))
      (node (ref "U1") (pin "1E6") (pinfunction "DDRPHY_VDDQL_1_1E6") (pintype "passive"))
      (node (ref "U1") (pin "1E7") (pinfunction "DDRPHY_VDDQL_2_1E7") (pintype "passive"))
      (node (ref "U1") (pin "1E9") (pinfunction "DDRPHY_VDDQL_3_1E9") (pintype "passive"))
      (node (ref "U1") (pin "1F4") (pinfunction "DDRPHY_VDDQ_7_1F4") (pintype "passive"))
      (node (ref "U1") (pin "1F5") (pinfunction "DDRPHY_VDDQL_4_1F5") (pintype "passive"))
      (node (ref "U1") (pin "1G4") (pinfunction "DDRPHY_VDDQ_8_1G4") (pintype "passive"))
      (node (ref "U1") (pin "1G5") (pinfunction "DDRPHY_VDDQL_5_1G5") (pintype "passive"))
    )
    (net (code "301") (name "VGPU0V9") (class "Default")
      (node (ref "C48") (pin "2") (pinfunction "2_2") (pintype "passive"))
      (node (ref "C51") (pin "2") (pinfunction "2_2") (pintype "passive"))
      (node (ref "C52") (pin "2") (pinfunction "2_2") (pintype "passive"))
      (node (ref "C53") (pin "2") (pinfunction "2_2") (pintype "passive"))
      (node (ref "C54") (pin "2") (pinfunction "2_2") (pintype "passive"))
      (node (ref "U1") (pin "1L8") (pinfunction "VDD_GPU_1_1L8") (pintype "passive"))
      (node (ref "U1") (pin "1L9") (pinfunction "VDD_GPU_2_1L9") (pintype "passive"))
      (node (ref "U1") (pin "1M7") (pinfunction "VDD_GPU_3_1M7") (pintype "passive"))
      (node (ref "U1") (pin "1M8") (pinfunction "VDD_GPU_4_1M8") (pintype "passive"))
      (node (ref "U1") (pin "1M9") (pinfunction "VDD_GPU_5_1M9") (pintype "passive"))
    )
    (net (code "302") (name "VIMG0V9") (class "Default")
      (node (ref "C46") (pin "2") (pinfunction "2_2") (pintype "passive"))
      (node (ref "C47") (pin "1") (pinfunction "1_1") (pintype "passive"))
      (node (ref "C64") (pin "2") (pinfunction "2_2") (pintype "passive"))
      (node (ref "C65") (pin "1") (pinfunction "1_1") (pintype "passive"))
      (node (ref "U1") (pin "1H17") (pinfunction "EDP_TX_AVDD_0V9_1H17") (pintype "passive"))
      (node (ref "U1") (pin "1N13") (pinfunction "HDMI_TX_AVDD_0V9_2_1N13") (pintype "passive"))
      (node (ref "U1") (pin "1N14") (pinfunction "HDMI_TX_AVDD_0V9_1_1N14") (pintype "passive"))
    )
    (net (code "303") (name "VIMG1V8") (class "Default")
      (node (ref "C57") (pin "2") (pinfunction "2_2") (pintype "passive"))
      (node (ref "C58") (pin "1") (pinfunction "1_1") (pintype "passive"))
      (node (ref "C72") (pin "2") (pinfunction "2_2") (pintype "passive"))
      (node (ref "C73") (pin "1") (pinfunction "1_1") (pintype "passive"))
      (node (ref "U1") (pin "1G17") (pinfunction "EDP_TX_AVDD_1V8_1G17") (pintype "passive"))
      (node (ref "U1") (pin "1P13") (pinfunction "HDMI_TX_AVDD_1V8_1P13") (pintype "passive"))
    )
    (net (code "304") (name "VLG0V9") (class "Default")
      (node (ref "C66") (pin "2") (pinfunction "2_2") (pintype "passive"))
      (node (ref "C67") (pin "2") (pinfunction "2_2") (pintype "passive"))
      (node (ref "C68") (pin "2") (pinfunction "2_2") (pintype "passive"))
      (node (ref "C69") (pin "2") (pinfunction "2_2") (pintype "passive"))
      (node (ref "C75") (pin "2") (pinfunction "2_2") (pintype "passive"))
      (node (ref "C76") (pin "2") (pinfunction "2_2") (pintype "passive"))
      (node (ref "U1") (pin "1H10") (pinfunction "VDD_LOGIC_4_1H10") (pintype "passive"))
      (node (ref "U1") (pin "1H7") (pinfunction "VDD_LOGIC_1_1H7") (pintype "passive"))
      (node (ref "U1") (pin "1H8") (pinfunction "VDD_LOGIC_2_1H8") (pintype "passive"))
      (node (ref "U1") (pin "1H9") (pinfunction "VDD_LOGIC_3_1H9") (pintype "passive"))
      (node (ref "U1") (pin "1J10") (pinfunction "VDD_LOGIC_6_1J10") (pintype "passive"))
      (node (ref "U1") (pin "1J7") (pinfunction "VDD_LOGIC_5_1J7") (pintype "passive"))
      (node (ref "U1") (pin "1K10") (pinfunction "VDD_LOGIC_8_1K10") (pintype "passive"))
      (node (ref "U1") (pin "1K7") (pinfunction "VDD_LOGIC_7_1K7") (pintype "passive"))
      (node (ref "U1") (pin "1L7") (pinfunction "VDD_LOGIC_9_1L7") (pintype "passive"))
    )
    (net (code "305") (name "VNPU0V9") (class "Default")
      (node (ref "C49") (pin "2") (pinfunction "2_2") (pintype "passive"))
      (node (ref "C50") (pin "2") (pinfunction "2_2") (pintype "passive"))
      (node (ref "C61") (pin "2") (pinfunction "2_2") (pintype "passive"))
      (node (ref "C62") (pin "2") (pinfunction "2_2") (pintype "passive"))
      (node (ref "U1") (pin "1G15") (pinfunction "VDD_NPU_1_1G15") (pintype "passive"))
      (node (ref "U1") (pin "1H14") (pinfunction "VDD_NPU_2_1H14") (pintype "passive"))
      (node (ref "U1") (pin "1H15") (pinfunction "VDD_NPU_3_1H15") (pintype "passive"))
      (node (ref "U1") (pin "1J14") (pinfunction "VDD_NPU_4_1J14") (pintype "passive"))
      (node (ref "U1") (pin "1J15") (pinfunction "VDD_NPU_5_1J15") (pintype "passive"))
    )
    (net (code "306") (name "VPMU0V9") (class "Default")
      (node (ref "C55") (pin "2") (pinfunction "2_2") (pintype "passive"))
      (node (ref "C56") (pin "2") (pinfunction "2_2") (pintype "passive"))
      (node (ref "C63") (pin "2") (pinfunction "2_2") (pintype "passive"))
      (node (ref "U1") (pin "1N16") (pinfunction "PMU_VDD_LOGIC_0V9_1N16") (pintype "passive"))
      (node (ref "U1") (pin "1P17") (pinfunction "PMUPLL_AVDD_0V9_1P17") (pintype "passive"))
    )
    (net (code "307") (name "VPMU1V8") (class "Default")
      (node (ref "C70") (pin "2") (pinfunction "2_2") (pintype "passive"))
      (node (ref "C71") (pin "2") (pinfunction "2_2") (pintype "passive"))
      (node (ref "U1") (pin "1N18") (pinfunction "PMUPLL_AVDD_1V8_1N18") (pintype "passive"))
    )
    (net (code "308") (name "VPMU3V3") (class "Default")
      (node (ref "C5") (pin "1") (pinfunction "1_1") (pintype "passive"))
      (node (ref "C8") (pin "1") (pinfunction "1_1") (pintype "passive"))
      (node (ref "R1") (pin "1") (pinfunction "1_1") (pintype "passive"))
      (node (ref "R13") (pin "1") (pinfunction "1_1") (pintype "passive"))
      (node (ref "U1") (pin "1N15") (pinfunction "PMUIO2_1N15") (pintype "passive"))
      (node (ref "U1") (pin "1P16") (pinfunction "PMUIO1_1P16") (pintype "passive"))
    )
    (net (code "309") (name "VSD3V3") (class "Default")
      (node (ref "C10") (pin "1") (pinfunction "1_1") (pintype "passive"))
      (node (ref "U1") (pin "1F17") (pinfunction "VCCIO3_1F17") (pintype "passive"))
    )
    (net (code "310") (name "VWL") (class "Default")
      (node (ref "C13") (pin "2") (pinfunction "2_2") (pintype "passive"))
      (node (ref "C14") (pin "1") (pinfunction "1_1") (pintype "passive"))
      (node (ref "U1") (pin "1E16") (pinfunction "VCCIO4_1E16") (pintype "passive"))
    )
    (net (code "311") (name "unconnected-(U1A-GPIO0_D3_d-Pad1N19)") (class "Default")
      (node (ref "U1") (pin "1N19") (pinfunction "GPIO0_D3_d_1N19") (pintype "passive"))
    )
    (net (code "312") (name "unconnected-(U1A-GPIO0_D4_d-Pad1M19)") (class "Default")
      (node (ref "U1") (pin "1M19") (pinfunction "GPIO0_D4_d_1M19") (pintype "passive"))
    )
    (net (code "313") (name "unconnected-(U1A-GPIO0_D5_d-Pad1N20)") (class "Default")
      (node (ref "U1") (pin "1N20") (pinfunction "GPIO0_D5_d_1N20") (pintype "passive"))
    )
    (net (code "314") (name "unconnected-(U1A-GPIO0_D6_d-Pad1P20)") (class "Default")
      (node (ref "U1") (pin "1P20") (pinfunction "GPIO0_D6_d_1P20") (pintype "passive"))
    )
    (net (code "315") (name "unconnected-(U1B-FSPI_CLK{slash}FLASH_ALE{slash}GPIO1_D0_d-Pad1A15)") (class "Default")
      (node (ref "U1") (pin "1A15") (pinfunction "FSPI_CLK/FLASH_ALE/GPIO1_D0_d_1A15") (pintype "passive"))
    )
    (net (code "316") (name "unconnected-(U1B-FSPI_CS0n{slash}FLASH_CS0n{slash}GPIO1_D3_u-Pad1B17)") (class "Default")
      (node (ref "U1") (pin "1B17") (pinfunction "FSPI_CS0n/FLASH_CS0n/GPIO1_D3_u_1B17") (pintype "passive"))
    )
    (net (code "317") (name "unconnected-(U1B-FSPI_D0{slash}FLASH_RDY{slash}GPIO1_D1_u-Pad1A17)") (class "Default")
      (node (ref "U1") (pin "1A17") (pinfunction "FSPI_D0/FLASH_RDY/GPIO1_D1_u_1A17") (pintype "passive"))
    )
    (net (code "318") (name "unconnected-(U1B-FSPI_D1{slash}FLASH_RDn{slash}GPIO1_D2_u-Pad1A18)") (class "Default")
      (node (ref "U1") (pin "1A18") (pinfunction "FSPI_D1/FLASH_RDn/GPIO1_D2_u_1A18") (pintype "passive"))
    )
    (net (code "319") (name "unconnected-(U1B-FSPI_D3{slash}FLASH_CS1n{slash}GPIO1_D4_u-Pad1C15)") (class "Default")
      (node (ref "U1") (pin "1C15") (pinfunction "FSPI_D3/FLASH_CS1n/GPIO1_D4_u_1C15") (pintype "passive"))
    )
    (net (code "320") (name "unconnected-(U1B-I2S1_LRCK_TX_M0{slash}UART4_RTSn_M0{slash}SCR_RST{slash}GPIO1_A5_d-PadB24)") (class "Default")
      (node (ref "U1") (pin "B24") (pinfunction "I2S1_LRCK_TX_M0/UART4_RTSn_M0/SCR_RST/GPIO1_A5_d_B24") (pintype "passive"))
    )
    (net (code "321") (name "unconnected-(U1B-I2S1_MCLK_M0{slash}UART3_RTSn_M0{slash}SCR_CLK{slash}GPIO1_A2_d-PadA23)") (class "Default")
      (node (ref "U1") (pin "A23") (pinfunction "I2S1_MCLK_M0/UART3_RTSn_M0/SCR_CLK/GPIO1_A2_d_A23") (pintype "passive"))
    )
    (net (code "322") (name "unconnected-(U1B-I2S1_SCLK_TX_M0{slash}UART3_CTSn_M0{slash}SCR_IO{slash}GPIO1_A3_d-PadB23)") (class "Default")
      (node (ref "U1") (pin "B23") (pinfunction "I2S1_SCLK_TX_M0/UART3_CTSn_M0/SCR_IO/GPIO1_A3_d_B23") (pintype "passive"))
    )
    (net (code "323") (name "unconnected-(U1B-I2S1_SDO0_M0{slash}UART4_CTSn_M0{slash}SCR_DET{slash}AUDIOPWM_ROUT_N{slash}GPIO1_A7_d-PadB25)") (class "Default")
      (node (ref "U1") (pin "B25") (pinfunction "I2S1_SDO0_M0/UART4_CTSn_M0/SCR_DET/AUDIOPWM_ROUT_N/GPIO1_A7_d_B25") (pintype "passive"))
    )
    (net (code "324") (name "unconnected-(U1C-CIF_CLKOUT{slash}EBC_GDCLK{slash}PWM11_IR_M1{slash}GPIO4_C0_d-PadAB2)") (class "Default")
      (node (ref "U1") (pin "AB2") (pinfunction "CIF_CLKOUT/EBC_GDCLK/PWM11_IR_M1/GPIO4_C0_d_AB2") (pintype "passive"))
    )
    (net (code "325") (name "unconnected-(U1C-CIF_D0{slash}EBC_SDDO0{slash}SDMMC2_D0_M0{slash}I2S1_MCLK_M1{slash}VOP_BT656_D0_M1{slash}GPIO3_C6_d-Pad1T2)") (class "Default")
      (node (ref "U1") (pin "1T2") (pinfunction "CIF_D0/EBC_SDDO0/SDMMC2_D0_M0/I2S1_MCLK_M1/VOP_BT656_D0_M1/GPIO3_C6_d_1T2") (pintype "passive"))
    )
    (net (code "326") (name "unconnected-(U1C-CIF_D1{slash}EBC_SDDO1{slash}SDMMC2_D1_M0{slash}I2S1_SCLK_TX_M1{slash}VOP_BT656_D1_M1{slash}GPIO3_C7_d-Pad1U1)") (class "Default")
      (node (ref "U1") (pin "1U1") (pinfunction "CIF_D1/EBC_SDDO1/SDMMC2_D1_M0/I2S1_SCLK_TX_M1/VOP_BT656_D1_M1/GPIO3_C7_d_1U1") (pintype "passive"))
    )
    (net (code "327") (name "unconnected-(U1C-CIF_D2{slash}EBC_SDDO2{slash}SDMMC2_D2_M0{slash}I2S1_LRCK_TX_M1{slash}VOP_BT656_D2_M1{slash}GPIO3_D0_d-PadAP1)") (class "Default")
      (node (ref "U1") (pin "AP1") (pinfunction "CIF_D2/EBC_SDDO2/SDMMC2_D2_M0/I2S1_LRCK_TX_M1/VOP_BT656_D2_M1/GPIO3_D0_d_AP1") (pintype "passive"))
    )
    (net (code "328") (name "unconnected-(U1C-CIF_D3{slash}EBC_SDDO3{slash}SDMMC2_D3_M0{slash}I2S1_SDO0_M1{slash}VOP_BT656_D3_M1{slash}GPIO3_D1_d-PadAN2)") (class "Default")
      (node (ref "U1") (pin "AN2") (pinfunction "CIF_D3/EBC_SDDO3/SDMMC2_D3_M0/I2S1_SDO0_M1/VOP_BT656_D3_M1/GPIO3_D1_d_AN2") (pintype "passive"))
    )
    (net (code "329") (name "unconnected-(U1C-CIF_D4{slash}EBC_SDDO4{slash}SDMMC2_CMD_M0{slash}I2S1_SDI0_M1{slash}VOP_BT656_D4_M1{slash}GPIO3_D2_d-PadAM2)") (class "Default")
      (node (ref "U1") (pin "AM2") (pinfunction "CIF_D4/EBC_SDDO4/SDMMC2_CMD_M0/I2S1_SDI0_M1/VOP_BT656_D4_M1/GPIO3_D2_d_AM2") (pintype "passive"))
    )
    (net (code "330") (name "unconnected-(U1C-CIF_D6{slash}EBC_SDDO6{slash}SDMMC2_DET_M0{slash}I2S1_SDI2_M1{slash}VOP_BT656_D6_M1{slash}GPIO3_D4_d-Pad1R2)") (class "Default")
      (node (ref "U1") (pin "1R2") (pinfunction "CIF_D6/EBC_SDDO6/SDMMC2_DET_M0/I2S1_SDI2_M1/VOP_BT656_D6_M1/GPIO3_D4_d_1R2") (pintype "passive"))
    )
    (net (code "331") (name "unconnected-(U1C-CIF_D7{slash}EBC_SDDO7{slash}SDMMC2_PWREN_M0{slash}I2S1_SDI3_M1{slash}VOP_BT656_D7_M1{slash}GPIO3_D5_d-Pad1T1)") (class "Default")
      (node (ref "U1") (pin "1T1") (pinfunction "CIF_D7/EBC_SDDO7/SDMMC2_PWREN_M0/I2S1_SDI3_M1/VOP_BT656_D7_M1/GPIO3_D5_d_1T1") (pintype "passive"))
    )
    (net (code "332") (name "unconnected-(U1C-I2C4_SDA_M0{slash}EBC_VCOM{slash}GMAC1_RXER_M1{slash}SPI3_MOSI_M0{slash}I2S2_SDI_M1{slash}GPIO4_B2_d-PadAF2)") (class "Default")
      (node (ref "U1") (pin "AF2") (pinfunction "I2C4_SDA_M0/EBC_VCOM/GMAC1_RXER_M1/SPI3_MOSI_M0/I2S2_SDI_M1/GPIO4_B2_d_AF2") (pintype "passive"))
    )
    (net (code "333") (name "unconnected-(U1C-PWM15_IR_M1{slash}SPI3_MOSI_M1{slash}I2S3_SCLK_M1{slash}GPIO4_C3_d-PadAP12)") (class "Default")
      (node (ref "U1") (pin "AP12") (pinfunction "PWM15_IR_M1/SPI3_MOSI_M1/I2S3_SCLK_M1/GPIO4_C3_d_AP12") (pintype "passive"))
    )
    (net (code "334") (name "unconnected-(U1D-USB_HOST2_DM-PadV1)") (class "Default")
      (node (ref "U1") (pin "V1") (pinfunction "USB_HOST2_DM_V1") (pintype "passive"))
    )
    (net (code "335") (name "unconnected-(U1D-USB_HOST2_DP-PadV2)") (class "Default")
      (node (ref "U1") (pin "V2") (pinfunction "USB_HOST2_DP_V2") (pintype "passive"))
    )
    (net (code "336") (name "unconnected-(U1E-MIPI_CSI_RX_CLK0N-Pad1U9)") (class "Default")
      (node (ref "U1") (pin "1U9") (pinfunction "MIPI_CSI_RX_CLK0N_1U9") (pintype "passive"))
    )
    (net (code "337") (name "unconnected-(U1E-MIPI_CSI_RX_CLK0P-Pad1V9)") (class "Default")
      (node (ref "U1") (pin "1V9") (pinfunction "MIPI_CSI_RX_CLK0P_1V9") (pintype "passive"))
    )
    (net (code "338") (name "unconnected-(U1E-MIPI_CSI_RX_CLK1N-Pad1U8)") (class "Default")
      (node (ref "U1") (pin "1U8") (pinfunction "MIPI_CSI_RX_CLK1N_1U8") (pintype "passive"))
    )
    (net (code "339") (name "unconnected-(U1E-MIPI_CSI_RX_CLK1P-Pad1V8)") (class "Default")
      (node (ref "U1") (pin "1V8") (pinfunction "MIPI_CSI_RX_CLK1P_1V8") (pintype "passive"))
    )
    (net (code "340") (name "unconnected-(U1E-MIPI_CSI_RX_D0N-PadAR18)") (class "Default")
      (node (ref "U1") (pin "AR18") (pinfunction "MIPI_CSI_RX_D0N_AR18") (pintype "passive"))
    )
    (net (code "341") (name "unconnected-(U1E-MIPI_CSI_RX_D0P-PadAP18)") (class "Default")
      (node (ref "U1") (pin "AP18") (pinfunction "MIPI_CSI_RX_D0P_AP18") (pintype "passive"))
    )
    (net (code "342") (name "unconnected-(U1E-MIPI_CSI_RX_D1N-PadAP17)") (class "Default")
      (node (ref "U1") (pin "AP17") (pinfunction "MIPI_CSI_RX_D1N_AP17") (pintype "passive"))
    )
    (net (code "343") (name "unconnected-(U1E-MIPI_CSI_RX_D1P-PadAR17)") (class "Default")
      (node (ref "U1") (pin "AR17") (pinfunction "MIPI_CSI_RX_D1P_AR17") (pintype "passive"))
    )
    (net (code "344") (name "unconnected-(U1E-MIPI_CSI_RX_D2N-PadAR15)") (class "Default")
      (node (ref "U1") (pin "AR15") (pinfunction "MIPI_CSI_RX_D2N_AR15") (pintype "passive"))
    )
    (net (code "345") (name "unconnected-(U1E-MIPI_CSI_RX_D2P-PadAP15)") (class "Default")
      (node (ref "U1") (pin "AP15") (pinfunction "MIPI_CSI_RX_D2P_AP15") (pintype "passive"))
    )
    (net (code "346") (name "unconnected-(U1E-MIPI_CSI_RX_D3N-PadAP14)") (class "Default")
      (node (ref "U1") (pin "AP14") (pinfunction "MIPI_CSI_RX_D3N_AP14") (pintype "passive"))
    )
    (net (code "347") (name "unconnected-(U1E-MIPI_CSI_RX_D3P-PadAR14)") (class "Default")
      (node (ref "U1") (pin "AR14") (pinfunction "MIPI_CSI_RX_D3P_AR14") (pintype "passive"))
    )
    (net (code "348") (name "unconnected-(U1E-MIPI_DSI_TX0_CLKN{slash}LVDS_TX0_CLKN-Pad1V15)") (class "Default")
      (node (ref "U1") (pin "1V15") (pinfunction "MIPI_DSI_TX0_CLKN/LVDS_TX0_CLKN_1V15") (pintype "passive"))
    )
    (net (code "349") (name "unconnected-(U1E-MIPI_DSI_TX0_CLKP{slash}LVDS_TX0_CLKP-Pad1V16)") (class "Default")
      (node (ref "U1") (pin "1V16") (pinfunction "MIPI_DSI_TX0_CLKP/LVDS_TX0_CLKP_1V16") (pintype "passive"))
    )
    (net (code "350") (name "unconnected-(U1E-MIPI_DSI_TX0_D0N{slash}LVDS_TX0_D0N-PadAR30)") (class "Default")
      (node (ref "U1") (pin "AR30") (pinfunction "MIPI_DSI_TX0_D0N/LVDS_TX0_D0N_AR30") (pintype "passive"))
    )
    (net (code "351") (name "unconnected-(U1E-MIPI_DSI_TX0_D0P{slash}LVDS_TX0_D0P-PadAP30)") (class "Default")
      (node (ref "U1") (pin "AP30") (pinfunction "MIPI_DSI_TX0_D0P/LVDS_TX0_D0P_AP30") (pintype "passive"))
    )
    (net (code "352") (name "unconnected-(U1E-MIPI_DSI_TX0_D1N{slash}LVDS_TX0_D1N-PadAP29)") (class "Default")
      (node (ref "U1") (pin "AP29") (pinfunction "MIPI_DSI_TX0_D1N/LVDS_TX0_D1N_AP29") (pintype "passive"))
    )
    (net (code "353") (name "unconnected-(U1E-MIPI_DSI_TX0_D1P{slash}LVDS_TX0_D1P-PadAR29)") (class "Default")
      (node (ref "U1") (pin "AR29") (pinfunction "MIPI_DSI_TX0_D1P/LVDS_TX0_D1P_AR29") (pintype "passive"))
    )
    (net (code "354") (name "unconnected-(U1E-MIPI_DSI_TX0_D2N{slash}LVDS_TX0_D2N-PadAR27)") (class "Default")
      (node (ref "U1") (pin "AR27") (pinfunction "MIPI_DSI_TX0_D2N/LVDS_TX0_D2N_AR27") (pintype "passive"))
    )
    (net (code "355") (name "unconnected-(U1E-MIPI_DSI_TX0_D2P{slash}LVDS_TX0_D2P-PadAP27)") (class "Default")
      (node (ref "U1") (pin "AP27") (pinfunction "MIPI_DSI_TX0_D2P/LVDS_TX0_D2P_AP27") (pintype "passive"))
    )
    (net (code "356") (name "unconnected-(U1E-MIPI_DSI_TX0_D3N{slash}LVDS_TX0_D3N-PadAP26)") (class "Default")
      (node (ref "U1") (pin "AP26") (pinfunction "MIPI_DSI_TX0_D3N/LVDS_TX0_D3N_AP26") (pintype "passive"))
    )
    (net (code "357") (name "unconnected-(U1E-MIPI_DSI_TX0_D3P{slash}LVDS_TX0_D3P-PadAR26)") (class "Default")
      (node (ref "U1") (pin "AR26") (pinfunction "MIPI_DSI_TX0_D3P/LVDS_TX0_D3P_AR26") (pintype "passive"))
    )
    (net (code "358") (name "unconnected-(U1E-MIPI_DSI_TX1_CLKN-Pad1U11)") (class "Default")
      (node (ref "U1") (pin "1U11") (pinfunction "MIPI_DSI_TX1_CLKN_1U11") (pintype "passive"))
    )
    (net (code "359") (name "unconnected-(U1E-MIPI_DSI_TX1_CLKP-Pad1V11)") (class "Default")
      (node (ref "U1") (pin "1V11") (pinfunction "MIPI_DSI_TX1_CLKP_1V11") (pintype "passive"))
    )
    (net (code "360") (name "unconnected-(U1E-MIPI_DSI_TX1_D0N-PadAR24)") (class "Default")
      (node (ref "U1") (pin "AR24") (pinfunction "MIPI_DSI_TX1_D0N_AR24") (pintype "passive"))
    )
    (net (code "361") (name "unconnected-(U1E-MIPI_DSI_TX1_D0P-PadAP24)") (class "Default")
      (node (ref "U1") (pin "AP24") (pinfunction "MIPI_DSI_TX1_D0P_AP24") (pintype "passive"))
    )
    (net (code "362") (name "unconnected-(U1E-MIPI_DSI_TX1_D1N-PadAP23)") (class "Default")
      (node (ref "U1") (pin "AP23") (pinfunction "MIPI_DSI_TX1_D1N_AP23") (pintype "passive"))
    )
    (net (code "363") (name "unconnected-(U1E-MIPI_DSI_TX1_D1P-PadAR23)") (class "Default")
      (node (ref "U1") (pin "AR23") (pinfunction "MIPI_DSI_TX1_D1P_AR23") (pintype "passive"))
    )
    (net (code "364") (name "unconnected-(U1E-MIPI_DSI_TX1_D2N-PadAR21)") (class "Default")
      (node (ref "U1") (pin "AR21") (pinfunction "MIPI_DSI_TX1_D2N_AR21") (pintype "passive"))
    )
    (net (code "365") (name "unconnected-(U1E-MIPI_DSI_TX1_D2P-PadAP21)") (class "Default")
      (node (ref "U1") (pin "AP21") (pinfunction "MIPI_DSI_TX1_D2P_AP21") (pintype "passive"))
    )
    (net (code "366") (name "unconnected-(U1E-MIPI_DSI_TX1_D3N-PadAP20)") (class "Default")
      (node (ref "U1") (pin "AP20") (pinfunction "MIPI_DSI_TX1_D3N_AP20") (pintype "passive"))
    )
    (net (code "367") (name "unconnected-(U1E-MIPI_DSI_TX1_D3P-PadAR20)") (class "Default")
      (node (ref "U1") (pin "AR20") (pinfunction "MIPI_DSI_TX1_D3P_AR20") (pintype "passive"))
    )
    (net (code "368") (name "unconnected-(U1F-DDR4_A1{slash}-{slash}DDR3_A2{slash}-{slash}AC1-Pad1D2)") (class "Default")
      (node (ref "U1") (pin "1D2") (pinfunction "DDR4_A1/-/DDR3_A2/-/AC1_1D2") (pintype "passive+no_connect"))
    )
    (net (code "369") (name "unconnected-(U1F-DDR4_BG0{slash}LPDDR4_ODT1_CA_B{slash}DDR3_WEn{slash}-{slash}AC20-Pad1A4)") (class "Default")
      (node (ref "U1") (pin "1A4") (pinfunction "DDR4_BG0/LPDDR4_ODT1_CA_B/DDR3_WEn/-/AC20_1A4") (pintype "passive+no_connect"))
    )
    (net (code "370") (name "unconnected-(U1F-DDR4_BG1{slash}LPDDR4_ODT1_CA_A{slash}DDR3_BA0{slash}-{slash}AC21-Pad1C2)") (class "Default")
      (node (ref "U1") (pin "1C2") (pinfunction "DDR4_BG1/LPDDR4_ODT1_CA_A/DDR3_BA0/-/AC21_1C2") (pintype "passive+no_connect"))
    )
  )
)
